# TD4_CPU.net
KiCad netlist of a schematic drawn in Altium Designer
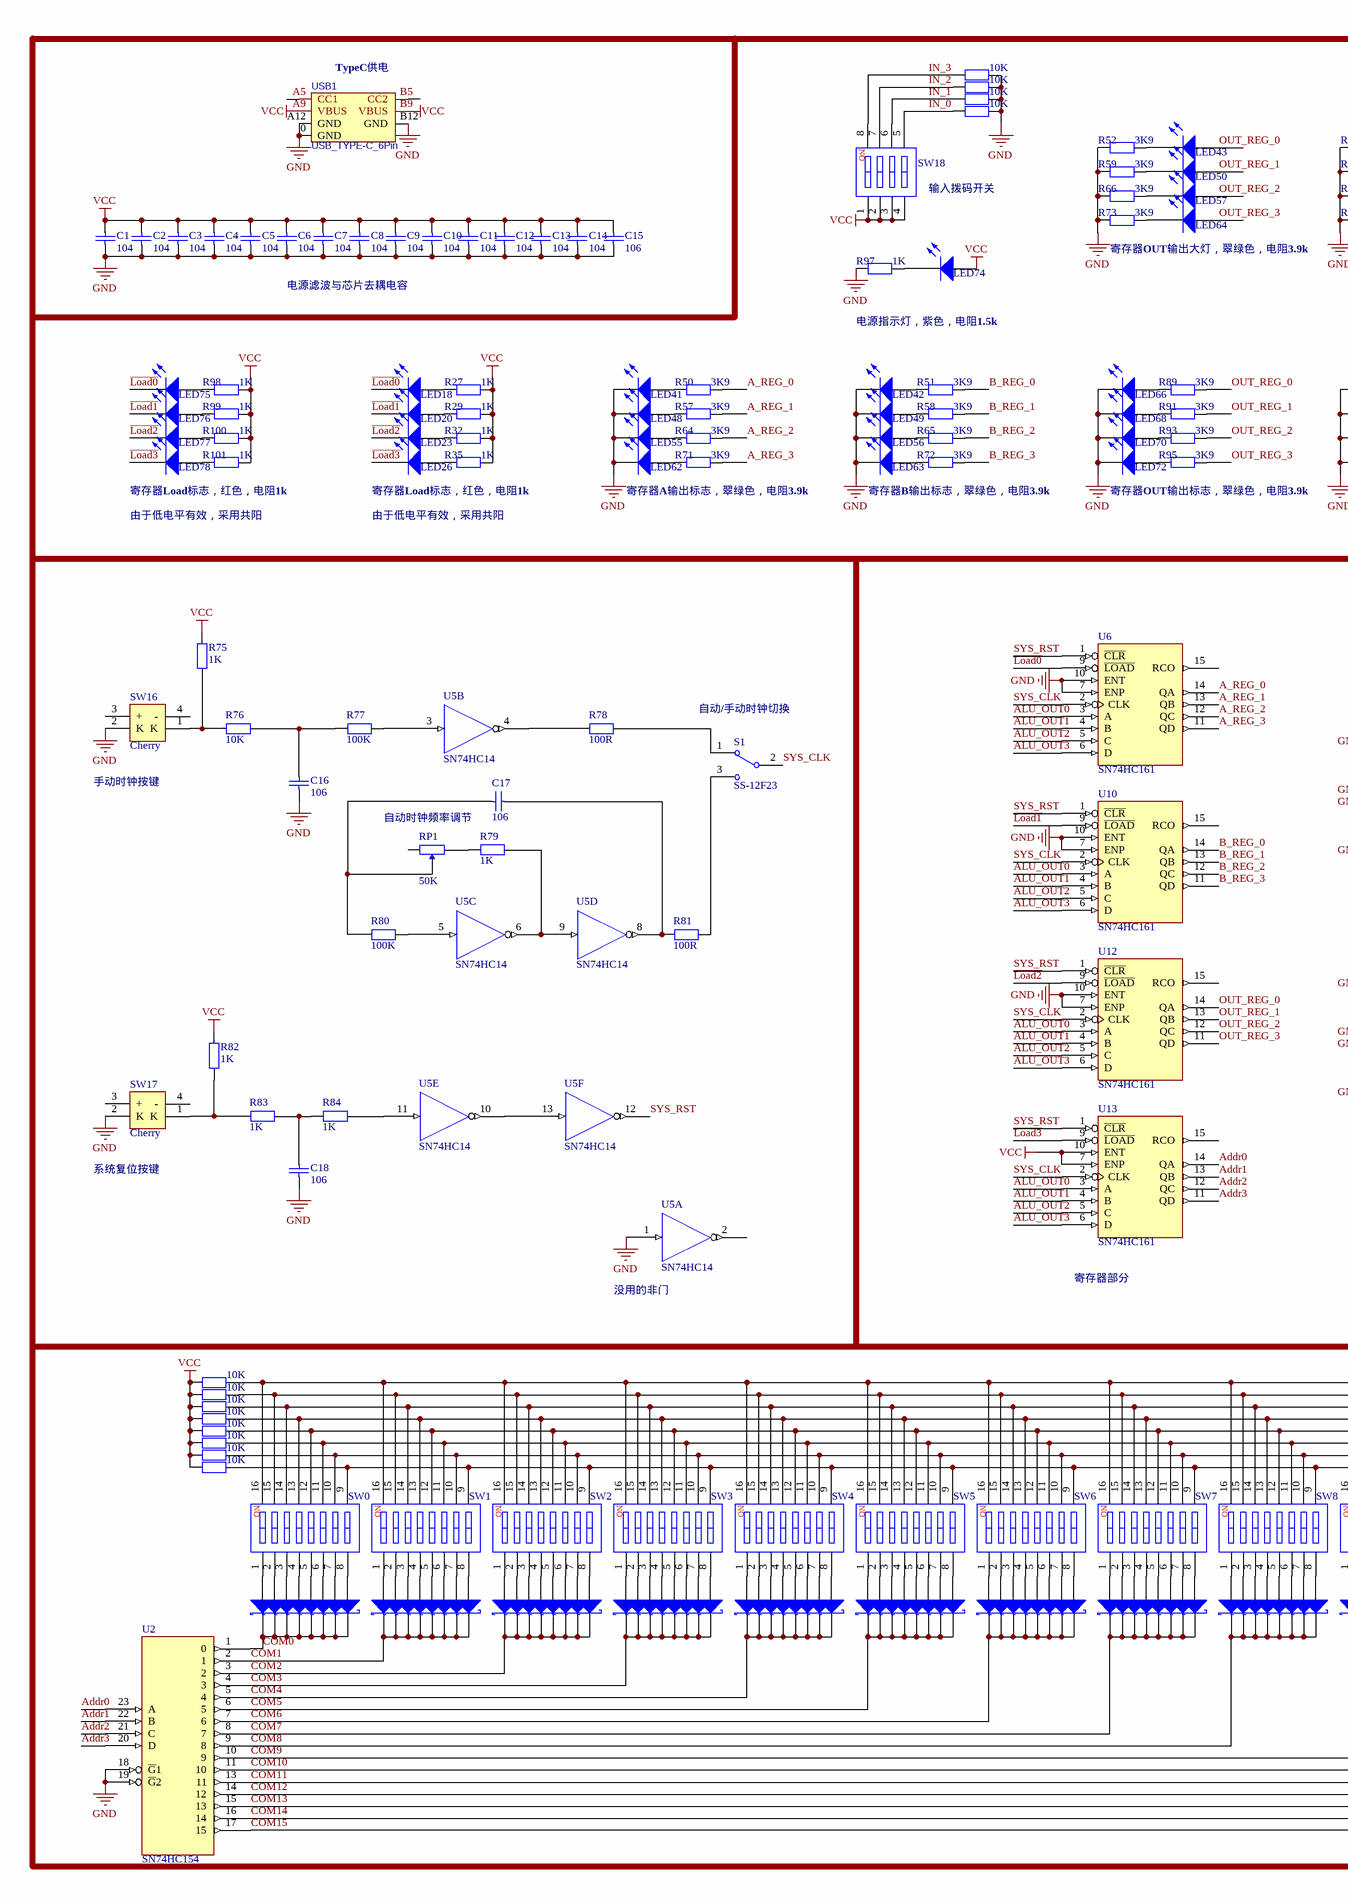
[diagram p0: TD4_CPU.SchDoc, left]
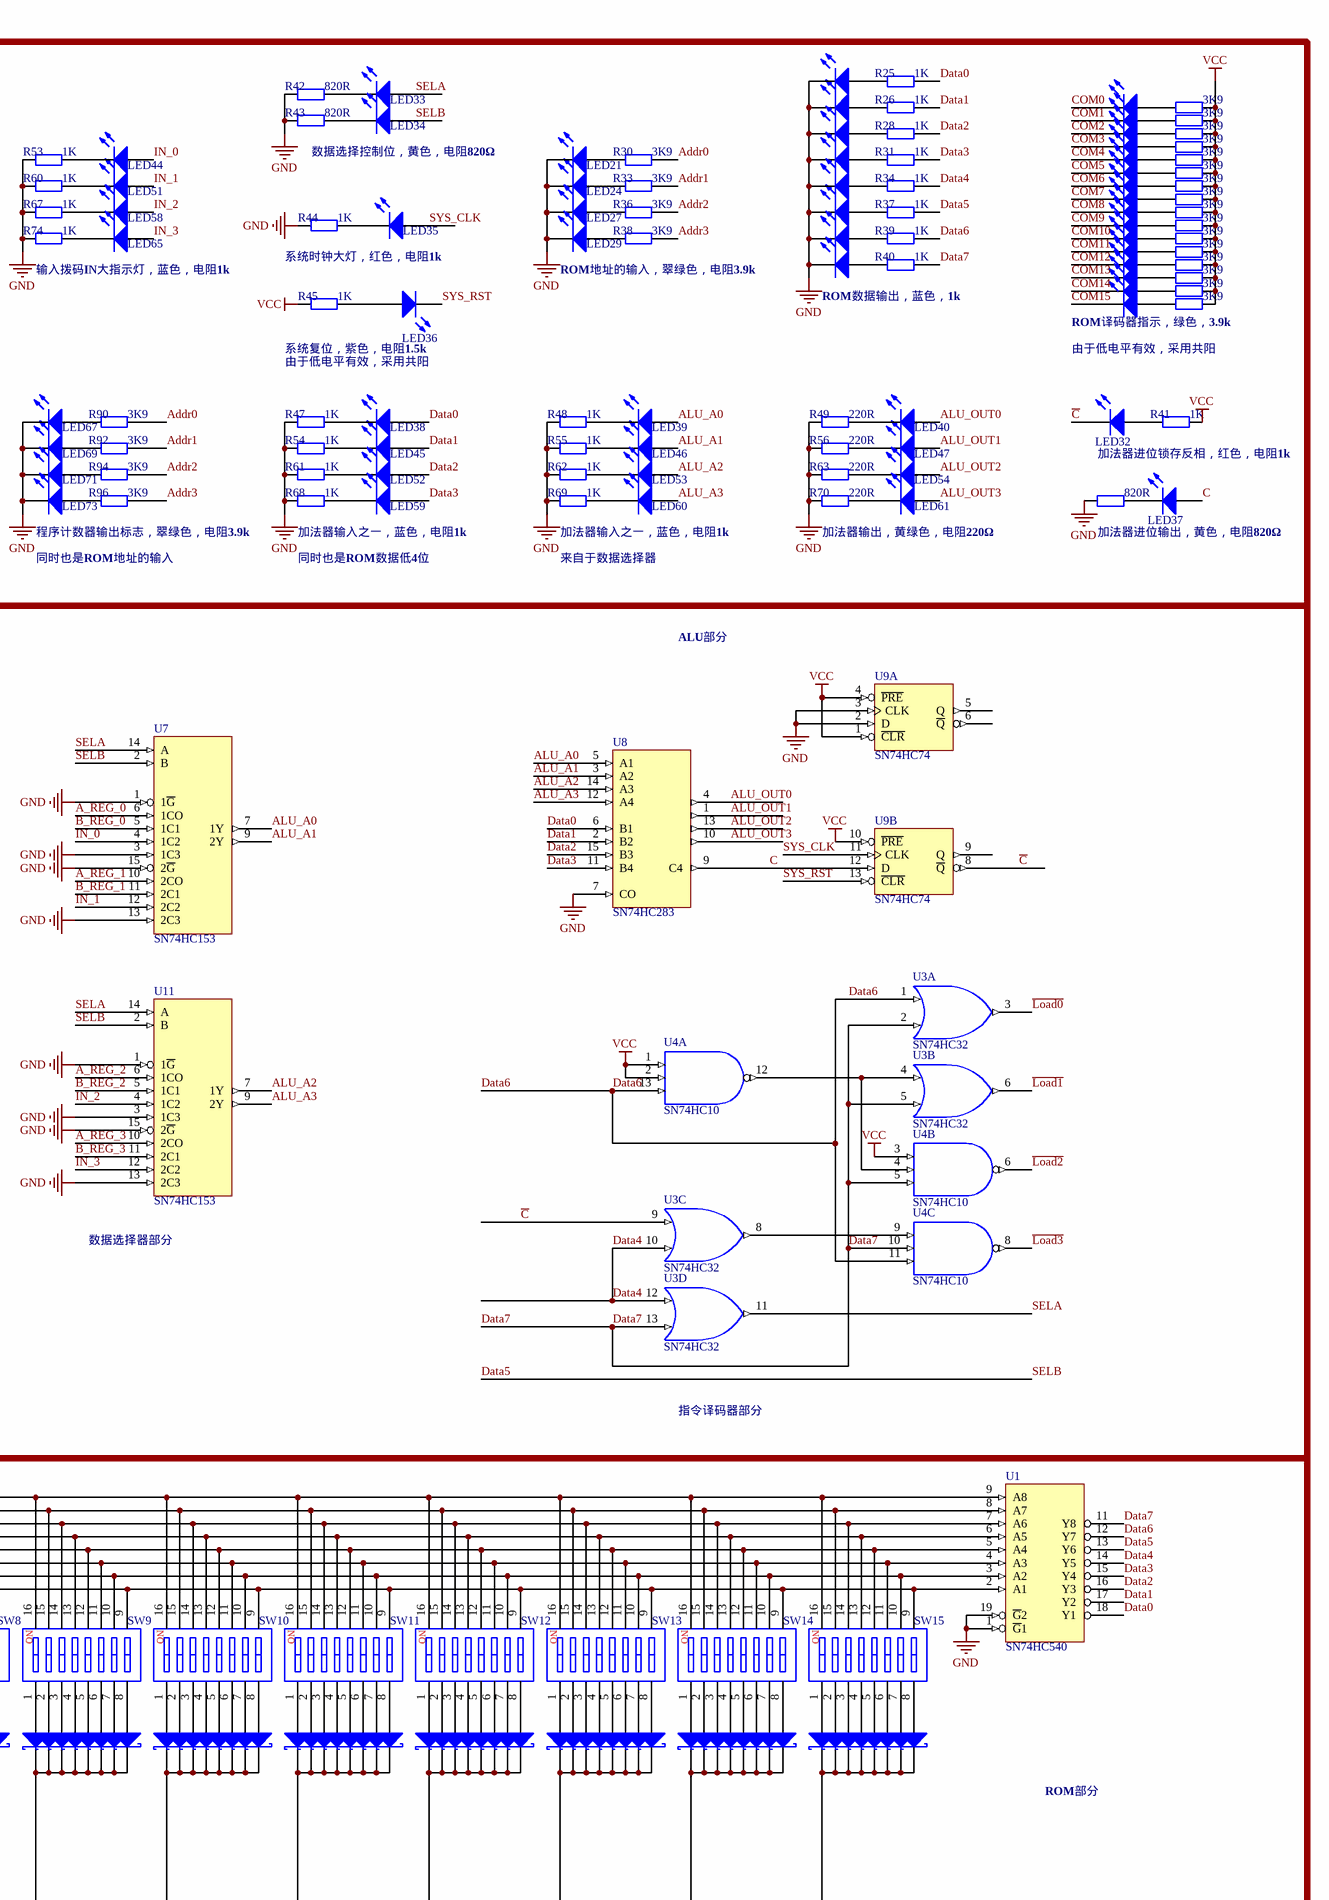
[diagram p1: TD4_CPU.SchDoc, right]

(export (version "E")
  (design (tool "Eeschema 10.0.6"))
  (components
    (comp (ref "C1")
      (value "104")
      (footprint "C0805_L")
      (description "贴片电容/MLCC电容")
      (libsource (lib "0.1 - 电阻-电容-电感-保险丝-晶振-晶体-磁珠-电位器-法拉电容-馈通电容") (part "C"))
    )
    (comp (ref "C2")
      (value "104")
      (footprint "C0805_L")
      (description "贴片电容/MLCC电容")
      (libsource (lib "0.1 - 电阻-电容-电感-保险丝-晶振-晶体-磁珠-电位器-法拉电容-馈通电容") (part "C"))
    )
    (comp (ref "C3")
      (value "104")
      (footprint "C0805_L")
      (description "贴片电容/MLCC电容")
      (libsource (lib "0.1 - 电阻-电容-电感-保险丝-晶振-晶体-磁珠-电位器-法拉电容-馈通电容") (part "C"))
    )
    (comp (ref "C4")
      (value "104")
      (footprint "C0805_L")
      (description "贴片电容/MLCC电容")
      (libsource (lib "0.1 - 电阻-电容-电感-保险丝-晶振-晶体-磁珠-电位器-法拉电容-馈通电容") (part "C"))
    )
    (comp (ref "C5")
      (value "104")
      (footprint "C0805_L")
      (description "贴片电容/MLCC电容")
      (libsource (lib "0.1 - 电阻-电容-电感-保险丝-晶振-晶体-磁珠-电位器-法拉电容-馈通电容") (part "C"))
    )
    (comp (ref "C6")
      (value "104")
      (footprint "C0805_L")
      (description "贴片电容/MLCC电容")
      (libsource (lib "0.1 - 电阻-电容-电感-保险丝-晶振-晶体-磁珠-电位器-法拉电容-馈通电容") (part "C"))
    )
    (comp (ref "C7")
      (value "104")
      (footprint "C0805_L")
      (description "贴片电容/MLCC电容")
      (libsource (lib "0.1 - 电阻-电容-电感-保险丝-晶振-晶体-磁珠-电位器-法拉电容-馈通电容") (part "C"))
    )
    (comp (ref "C8")
      (value "104")
      (footprint "C0805_L")
      (description "贴片电容/MLCC电容")
      (libsource (lib "0.1 - 电阻-电容-电感-保险丝-晶振-晶体-磁珠-电位器-法拉电容-馈通电容") (part "C"))
    )
    (comp (ref "C9")
      (value "104")
      (footprint "C0805_L")
      (description "贴片电容/MLCC电容")
      (libsource (lib "0.1 - 电阻-电容-电感-保险丝-晶振-晶体-磁珠-电位器-法拉电容-馈通电容") (part "C"))
    )
    (comp (ref "C10")
      (value "104")
      (footprint "C0805_L")
      (description "贴片电容/MLCC电容")
      (libsource (lib "0.1 - 电阻-电容-电感-保险丝-晶振-晶体-磁珠-电位器-法拉电容-馈通电容") (part "C"))
    )
    (comp (ref "C11")
      (value "104")
      (footprint "C0805_L")
      (description "贴片电容/MLCC电容")
      (libsource (lib "0.1 - 电阻-电容-电感-保险丝-晶振-晶体-磁珠-电位器-法拉电容-馈通电容") (part "C"))
    )
    (comp (ref "C12")
      (value "104")
      (footprint "C0805_L")
      (description "贴片电容/MLCC电容")
      (libsource (lib "0.1 - 电阻-电容-电感-保险丝-晶振-晶体-磁珠-电位器-法拉电容-馈通电容") (part "C"))
    )
    (comp (ref "C13")
      (value "104")
      (footprint "C0805_L")
      (description "贴片电容/MLCC电容")
      (libsource (lib "0.1 - 电阻-电容-电感-保险丝-晶振-晶体-磁珠-电位器-法拉电容-馈通电容") (part "C"))
    )
    (comp (ref "C14")
      (value "104")
      (footprint "C0805_L")
      (description "贴片电容/MLCC电容")
      (libsource (lib "0.1 - 电阻-电容-电感-保险丝-晶振-晶体-磁珠-电位器-法拉电容-馈通电容") (part "C"))
    )
    (comp (ref "C15")
      (value "106")
      (footprint "C0805_L")
      (description "贴片电容/MLCC电容")
      (libsource (lib "0.1 - 电阻-电容-电感-保险丝-晶振-晶体-磁珠-电位器-法拉电容-馈通电容") (part "C"))
    )
    (comp (ref "C16")
      (value "106")
      (footprint "C0805_L")
      (description "贴片电容/MLCC电容")
      (libsource (lib "0.1 - 电阻-电容-电感-保险丝-晶振-晶体-磁珠-电位器-法拉电容-馈通电容") (part "C"))
    )
    (comp (ref "C17")
      (value "106")
      (footprint "C0805_L")
      (description "贴片电容/MLCC电容")
      (libsource (lib "0.1 - 电阻-电容-电感-保险丝-晶振-晶体-磁珠-电位器-法拉电容-馈通电容") (part "C"))
    )
    (comp (ref "C18")
      (value "106")
      (footprint "C0805_L")
      (description "贴片电容/MLCC电容")
      (libsource (lib "0.1 - 电阻-电容-电感-保险丝-晶振-晶体-磁珠-电位器-法拉电容-馈通电容") (part "C"))
    )
    (comp (ref "D1")
      (value "SS14")
      (footprint "SOD-123")
      (description "肖特基二极管")
      (libsource (lib "0.2 - 二极管-TVS-ESD-整流桥-放电管") (part "SS14"))
    )
    (comp (ref "D2")
      (value "SS14")
      (footprint "SOD-123")
      (description "肖特基二极管")
      (libsource (lib "0.2 - 二极管-TVS-ESD-整流桥-放电管") (part "SS14"))
    )
    (comp (ref "D3")
      (value "SS14")
      (footprint "SOD-123")
      (description "肖特基二极管")
      (libsource (lib "0.2 - 二极管-TVS-ESD-整流桥-放电管") (part "SS14"))
    )
    (comp (ref "D4")
      (value "SS14")
      (footprint "SOD-123")
      (description "肖特基二极管")
      (libsource (lib "0.2 - 二极管-TVS-ESD-整流桥-放电管") (part "SS14"))
    )
    (comp (ref "D5")
      (value "SS14")
      (footprint "SOD-123")
      (description "肖特基二极管")
      (libsource (lib "0.2 - 二极管-TVS-ESD-整流桥-放电管") (part "SS14"))
    )
    (comp (ref "D6")
      (value "SS14")
      (footprint "SOD-123")
      (description "肖特基二极管")
      (libsource (lib "0.2 - 二极管-TVS-ESD-整流桥-放电管") (part "SS14"))
    )
    (comp (ref "D7")
      (value "SS14")
      (footprint "SOD-123")
      (description "肖特基二极管")
      (libsource (lib "0.2 - 二极管-TVS-ESD-整流桥-放电管") (part "SS14"))
    )
    (comp (ref "D8")
      (value "SS14")
      (footprint "SOD-123")
      (description "肖特基二极管")
      (libsource (lib "0.2 - 二极管-TVS-ESD-整流桥-放电管") (part "SS14"))
    )
    (comp (ref "D9")
      (value "SS14")
      (footprint "SOD-123")
      (description "肖特基二极管")
      (libsource (lib "0.2 - 二极管-TVS-ESD-整流桥-放电管") (part "SS14"))
    )
    (comp (ref "D10")
      (value "SS14")
      (footprint "SOD-123")
      (description "肖特基二极管")
      (libsource (lib "0.2 - 二极管-TVS-ESD-整流桥-放电管") (part "SS14"))
    )
    (comp (ref "D11")
      (value "SS14")
      (footprint "SOD-123")
      (description "肖特基二极管")
      (libsource (lib "0.2 - 二极管-TVS-ESD-整流桥-放电管") (part "SS14"))
    )
    (comp (ref "D12")
      (value "SS14")
      (footprint "SOD-123")
      (description "肖特基二极管")
      (libsource (lib "0.2 - 二极管-TVS-ESD-整流桥-放电管") (part "SS14"))
    )
    (comp (ref "D13")
      (value "SS14")
      (footprint "SOD-123")
      (description "肖特基二极管")
      (libsource (lib "0.2 - 二极管-TVS-ESD-整流桥-放电管") (part "SS14"))
    )
    (comp (ref "D14")
      (value "SS14")
      (footprint "SOD-123")
      (description "肖特基二极管")
      (libsource (lib "0.2 - 二极管-TVS-ESD-整流桥-放电管") (part "SS14"))
    )
    (comp (ref "D15")
      (value "SS14")
      (footprint "SOD-123")
      (description "肖特基二极管")
      (libsource (lib "0.2 - 二极管-TVS-ESD-整流桥-放电管") (part "SS14"))
    )
    (comp (ref "D16")
      (value "SS14")
      (footprint "SOD-123")
      (description "肖特基二极管")
      (libsource (lib "0.2 - 二极管-TVS-ESD-整流桥-放电管") (part "SS14"))
    )
    (comp (ref "D17")
      (value "SS14")
      (footprint "SOD-123")
      (description "肖特基二极管")
      (libsource (lib "0.2 - 二极管-TVS-ESD-整流桥-放电管") (part "SS14"))
    )
    (comp (ref "D18")
      (value "SS14")
      (footprint "SOD-123")
      (description "肖特基二极管")
      (libsource (lib "0.2 - 二极管-TVS-ESD-整流桥-放电管") (part "SS14"))
    )
    (comp (ref "D19")
      (value "SS14")
      (footprint "SOD-123")
      (description "肖特基二极管")
      (libsource (lib "0.2 - 二极管-TVS-ESD-整流桥-放电管") (part "SS14"))
    )
    (comp (ref "D20")
      (value "SS14")
      (footprint "SOD-123")
      (description "肖特基二极管")
      (libsource (lib "0.2 - 二极管-TVS-ESD-整流桥-放电管") (part "SS14"))
    )
    (comp (ref "D21")
      (value "SS14")
      (footprint "SOD-123")
      (description "肖特基二极管")
      (libsource (lib "0.2 - 二极管-TVS-ESD-整流桥-放电管") (part "SS14"))
    )
    (comp (ref "D22")
      (value "SS14")
      (footprint "SOD-123")
      (description "肖特基二极管")
      (libsource (lib "0.2 - 二极管-TVS-ESD-整流桥-放电管") (part "SS14"))
    )
    (comp (ref "D23")
      (value "SS14")
      (footprint "SOD-123")
      (description "肖特基二极管")
      (libsource (lib "0.2 - 二极管-TVS-ESD-整流桥-放电管") (part "SS14"))
    )
    (comp (ref "D24")
      (value "SS14")
      (footprint "SOD-123")
      (description "肖特基二极管")
      (libsource (lib "0.2 - 二极管-TVS-ESD-整流桥-放电管") (part "SS14"))
    )
    (comp (ref "D25")
      (value "SS14")
      (footprint "SOD-123")
      (description "肖特基二极管")
      (libsource (lib "0.2 - 二极管-TVS-ESD-整流桥-放电管") (part "SS14"))
    )
    (comp (ref "D26")
      (value "SS14")
      (footprint "SOD-123")
      (description "肖特基二极管")
      (libsource (lib "0.2 - 二极管-TVS-ESD-整流桥-放电管") (part "SS14"))
    )
    (comp (ref "D27")
      (value "SS14")
      (footprint "SOD-123")
      (description "肖特基二极管")
      (libsource (lib "0.2 - 二极管-TVS-ESD-整流桥-放电管") (part "SS14"))
    )
    (comp (ref "D28")
      (value "SS14")
      (footprint "SOD-123")
      (description "肖特基二极管")
      (libsource (lib "0.2 - 二极管-TVS-ESD-整流桥-放电管") (part "SS14"))
    )
    (comp (ref "D29")
      (value "SS14")
      (footprint "SOD-123")
      (description "肖特基二极管")
      (libsource (lib "0.2 - 二极管-TVS-ESD-整流桥-放电管") (part "SS14"))
    )
    (comp (ref "D30")
      (value "SS14")
      (footprint "SOD-123")
      (description "肖特基二极管")
      (libsource (lib "0.2 - 二极管-TVS-ESD-整流桥-放电管") (part "SS14"))
    )
    (comp (ref "D31")
      (value "SS14")
      (footprint "SOD-123")
      (description "肖特基二极管")
      (libsource (lib "0.2 - 二极管-TVS-ESD-整流桥-放电管") (part "SS14"))
    )
    (comp (ref "D32")
      (value "SS14")
      (footprint "SOD-123")
      (description "肖特基二极管")
      (libsource (lib "0.2 - 二极管-TVS-ESD-整流桥-放电管") (part "SS14"))
    )
    (comp (ref "D33")
      (value "SS14")
      (footprint "SOD-123")
      (description "肖特基二极管")
      (libsource (lib "0.2 - 二极管-TVS-ESD-整流桥-放电管") (part "SS14"))
    )
    (comp (ref "D34")
      (value "SS14")
      (footprint "SOD-123")
      (description "肖特基二极管")
      (libsource (lib "0.2 - 二极管-TVS-ESD-整流桥-放电管") (part "SS14"))
    )
    (comp (ref "D35")
      (value "SS14")
      (footprint "SOD-123")
      (description "肖特基二极管")
      (libsource (lib "0.2 - 二极管-TVS-ESD-整流桥-放电管") (part "SS14"))
    )
    (comp (ref "D36")
      (value "SS14")
      (footprint "SOD-123")
      (description "肖特基二极管")
      (libsource (lib "0.2 - 二极管-TVS-ESD-整流桥-放电管") (part "SS14"))
    )
    (comp (ref "D37")
      (value "SS14")
      (footprint "SOD-123")
      (description "肖特基二极管")
      (libsource (lib "0.2 - 二极管-TVS-ESD-整流桥-放电管") (part "SS14"))
    )
    (comp (ref "D38")
      (value "SS14")
      (footprint "SOD-123")
      (description "肖特基二极管")
      (libsource (lib "0.2 - 二极管-TVS-ESD-整流桥-放电管") (part "SS14"))
    )
    (comp (ref "D39")
      (value "SS14")
      (footprint "SOD-123")
      (description "肖特基二极管")
      (libsource (lib "0.2 - 二极管-TVS-ESD-整流桥-放电管") (part "SS14"))
    )
    (comp (ref "D40")
      (value "SS14")
      (footprint "SOD-123")
      (description "肖特基二极管")
      (libsource (lib "0.2 - 二极管-TVS-ESD-整流桥-放电管") (part "SS14"))
    )
    (comp (ref "D41")
      (value "SS14")
      (footprint "SOD-123")
      (description "肖特基二极管")
      (libsource (lib "0.2 - 二极管-TVS-ESD-整流桥-放电管") (part "SS14"))
    )
    (comp (ref "D42")
      (value "SS14")
      (footprint "SOD-123")
      (description "肖特基二极管")
      (libsource (lib "0.2 - 二极管-TVS-ESD-整流桥-放电管") (part "SS14"))
    )
    (comp (ref "D43")
      (value "SS14")
      (footprint "SOD-123")
      (description "肖特基二极管")
      (libsource (lib "0.2 - 二极管-TVS-ESD-整流桥-放电管") (part "SS14"))
    )
    (comp (ref "D44")
      (value "SS14")
      (footprint "SOD-123")
      (description "肖特基二极管")
      (libsource (lib "0.2 - 二极管-TVS-ESD-整流桥-放电管") (part "SS14"))
    )
    (comp (ref "D45")
      (value "SS14")
      (footprint "SOD-123")
      (description "肖特基二极管")
      (libsource (lib "0.2 - 二极管-TVS-ESD-整流桥-放电管") (part "SS14"))
    )
    (comp (ref "D46")
      (value "SS14")
      (footprint "SOD-123")
      (description "肖特基二极管")
      (libsource (lib "0.2 - 二极管-TVS-ESD-整流桥-放电管") (part "SS14"))
    )
    (comp (ref "D47")
      (value "SS14")
      (footprint "SOD-123")
      (description "肖特基二极管")
      (libsource (lib "0.2 - 二极管-TVS-ESD-整流桥-放电管") (part "SS14"))
    )
    (comp (ref "D48")
      (value "SS14")
      (footprint "SOD-123")
      (description "肖特基二极管")
      (libsource (lib "0.2 - 二极管-TVS-ESD-整流桥-放电管") (part "SS14"))
    )
    (comp (ref "D49")
      (value "SS14")
      (footprint "SOD-123")
      (description "肖特基二极管")
      (libsource (lib "0.2 - 二极管-TVS-ESD-整流桥-放电管") (part "SS14"))
    )
    (comp (ref "D50")
      (value "SS14")
      (footprint "SOD-123")
      (description "肖特基二极管")
      (libsource (lib "0.2 - 二极管-TVS-ESD-整流桥-放电管") (part "SS14"))
    )
    (comp (ref "D51")
      (value "SS14")
      (footprint "SOD-123")
      (description "肖特基二极管")
      (libsource (lib "0.2 - 二极管-TVS-ESD-整流桥-放电管") (part "SS14"))
    )
    (comp (ref "D52")
      (value "SS14")
      (footprint "SOD-123")
      (description "肖特基二极管")
      (libsource (lib "0.2 - 二极管-TVS-ESD-整流桥-放电管") (part "SS14"))
    )
    (comp (ref "D53")
      (value "SS14")
      (footprint "SOD-123")
      (description "肖特基二极管")
      (libsource (lib "0.2 - 二极管-TVS-ESD-整流桥-放电管") (part "SS14"))
    )
    (comp (ref "D54")
      (value "SS14")
      (footprint "SOD-123")
      (description "肖特基二极管")
      (libsource (lib "0.2 - 二极管-TVS-ESD-整流桥-放电管") (part "SS14"))
    )
    (comp (ref "D55")
      (value "SS14")
      (footprint "SOD-123")
      (description "肖特基二极管")
      (libsource (lib "0.2 - 二极管-TVS-ESD-整流桥-放电管") (part "SS14"))
    )
    (comp (ref "D56")
      (value "SS14")
      (footprint "SOD-123")
      (description "肖特基二极管")
      (libsource (lib "0.2 - 二极管-TVS-ESD-整流桥-放电管") (part "SS14"))
    )
    (comp (ref "D57")
      (value "SS14")
      (footprint "SOD-123")
      (description "肖特基二极管")
      (libsource (lib "0.2 - 二极管-TVS-ESD-整流桥-放电管") (part "SS14"))
    )
    (comp (ref "D58")
      (value "SS14")
      (footprint "SOD-123")
      (description "肖特基二极管")
      (libsource (lib "0.2 - 二极管-TVS-ESD-整流桥-放电管") (part "SS14"))
    )
    (comp (ref "D59")
      (value "SS14")
      (footprint "SOD-123")
      (description "肖特基二极管")
      (libsource (lib "0.2 - 二极管-TVS-ESD-整流桥-放电管") (part "SS14"))
    )
    (comp (ref "D60")
      (value "SS14")
      (footprint "SOD-123")
      (description "肖特基二极管")
      (libsource (lib "0.2 - 二极管-TVS-ESD-整流桥-放电管") (part "SS14"))
    )
    (comp (ref "D61")
      (value "SS14")
      (footprint "SOD-123")
      (description "肖特基二极管")
      (libsource (lib "0.2 - 二极管-TVS-ESD-整流桥-放电管") (part "SS14"))
    )
    (comp (ref "D62")
      (value "SS14")
      (footprint "SOD-123")
      (description "肖特基二极管")
      (libsource (lib "0.2 - 二极管-TVS-ESD-整流桥-放电管") (part "SS14"))
    )
    (comp (ref "D63")
      (value "SS14")
      (footprint "SOD-123")
      (description "肖特基二极管")
      (libsource (lib "0.2 - 二极管-TVS-ESD-整流桥-放电管") (part "SS14"))
    )
    (comp (ref "D64")
      (value "SS14")
      (footprint "SOD-123")
      (description "肖特基二极管")
      (libsource (lib "0.2 - 二极管-TVS-ESD-整流桥-放电管") (part "SS14"))
    )
    (comp (ref "D65")
      (value "SS14")
      (footprint "SOD-123")
      (description "肖特基二极管")
      (libsource (lib "0.2 - 二极管-TVS-ESD-整流桥-放电管") (part "SS14"))
    )
    (comp (ref "D66")
      (value "SS14")
      (footprint "SOD-123")
      (description "肖特基二极管")
      (libsource (lib "0.2 - 二极管-TVS-ESD-整流桥-放电管") (part "SS14"))
    )
    (comp (ref "D67")
      (value "SS14")
      (footprint "SOD-123")
      (description "肖特基二极管")
      (libsource (lib "0.2 - 二极管-TVS-ESD-整流桥-放电管") (part "SS14"))
    )
    (comp (ref "D68")
      (value "SS14")
      (footprint "SOD-123")
      (description "肖特基二极管")
      (libsource (lib "0.2 - 二极管-TVS-ESD-整流桥-放电管") (part "SS14"))
    )
    (comp (ref "D69")
      (value "SS14")
      (footprint "SOD-123")
      (description "肖特基二极管")
      (libsource (lib "0.2 - 二极管-TVS-ESD-整流桥-放电管") (part "SS14"))
    )
    (comp (ref "D70")
      (value "SS14")
      (footprint "SOD-123")
      (description "肖特基二极管")
      (libsource (lib "0.2 - 二极管-TVS-ESD-整流桥-放电管") (part "SS14"))
    )
    (comp (ref "D71")
      (value "SS14")
      (footprint "SOD-123")
      (description "肖特基二极管")
      (libsource (lib "0.2 - 二极管-TVS-ESD-整流桥-放电管") (part "SS14"))
    )
    (comp (ref "D72")
      (value "SS14")
      (footprint "SOD-123")
      (description "肖特基二极管")
      (libsource (lib "0.2 - 二极管-TVS-ESD-整流桥-放电管") (part "SS14"))
    )
    (comp (ref "D73")
      (value "SS14")
      (footprint "SOD-123")
      (description "肖特基二极管")
      (libsource (lib "0.2 - 二极管-TVS-ESD-整流桥-放电管") (part "SS14"))
    )
    (comp (ref "D74")
      (value "SS14")
      (footprint "SOD-123")
      (description "肖特基二极管")
      (libsource (lib "0.2 - 二极管-TVS-ESD-整流桥-放电管") (part "SS14"))
    )
    (comp (ref "D75")
      (value "SS14")
      (footprint "SOD-123")
      (description "肖特基二极管")
      (libsource (lib "0.2 - 二极管-TVS-ESD-整流桥-放电管") (part "SS14"))
    )
    (comp (ref "D76")
      (value "SS14")
      (footprint "SOD-123")
      (description "肖特基二极管")
      (libsource (lib "0.2 - 二极管-TVS-ESD-整流桥-放电管") (part "SS14"))
    )
    (comp (ref "D77")
      (value "SS14")
      (footprint "SOD-123")
      (description "肖特基二极管")
      (libsource (lib "0.2 - 二极管-TVS-ESD-整流桥-放电管") (part "SS14"))
    )
    (comp (ref "D78")
      (value "SS14")
      (footprint "SOD-123")
      (description "肖特基二极管")
      (libsource (lib "0.2 - 二极管-TVS-ESD-整流桥-放电管") (part "SS14"))
    )
    (comp (ref "D79")
      (value "SS14")
      (footprint "SOD-123")
      (description "肖特基二极管")
      (libsource (lib "0.2 - 二极管-TVS-ESD-整流桥-放电管") (part "SS14"))
    )
    (comp (ref "D80")
      (value "SS14")
      (footprint "SOD-123")
      (description "肖特基二极管")
      (libsource (lib "0.2 - 二极管-TVS-ESD-整流桥-放电管") (part "SS14"))
    )
    (comp (ref "D81")
      (value "SS14")
      (footprint "SOD-123")
      (description "肖特基二极管")
      (libsource (lib "0.2 - 二极管-TVS-ESD-整流桥-放电管") (part "SS14"))
    )
    (comp (ref "D82")
      (value "SS14")
      (footprint "SOD-123")
      (description "肖特基二极管")
      (libsource (lib "0.2 - 二极管-TVS-ESD-整流桥-放电管") (part "SS14"))
    )
    (comp (ref "D83")
      (value "SS14")
      (footprint "SOD-123")
      (description "肖特基二极管")
      (libsource (lib "0.2 - 二极管-TVS-ESD-整流桥-放电管") (part "SS14"))
    )
    (comp (ref "D84")
      (value "SS14")
      (footprint "SOD-123")
      (description "肖特基二极管")
      (libsource (lib "0.2 - 二极管-TVS-ESD-整流桥-放电管") (part "SS14"))
    )
    (comp (ref "D85")
      (value "SS14")
      (footprint "SOD-123")
      (description "肖特基二极管")
      (libsource (lib "0.2 - 二极管-TVS-ESD-整流桥-放电管") (part "SS14"))
    )
    (comp (ref "D86")
      (value "SS14")
      (footprint "SOD-123")
      (description "肖特基二极管")
      (libsource (lib "0.2 - 二极管-TVS-ESD-整流桥-放电管") (part "SS14"))
    )
    (comp (ref "D87")
      (value "SS14")
      (footprint "SOD-123")
      (description "肖特基二极管")
      (libsource (lib "0.2 - 二极管-TVS-ESD-整流桥-放电管") (part "SS14"))
    )
    (comp (ref "D88")
      (value "SS14")
      (footprint "SOD-123")
      (description "肖特基二极管")
      (libsource (lib "0.2 - 二极管-TVS-ESD-整流桥-放电管") (part "SS14"))
    )
    (comp (ref "D89")
      (value "SS14")
      (footprint "SOD-123")
      (description "肖特基二极管")
      (libsource (lib "0.2 - 二极管-TVS-ESD-整流桥-放电管") (part "SS14"))
    )
    (comp (ref "D90")
      (value "SS14")
      (footprint "SOD-123")
      (description "肖特基二极管")
      (libsource (lib "0.2 - 二极管-TVS-ESD-整流桥-放电管") (part "SS14"))
    )
    (comp (ref "D91")
      (value "SS14")
      (footprint "SOD-123")
      (description "肖特基二极管")
      (libsource (lib "0.2 - 二极管-TVS-ESD-整流桥-放电管") (part "SS14"))
    )
    (comp (ref "D92")
      (value "SS14")
      (footprint "SOD-123")
      (description "肖特基二极管")
      (libsource (lib "0.2 - 二极管-TVS-ESD-整流桥-放电管") (part "SS14"))
    )
    (comp (ref "D93")
      (value "SS14")
      (footprint "SOD-123")
      (description "肖特基二极管")
      (libsource (lib "0.2 - 二极管-TVS-ESD-整流桥-放电管") (part "SS14"))
    )
    (comp (ref "D94")
      (value "SS14")
      (footprint "SOD-123")
      (description "肖特基二极管")
      (libsource (lib "0.2 - 二极管-TVS-ESD-整流桥-放电管") (part "SS14"))
    )
    (comp (ref "D95")
      (value "SS14")
      (footprint "SOD-123")
      (description "肖特基二极管")
      (libsource (lib "0.2 - 二极管-TVS-ESD-整流桥-放电管") (part "SS14"))
    )
    (comp (ref "D96")
      (value "SS14")
      (footprint "SOD-123")
      (description "肖特基二极管")
      (libsource (lib "0.2 - 二极管-TVS-ESD-整流桥-放电管") (part "SS14"))
    )
    (comp (ref "D97")
      (value "SS14")
      (footprint "SOD-123")
      (description "肖特基二极管")
      (libsource (lib "0.2 - 二极管-TVS-ESD-整流桥-放电管") (part "SS14"))
    )
    (comp (ref "D98")
      (value "SS14")
      (footprint "SOD-123")
      (description "肖特基二极管")
      (libsource (lib "0.2 - 二极管-TVS-ESD-整流桥-放电管") (part "SS14"))
    )
    (comp (ref "D99")
      (value "SS14")
      (footprint "SOD-123")
      (description "肖特基二极管")
      (libsource (lib "0.2 - 二极管-TVS-ESD-整流桥-放电管") (part "SS14"))
    )
    (comp (ref "D100")
      (value "SS14")
      (footprint "SOD-123")
      (description "肖特基二极管")
      (libsource (lib "0.2 - 二极管-TVS-ESD-整流桥-放电管") (part "SS14"))
    )
    (comp (ref "D101")
      (value "SS14")
      (footprint "SOD-123")
      (description "肖特基二极管")
      (libsource (lib "0.2 - 二极管-TVS-ESD-整流桥-放电管") (part "SS14"))
    )
    (comp (ref "D102")
      (value "SS14")
      (footprint "SOD-123")
      (description "肖特基二极管")
      (libsource (lib "0.2 - 二极管-TVS-ESD-整流桥-放电管") (part "SS14"))
    )
    (comp (ref "D103")
      (value "SS14")
      (footprint "SOD-123")
      (description "肖特基二极管")
      (libsource (lib "0.2 - 二极管-TVS-ESD-整流桥-放电管") (part "SS14"))
    )
    (comp (ref "D104")
      (value "SS14")
      (footprint "SOD-123")
      (description "肖特基二极管")
      (libsource (lib "0.2 - 二极管-TVS-ESD-整流桥-放电管") (part "SS14"))
    )
    (comp (ref "D105")
      (value "SS14")
      (footprint "SOD-123")
      (description "肖特基二极管")
      (libsource (lib "0.2 - 二极管-TVS-ESD-整流桥-放电管") (part "SS14"))
    )
    (comp (ref "D106")
      (value "SS14")
      (footprint "SOD-123")
      (description "肖特基二极管")
      (libsource (lib "0.2 - 二极管-TVS-ESD-整流桥-放电管") (part "SS14"))
    )
    (comp (ref "D107")
      (value "SS14")
      (footprint "SOD-123")
      (description "肖特基二极管")
      (libsource (lib "0.2 - 二极管-TVS-ESD-整流桥-放电管") (part "SS14"))
    )
    (comp (ref "D108")
      (value "SS14")
      (footprint "SOD-123")
      (description "肖特基二极管")
      (libsource (lib "0.2 - 二极管-TVS-ESD-整流桥-放电管") (part "SS14"))
    )
    (comp (ref "D109")
      (value "SS14")
      (footprint "SOD-123")
      (description "肖特基二极管")
      (libsource (lib "0.2 - 二极管-TVS-ESD-整流桥-放电管") (part "SS14"))
    )
    (comp (ref "D110")
      (value "SS14")
      (footprint "SOD-123")
      (description "肖特基二极管")
      (libsource (lib "0.2 - 二极管-TVS-ESD-整流桥-放电管") (part "SS14"))
    )
    (comp (ref "D111")
      (value "SS14")
      (footprint "SOD-123")
      (description "肖特基二极管")
      (libsource (lib "0.2 - 二极管-TVS-ESD-整流桥-放电管") (part "SS14"))
    )
    (comp (ref "D112")
      (value "SS14")
      (footprint "SOD-123")
      (description "肖特基二极管")
      (libsource (lib "0.2 - 二极管-TVS-ESD-整流桥-放电管") (part "SS14"))
    )
    (comp (ref "D113")
      (value "SS14")
      (footprint "SOD-123")
      (description "肖特基二极管")
      (libsource (lib "0.2 - 二极管-TVS-ESD-整流桥-放电管") (part "SS14"))
    )
    (comp (ref "D114")
      (value "SS14")
      (footprint "SOD-123")
      (description "肖特基二极管")
      (libsource (lib "0.2 - 二极管-TVS-ESD-整流桥-放电管") (part "SS14"))
    )
    (comp (ref "D115")
      (value "SS14")
      (footprint "SOD-123")
      (description "肖特基二极管")
      (libsource (lib "0.2 - 二极管-TVS-ESD-整流桥-放电管") (part "SS14"))
    )
    (comp (ref "D116")
      (value "SS14")
      (footprint "SOD-123")
      (description "肖特基二极管")
      (libsource (lib "0.2 - 二极管-TVS-ESD-整流桥-放电管") (part "SS14"))
    )
    (comp (ref "D117")
      (value "SS14")
      (footprint "SOD-123")
      (description "肖特基二极管")
      (libsource (lib "0.2 - 二极管-TVS-ESD-整流桥-放电管") (part "SS14"))
    )
    (comp (ref "D118")
      (value "SS14")
      (footprint "SOD-123")
      (description "肖特基二极管")
      (libsource (lib "0.2 - 二极管-TVS-ESD-整流桥-放电管") (part "SS14"))
    )
    (comp (ref "D119")
      (value "SS14")
      (footprint "SOD-123")
      (description "肖特基二极管")
      (libsource (lib "0.2 - 二极管-TVS-ESD-整流桥-放电管") (part "SS14"))
    )
    (comp (ref "D120")
      (value "SS14")
      (footprint "SOD-123")
      (description "肖特基二极管")
      (libsource (lib "0.2 - 二极管-TVS-ESD-整流桥-放电管") (part "SS14"))
    )
    (comp (ref "D121")
      (value "SS14")
      (footprint "SOD-123")
      (description "肖特基二极管")
      (libsource (lib "0.2 - 二极管-TVS-ESD-整流桥-放电管") (part "SS14"))
    )
    (comp (ref "D122")
      (value "SS14")
      (footprint "SOD-123")
      (description "肖特基二极管")
      (libsource (lib "0.2 - 二极管-TVS-ESD-整流桥-放电管") (part "SS14"))
    )
    (comp (ref "D123")
      (value "SS14")
      (footprint "SOD-123")
      (description "肖特基二极管")
      (libsource (lib "0.2 - 二极管-TVS-ESD-整流桥-放电管") (part "SS14"))
    )
    (comp (ref "D124")
      (value "SS14")
      (footprint "SOD-123")
      (description "肖特基二极管")
      (libsource (lib "0.2 - 二极管-TVS-ESD-整流桥-放电管") (part "SS14"))
    )
    (comp (ref "D125")
      (value "SS14")
      (footprint "SOD-123")
      (description "肖特基二极管")
      (libsource (lib "0.2 - 二极管-TVS-ESD-整流桥-放电管") (part "SS14"))
    )
    (comp (ref "D126")
      (value "SS14")
      (footprint "SOD-123")
      (description "肖特基二极管")
      (libsource (lib "0.2 - 二极管-TVS-ESD-整流桥-放电管") (part "SS14"))
    )
    (comp (ref "D127")
      (value "SS14")
      (footprint "SOD-123")
      (description "肖特基二极管")
      (libsource (lib "0.2 - 二极管-TVS-ESD-整流桥-放电管") (part "SS14"))
    )
    (comp (ref "D128")
      (value "SS14")
      (footprint "SOD-123")
      (description "肖特基二极管")
      (libsource (lib "0.2 - 二极管-TVS-ESD-整流桥-放电管") (part "SS14"))
    )
    (comp (ref "LED0")
      (value "绿色")
      (footprint "LED0805_B")
      (description "贴片LED")
      (libsource (lib "0.3 - LED发光二极管-IR二极管_接收管-光耦") (part "LED"))
    )
    (comp (ref "LED1")
      (value "绿色")
      (footprint "LED0805_B")
      (description "贴片LED")
      (libsource (lib "0.3 - LED发光二极管-IR二极管_接收管-光耦") (part "LED"))
    )
    (comp (ref "LED2")
      (value "绿色")
      (footprint "LED0805_B")
      (description "贴片LED")
      (libsource (lib "0.3 - LED发光二极管-IR二极管_接收管-光耦") (part "LED"))
    )
    (comp (ref "LED3")
      (value "绿色")
      (footprint "LED0805_B")
      (description "贴片LED")
      (libsource (lib "0.3 - LED发光二极管-IR二极管_接收管-光耦") (part "LED"))
    )
    (comp (ref "LED4")
      (value "绿色")
      (footprint "LED0805_B")
      (description "贴片LED")
      (libsource (lib "0.3 - LED发光二极管-IR二极管_接收管-光耦") (part "LED"))
    )
    (comp (ref "LED5")
      (value "绿色")
      (footprint "LED0805_B")
      (description "贴片LED")
      (libsource (lib "0.3 - LED发光二极管-IR二极管_接收管-光耦") (part "LED"))
    )
    (comp (ref "LED6")
      (value "绿色")
      (footprint "LED0805_B")
      (description "贴片LED")
      (libsource (lib "0.3 - LED发光二极管-IR二极管_接收管-光耦") (part "LED"))
    )
    (comp (ref "LED7")
      (value "绿色")
      (footprint "LED0805_B")
      (description "贴片LED")
      (libsource (lib "0.3 - LED发光二极管-IR二极管_接收管-光耦") (part "LED"))
    )
    (comp (ref "LED8")
      (value "绿色")
      (footprint "LED0805_B")
      (description "贴片LED")
      (libsource (lib "0.3 - LED发光二极管-IR二极管_接收管-光耦") (part "LED"))
    )
    (comp (ref "LED9")
      (value "绿色")
      (footprint "LED0805_B")
      (description "贴片LED")
      (libsource (lib "0.3 - LED发光二极管-IR二极管_接收管-光耦") (part "LED"))
    )
    (comp (ref "LED10")
      (value "绿色")
      (footprint "LED0805_B")
      (description "贴片LED")
      (libsource (lib "0.3 - LED发光二极管-IR二极管_接收管-光耦") (part "LED"))
    )
    (comp (ref "LED11")
      (value "绿色")
      (footprint "LED0805_B")
      (description "贴片LED")
      (libsource (lib "0.3 - LED发光二极管-IR二极管_接收管-光耦") (part "LED"))
    )
    (comp (ref "LED12")
      (value "绿色")
      (footprint "LED0805_B")
      (description "贴片LED")
      (libsource (lib "0.3 - LED发光二极管-IR二极管_接收管-光耦") (part "LED"))
    )
    (comp (ref "LED13")
      (value "绿色")
      (footprint "LED0805_B")
      (description "贴片LED")
      (libsource (lib "0.3 - LED发光二极管-IR二极管_接收管-光耦") (part "LED"))
    )
    (comp (ref "LED14")
      (value "绿色")
      (footprint "LED0805_B")
      (description "贴片LED")
      (libsource (lib "0.3 - LED发光二极管-IR二极管_接收管-光耦") (part "LED"))
    )
    (comp (ref "LED15")
      (value "绿色")
      (footprint "LED0805_B")
      (description "贴片LED")
      (libsource (lib "0.3 - LED发光二极管-IR二极管_接收管-光耦") (part "LED"))
    )
    (comp (ref "LED16")
      (value "蓝色")
      (footprint "LED0805_B")
      (description "贴片LED")
      (libsource (lib "0.3 - LED发光二极管-IR二极管_接收管-光耦") (part "LED"))
    )
    (comp (ref "LED17")
      (value "蓝色")
      (footprint "LED0805_B")
      (description "贴片LED")
      (libsource (lib "0.3 - LED发光二极管-IR二极管_接收管-光耦") (part "LED"))
    )
    (comp (ref "LED18")
      (value "红色")
      (footprint "LED0805_B")
      (description "贴片LED")
      (libsource (lib "0.3 - LED发光二极管-IR二极管_接收管-光耦") (part "LED"))
    )
    (comp (ref "LED19")
      (value "蓝色")
      (footprint "LED0805_B")
      (description "贴片LED")
      (libsource (lib "0.3 - LED发光二极管-IR二极管_接收管-光耦") (part "LED"))
    )
    (comp (ref "LED20")
      (value "红色")
      (footprint "LED0805_B")
      (description "贴片LED")
      (libsource (lib "0.3 - LED发光二极管-IR二极管_接收管-光耦") (part "LED"))
    )
    (comp (ref "LED21")
      (value "绿色")
      (footprint "LED0805_B")
      (description "贴片LED")
      (libsource (lib "0.3 - LED发光二极管-IR二极管_接收管-光耦") (part "LED"))
    )
    (comp (ref "LED22")
      (value "蓝色")
      (footprint "LED0805_B")
      (description "贴片LED")
      (libsource (lib "0.3 - LED发光二极管-IR二极管_接收管-光耦") (part "LED"))
    )
    (comp (ref "LED23")
      (value "红色")
      (footprint "LED0805_B")
      (description "贴片LED")
      (libsource (lib "0.3 - LED发光二极管-IR二极管_接收管-光耦") (part "LED"))
    )
    (comp (ref "LED24")
      (value "绿色")
      (footprint "LED0805_B")
      (description "贴片LED")
      (libsource (lib "0.3 - LED发光二极管-IR二极管_接收管-光耦") (part "LED"))
    )
    (comp (ref "LED25")
      (value "蓝色")
      (footprint "LED0805_B")
      (description "贴片LED")
      (libsource (lib "0.3 - LED发光二极管-IR二极管_接收管-光耦") (part "LED"))
    )
    (comp (ref "LED26")
      (value "红色")
      (footprint "LED0805_B")
      (description "贴片LED")
      (libsource (lib "0.3 - LED发光二极管-IR二极管_接收管-光耦") (part "LED"))
    )
    (comp (ref "LED27")
      (value "绿色")
      (footprint "LED0805_B")
      (description "贴片LED")
      (libsource (lib "0.3 - LED发光二极管-IR二极管_接收管-光耦") (part "LED"))
    )
    (comp (ref "LED28")
      (value "蓝色")
      (footprint "LED0805_B")
      (description "贴片LED")
      (libsource (lib "0.3 - LED发光二极管-IR二极管_接收管-光耦") (part "LED"))
    )
    (comp (ref "LED29")
      (value "绿色")
      (footprint "LED0805_B")
      (description "贴片LED")
      (libsource (lib "0.3 - LED发光二极管-IR二极管_接收管-光耦") (part "LED"))
    )
    (comp (ref "LED30")
      (value "蓝色")
      (footprint "LED0805_B")
      (description "贴片LED")
      (libsource (lib "0.3 - LED发光二极管-IR二极管_接收管-光耦") (part "LED"))
    )
    (comp (ref "LED31")
      (value "蓝色")
      (footprint "LED0805_B")
      (description "贴片LED")
      (libsource (lib "0.3 - LED发光二极管-IR二极管_接收管-光耦") (part "LED"))
    )
    (comp (ref "LED32")
      (value "红色")
      (footprint "LED0805_B")
      (description "贴片LED")
      (libsource (lib "0.3 - LED发光二极管-IR二极管_接收管-光耦") (part "LED"))
    )
    (comp (ref "LED33")
      (value "黄色")
      (footprint "LED0805_B")
      (description "贴片LED")
      (libsource (lib "0.3 - LED发光二极管-IR二极管_接收管-光耦") (part "LED"))
    )
    (comp (ref "LED34")
      (value "黄色")
      (footprint "LED0805_B")
      (description "贴片LED")
      (libsource (lib "0.3 - LED发光二极管-IR二极管_接收管-光耦") (part "LED"))
    )
    (comp (ref "LED35")
      (value "红色")
      (footprint "LED F257-W - duplicate")
      (description "贴片LED")
      (libsource (lib "0.3 - LED发光二极管-IR二极管_接收管-光耦") (part "LED"))
    )
    (comp (ref "LED36")
      (value "紫色")
      (footprint "LED0805_B")
      (description "贴片LED")
      (libsource (lib "0.3 - LED发光二极管-IR二极管_接收管-光耦") (part "LED"))
    )
    (comp (ref "LED37")
      (value "黄色")
      (footprint "LED0805_B")
      (description "贴片LED")
      (libsource (lib "0.3 - LED发光二极管-IR二极管_接收管-光耦") (part "LED"))
    )
    (comp (ref "LED38")
      (value "蓝色")
      (footprint "LED0805_B")
      (description "贴片LED")
      (libsource (lib "0.3 - LED发光二极管-IR二极管_接收管-光耦") (part "LED"))
    )
    (comp (ref "LED39")
      (value "蓝色")
      (footprint "LED0805_B")
      (description "贴片LED")
      (libsource (lib "0.3 - LED发光二极管-IR二极管_接收管-光耦") (part "LED"))
    )
    (comp (ref "LED40")
      (value "黄绿色")
      (footprint "LED0805_B")
      (description "贴片LED")
      (libsource (lib "0.3 - LED发光二极管-IR二极管_接收管-光耦") (part "LED"))
    )
    (comp (ref "LED41")
      (value "绿色")
      (footprint "LED0805_B")
      (description "贴片LED")
      (libsource (lib "0.3 - LED发光二极管-IR二极管_接收管-光耦") (part "LED"))
    )
    (comp (ref "LED42")
      (value "绿色")
      (footprint "LED0805_B")
      (description "贴片LED")
      (libsource (lib "0.3 - LED发光二极管-IR二极管_接收管-光耦") (part "LED"))
    )
    (comp (ref "LED43")
      (value "绿色")
      (footprint "LED F257-W - duplicate")
      (description "贴片LED")
      (libsource (lib "0.3 - LED发光二极管-IR二极管_接收管-光耦") (part "LED"))
    )
    (comp (ref "LED44")
      (value "蓝色")
      (footprint "LED F257-W - duplicate")
      (description "贴片LED")
      (libsource (lib "0.3 - LED发光二极管-IR二极管_接收管-光耦") (part "LED"))
    )
    (comp (ref "LED45")
      (value "蓝色")
      (footprint "LED0805_B")
      (description "贴片LED")
      (libsource (lib "0.3 - LED发光二极管-IR二极管_接收管-光耦") (part "LED"))
    )
    (comp (ref "LED46")
      (value "蓝色")
      (footprint "LED0805_B")
      (description "贴片LED")
      (libsource (lib "0.3 - LED发光二极管-IR二极管_接收管-光耦") (part "LED"))
    )
    (comp (ref "LED47")
      (value "黄绿色")
      (footprint "LED0805_B")
      (description "贴片LED")
      (libsource (lib "0.3 - LED发光二极管-IR二极管_接收管-光耦") (part "LED"))
    )
    (comp (ref "LED48")
      (value "绿色")
      (footprint "LED0805_B")
      (description "贴片LED")
      (libsource (lib "0.3 - LED发光二极管-IR二极管_接收管-光耦") (part "LED"))
    )
    (comp (ref "LED49")
      (value "绿色")
      (footprint "LED0805_B")
      (description "贴片LED")
      (libsource (lib "0.3 - LED发光二极管-IR二极管_接收管-光耦") (part "LED"))
    )
    (comp (ref "LED50")
      (value "绿色")
      (footprint "LED F257-W - duplicate")
      (description "贴片LED")
      (libsource (lib "0.3 - LED发光二极管-IR二极管_接收管-光耦") (part "LED"))
    )
    (comp (ref "LED51")
      (value "蓝色")
      (footprint "LED F257-W - duplicate")
      (description "贴片LED")
      (libsource (lib "0.3 - LED发光二极管-IR二极管_接收管-光耦") (part "LED"))
    )
    (comp (ref "LED52")
      (value "蓝色")
      (footprint "LED0805_B")
      (description "贴片LED")
      (libsource (lib "0.3 - LED发光二极管-IR二极管_接收管-光耦") (part "LED"))
    )
    (comp (ref "LED53")
      (value "蓝色")
      (footprint "LED0805_B")
      (description "贴片LED")
      (libsource (lib "0.3 - LED发光二极管-IR二极管_接收管-光耦") (part "LED"))
    )
    (comp (ref "LED54")
      (value "黄绿色")
      (footprint "LED0805_B")
      (description "贴片LED")
      (libsource (lib "0.3 - LED发光二极管-IR二极管_接收管-光耦") (part "LED"))
    )
    (comp (ref "LED55")
      (value "绿色")
      (footprint "LED0805_B")
      (description "贴片LED")
      (libsource (lib "0.3 - LED发光二极管-IR二极管_接收管-光耦") (part "LED"))
    )
    (comp (ref "LED56")
      (value "绿色")
      (footprint "LED0805_B")
      (description "贴片LED")
      (libsource (lib "0.3 - LED发光二极管-IR二极管_接收管-光耦") (part "LED"))
    )
    (comp (ref "LED57")
      (value "绿色")
      (footprint "LED F257-W - duplicate")
      (description "贴片LED")
      (libsource (lib "0.3 - LED发光二极管-IR二极管_接收管-光耦") (part "LED"))
    )
    (comp (ref "LED58")
      (value "蓝色")
      (footprint "LED F257-W - duplicate")
      (description "贴片LED")
      (libsource (lib "0.3 - LED发光二极管-IR二极管_接收管-光耦") (part "LED"))
    )
    (comp (ref "LED59")
      (value "蓝色")
      (footprint "LED0805_B")
      (description "贴片LED")
      (libsource (lib "0.3 - LED发光二极管-IR二极管_接收管-光耦") (part "LED"))
    )
    (comp (ref "LED60")
      (value "蓝色")
      (footprint "LED0805_B")
      (description "贴片LED")
      (libsource (lib "0.3 - LED发光二极管-IR二极管_接收管-光耦") (part "LED"))
    )
    (comp (ref "LED61")
      (value "黄绿色")
      (footprint "LED0805_B")
      (description "贴片LED")
      (libsource (lib "0.3 - LED发光二极管-IR二极管_接收管-光耦") (part "LED"))
    )
    (comp (ref "LED62")
      (value "绿色")
      (footprint "LED0805_B")
      (description "贴片LED")
      (libsource (lib "0.3 - LED发光二极管-IR二极管_接收管-光耦") (part "LED"))
    )
    (comp (ref "LED63")
      (value "绿色")
      (footprint "LED0805_B")
      (description "贴片LED")
      (libsource (lib "0.3 - LED发光二极管-IR二极管_接收管-光耦") (part "LED"))
    )
    (comp (ref "LED64")
      (value "绿色")
      (footprint "LED F257-W - duplicate")
      (description "贴片LED")
      (libsource (lib "0.3 - LED发光二极管-IR二极管_接收管-光耦") (part "LED"))
    )
    (comp (ref "LED65")
      (value "蓝色")
      (footprint "LED F257-W - duplicate")
      (description "贴片LED")
      (libsource (lib "0.3 - LED发光二极管-IR二极管_接收管-光耦") (part "LED"))
    )
    (comp (ref "LED66")
      (value "绿色")
      (footprint "LED0805_B")
      (description "贴片LED")
      (libsource (lib "0.3 - LED发光二极管-IR二极管_接收管-光耦") (part "LED"))
    )
    (comp (ref "LED67")
      (value "绿色")
      (footprint "LED0805_B")
      (description "贴片LED")
      (libsource (lib "0.3 - LED发光二极管-IR二极管_接收管-光耦") (part "LED"))
    )
    (comp (ref "LED68")
      (value "绿色")
      (footprint "LED0805_B")
      (description "贴片LED")
      (libsource (lib "0.3 - LED发光二极管-IR二极管_接收管-光耦") (part "LED"))
    )
    (comp (ref "LED69")
      (value "绿色")
      (footprint "LED0805_B")
      (description "贴片LED")
      (libsource (lib "0.3 - LED发光二极管-IR二极管_接收管-光耦") (part "LED"))
    )
    (comp (ref "LED70")
      (value "绿色")
      (footprint "LED0805_B")
      (description "贴片LED")
      (libsource (lib "0.3 - LED发光二极管-IR二极管_接收管-光耦") (part "LED"))
    )
    (comp (ref "LED71")
      (value "绿色")
      (footprint "LED0805_B")
      (description "贴片LED")
      (libsource (lib "0.3 - LED发光二极管-IR二极管_接收管-光耦") (part "LED"))
    )
    (comp (ref "LED72")
      (value "绿色")
      (footprint "LED0805_B")
      (description "贴片LED")
      (libsource (lib "0.3 - LED发光二极管-IR二极管_接收管-光耦") (part "LED"))
    )
    (comp (ref "LED73")
      (value "绿色")
      (footprint "LED0805_B")
      (description "贴片LED")
      (libsource (lib "0.3 - LED发光二极管-IR二极管_接收管-光耦") (part "LED"))
    )
    (comp (ref "LED74")
      (value "紫色")
      (footprint "LED0805_B")
      (description "贴片LED")
      (libsource (lib "0.3 - LED发光二极管-IR二极管_接收管-光耦") (part "LED"))
    )
    (comp (ref "LED75")
      (value "红色")
      (footprint "LED0805_B")
      (description "贴片LED")
      (libsource (lib "0.3 - LED发光二极管-IR二极管_接收管-光耦") (part "LED"))
    )
    (comp (ref "LED76")
      (value "红色")
      (footprint "LED0805_B")
      (description "贴片LED")
      (libsource (lib "0.3 - LED发光二极管-IR二极管_接收管-光耦") (part "LED"))
    )
    (comp (ref "LED77")
      (value "红色")
      (footprint "LED0805_B")
      (description "贴片LED")
      (libsource (lib "0.3 - LED发光二极管-IR二极管_接收管-光耦") (part "LED"))
    )
    (comp (ref "LED78")
      (value "红色")
      (footprint "LED0805_B")
      (description "贴片LED")
      (libsource (lib "0.3 - LED发光二极管-IR二极管_接收管-光耦") (part "LED"))
    )
    (comp (ref "R1")
      (value "10K")
      (footprint "R0805_L")
      (description "贴片电阻")
      (libsource (lib "0.1 - 电阻-电容-电感-保险丝-晶振-晶体-磁珠-电位器-法拉电容-馈通电容") (part "R"))
    )
    (comp (ref "R2")
      (value "10K")
      (footprint "R0805_L")
      (description "贴片电阻")
      (libsource (lib "0.1 - 电阻-电容-电感-保险丝-晶振-晶体-磁珠-电位器-法拉电容-馈通电容") (part "R"))
    )
    (comp (ref "R3")
      (value "10K")
      (footprint "R0805_L")
      (description "贴片电阻")
      (libsource (lib "0.1 - 电阻-电容-电感-保险丝-晶振-晶体-磁珠-电位器-法拉电容-馈通电容") (part "R"))
    )
    (comp (ref "R4")
      (value "10K")
      (footprint "R0805_L")
      (description "贴片电阻")
      (libsource (lib "0.1 - 电阻-电容-电感-保险丝-晶振-晶体-磁珠-电位器-法拉电容-馈通电容") (part "R"))
    )
    (comp (ref "R5")
      (value "10K")
      (footprint "R0805_L")
      (description "贴片电阻")
      (libsource (lib "0.1 - 电阻-电容-电感-保险丝-晶振-晶体-磁珠-电位器-法拉电容-馈通电容") (part "R"))
    )
    (comp (ref "R6")
      (value "10K")
      (footprint "R0805_L")
      (description "贴片电阻")
      (libsource (lib "0.1 - 电阻-电容-电感-保险丝-晶振-晶体-磁珠-电位器-法拉电容-馈通电容") (part "R"))
    )
    (comp (ref "R7")
      (value "10K")
      (footprint "R0805_L")
      (description "贴片电阻")
      (libsource (lib "0.1 - 电阻-电容-电感-保险丝-晶振-晶体-磁珠-电位器-法拉电容-馈通电容") (part "R"))
    )
    (comp (ref "R8")
      (value "10K")
      (footprint "R0805_L")
      (description "贴片电阻")
      (libsource (lib "0.1 - 电阻-电容-电感-保险丝-晶振-晶体-磁珠-电位器-法拉电容-馈通电容") (part "R"))
    )
    (comp (ref "R9")
      (value "3K9")
      (footprint "R0805_L")
      (description "贴片电阻")
      (libsource (lib "0.1 - 电阻-电容-电感-保险丝-晶振-晶体-磁珠-电位器-法拉电容-馈通电容") (part "R"))
    )
    (comp (ref "R10")
      (value "3K9")
      (footprint "R0805_L")
      (description "贴片电阻")
      (libsource (lib "0.1 - 电阻-电容-电感-保险丝-晶振-晶体-磁珠-电位器-法拉电容-馈通电容") (part "R"))
    )
    (comp (ref "R11")
      (value "3K9")
      (footprint "R0805_L")
      (description "贴片电阻")
      (libsource (lib "0.1 - 电阻-电容-电感-保险丝-晶振-晶体-磁珠-电位器-法拉电容-馈通电容") (part "R"))
    )
    (comp (ref "R12")
      (value "3K9")
      (footprint "R0805_L")
      (description "贴片电阻")
      (libsource (lib "0.1 - 电阻-电容-电感-保险丝-晶振-晶体-磁珠-电位器-法拉电容-馈通电容") (part "R"))
    )
    (comp (ref "R13")
      (value "3K9")
      (footprint "R0805_L")
      (description "贴片电阻")
      (libsource (lib "0.1 - 电阻-电容-电感-保险丝-晶振-晶体-磁珠-电位器-法拉电容-馈通电容") (part "R"))
    )
    (comp (ref "R14")
      (value "3K9")
      (footprint "R0805_L")
      (description "贴片电阻")
      (libsource (lib "0.1 - 电阻-电容-电感-保险丝-晶振-晶体-磁珠-电位器-法拉电容-馈通电容") (part "R"))
    )
    (comp (ref "R15")
      (value "3K9")
      (footprint "R0805_L")
      (description "贴片电阻")
      (libsource (lib "0.1 - 电阻-电容-电感-保险丝-晶振-晶体-磁珠-电位器-法拉电容-馈通电容") (part "R"))
    )
    (comp (ref "R16")
      (value "3K9")
      (footprint "R0805_L")
      (description "贴片电阻")
      (libsource (lib "0.1 - 电阻-电容-电感-保险丝-晶振-晶体-磁珠-电位器-法拉电容-馈通电容") (part "R"))
    )
    (comp (ref "R17")
      (value "3K9")
      (footprint "R0805_L")
      (description "贴片电阻")
      (libsource (lib "0.1 - 电阻-电容-电感-保险丝-晶振-晶体-磁珠-电位器-法拉电容-馈通电容") (part "R"))
    )
    (comp (ref "R18")
      (value "3K9")
      (footprint "R0805_L")
      (description "贴片电阻")
      (libsource (lib "0.1 - 电阻-电容-电感-保险丝-晶振-晶体-磁珠-电位器-法拉电容-馈通电容") (part "R"))
    )
    (comp (ref "R19")
      (value "3K9")
      (footprint "R0805_L")
      (description "贴片电阻")
      (libsource (lib "0.1 - 电阻-电容-电感-保险丝-晶振-晶体-磁珠-电位器-法拉电容-馈通电容") (part "R"))
    )
    (comp (ref "R20")
      (value "3K9")
      (footprint "R0805_L")
      (description "贴片电阻")
      (libsource (lib "0.1 - 电阻-电容-电感-保险丝-晶振-晶体-磁珠-电位器-法拉电容-馈通电容") (part "R"))
    )
    (comp (ref "R21")
      (value "3K9")
      (footprint "R0805_L")
      (description "贴片电阻")
      (libsource (lib "0.1 - 电阻-电容-电感-保险丝-晶振-晶体-磁珠-电位器-法拉电容-馈通电容") (part "R"))
    )
    (comp (ref "R22")
      (value "3K9")
      (footprint "R0805_L")
      (description "贴片电阻")
      (libsource (lib "0.1 - 电阻-电容-电感-保险丝-晶振-晶体-磁珠-电位器-法拉电容-馈通电容") (part "R"))
    )
    (comp (ref "R23")
      (value "3K9")
      (footprint "R0805_L")
      (description "贴片电阻")
      (libsource (lib "0.1 - 电阻-电容-电感-保险丝-晶振-晶体-磁珠-电位器-法拉电容-馈通电容") (part "R"))
    )
    (comp (ref "R24")
      (value "3K9")
      (footprint "R0805_L")
      (description "贴片电阻")
      (libsource (lib "0.1 - 电阻-电容-电感-保险丝-晶振-晶体-磁珠-电位器-法拉电容-馈通电容") (part "R"))
    )
    (comp (ref "R25")
      (value "1K")
      (footprint "R0805_L")
      (description "贴片电阻")
      (libsource (lib "0.1 - 电阻-电容-电感-保险丝-晶振-晶体-磁珠-电位器-法拉电容-馈通电容") (part "R"))
    )
    (comp (ref "R26")
      (value "1K")
      (footprint "R0805_L")
      (description "贴片电阻")
      (libsource (lib "0.1 - 电阻-电容-电感-保险丝-晶振-晶体-磁珠-电位器-法拉电容-馈通电容") (part "R"))
    )
    (comp (ref "R27")
      (value "1K")
      (footprint "R0805_L")
      (description "贴片电阻")
      (libsource (lib "0.1 - 电阻-电容-电感-保险丝-晶振-晶体-磁珠-电位器-法拉电容-馈通电容") (part "R"))
    )
    (comp (ref "R28")
      (value "1K")
      (footprint "R0805_L")
      (description "贴片电阻")
      (libsource (lib "0.1 - 电阻-电容-电感-保险丝-晶振-晶体-磁珠-电位器-法拉电容-馈通电容") (part "R"))
    )
    (comp (ref "R29")
      (value "1K")
      (footprint "R0805_L")
      (description "贴片电阻")
      (libsource (lib "0.1 - 电阻-电容-电感-保险丝-晶振-晶体-磁珠-电位器-法拉电容-馈通电容") (part "R"))
    )
    (comp (ref "R30")
      (value "3K9")
      (footprint "R0805_L")
      (description "贴片电阻")
      (libsource (lib "0.1 - 电阻-电容-电感-保险丝-晶振-晶体-磁珠-电位器-法拉电容-馈通电容") (part "R"))
    )
    (comp (ref "R31")
      (value "1K")
      (footprint "R0805_L")
      (description "贴片电阻")
      (libsource (lib "0.1 - 电阻-电容-电感-保险丝-晶振-晶体-磁珠-电位器-法拉电容-馈通电容") (part "R"))
    )
    (comp (ref "R32")
      (value "1K")
      (footprint "R0805_L")
      (description "贴片电阻")
      (libsource (lib "0.1 - 电阻-电容-电感-保险丝-晶振-晶体-磁珠-电位器-法拉电容-馈通电容") (part "R"))
    )
    (comp (ref "R33")
      (value "3K9")
      (footprint "R0805_L")
      (description "贴片电阻")
      (libsource (lib "0.1 - 电阻-电容-电感-保险丝-晶振-晶体-磁珠-电位器-法拉电容-馈通电容") (part "R"))
    )
    (comp (ref "R34")
      (value "1K")
      (footprint "R0805_L")
      (description "贴片电阻")
      (libsource (lib "0.1 - 电阻-电容-电感-保险丝-晶振-晶体-磁珠-电位器-法拉电容-馈通电容") (part "R"))
    )
    (comp (ref "R35")
      (value "1K")
      (footprint "R0805_L")
      (description "贴片电阻")
      (libsource (lib "0.1 - 电阻-电容-电感-保险丝-晶振-晶体-磁珠-电位器-法拉电容-馈通电容") (part "R"))
    )
    (comp (ref "R36")
      (value "3K9")
      (footprint "R0805_L")
      (description "贴片电阻")
      (libsource (lib "0.1 - 电阻-电容-电感-保险丝-晶振-晶体-磁珠-电位器-法拉电容-馈通电容") (part "R"))
    )
    (comp (ref "R37")
      (value "1K")
      (footprint "R0805_L")
      (description "贴片电阻")
      (libsource (lib "0.1 - 电阻-电容-电感-保险丝-晶振-晶体-磁珠-电位器-法拉电容-馈通电容") (part "R"))
    )
    (comp (ref "R38")
      (value "3K9")
      (footprint "R0805_L")
      (description "贴片电阻")
      (libsource (lib "0.1 - 电阻-电容-电感-保险丝-晶振-晶体-磁珠-电位器-法拉电容-馈通电容") (part "R"))
    )
    (comp (ref "R39")
      (value "1K")
      (footprint "R0805_L")
      (description "贴片电阻")
      (libsource (lib "0.1 - 电阻-电容-电感-保险丝-晶振-晶体-磁珠-电位器-法拉电容-馈通电容") (part "R"))
    )
    (comp (ref "R40")
      (value "1K")
      (footprint "R0805_L")
      (description "贴片电阻")
      (libsource (lib "0.1 - 电阻-电容-电感-保险丝-晶振-晶体-磁珠-电位器-法拉电容-馈通电容") (part "R"))
    )
    (comp (ref "R41")
      (value "1K")
      (footprint "R0805_L")
      (description "贴片电阻")
      (libsource (lib "0.1 - 电阻-电容-电感-保险丝-晶振-晶体-磁珠-电位器-法拉电容-馈通电容") (part "R"))
    )
    (comp (ref "R42")
      (value "820R")
      (footprint "R0805_L")
      (description "贴片电阻")
      (libsource (lib "0.1 - 电阻-电容-电感-保险丝-晶振-晶体-磁珠-电位器-法拉电容-馈通电容") (part "R"))
    )
    (comp (ref "R43")
      (value "820R")
      (footprint "R0805_L")
      (description "贴片电阻")
      (libsource (lib "0.1 - 电阻-电容-电感-保险丝-晶振-晶体-磁珠-电位器-法拉电容-馈通电容") (part "R"))
    )
    (comp (ref "R44")
      (value "1K")
      (footprint "R0805_L")
      (description "贴片电阻")
      (libsource (lib "0.1 - 电阻-电容-电感-保险丝-晶振-晶体-磁珠-电位器-法拉电容-馈通电容") (part "R"))
    )
    (comp (ref "R45")
      (value "1K")
      (footprint "R0805_L")
      (description "贴片电阻")
      (libsource (lib "0.1 - 电阻-电容-电感-保险丝-晶振-晶体-磁珠-电位器-法拉电容-馈通电容") (part "R"))
    )
    (comp (ref "R46")
      (value "820R")
      (footprint "R0805_L")
      (description "贴片电阻")
      (libsource (lib "0.1 - 电阻-电容-电感-保险丝-晶振-晶体-磁珠-电位器-法拉电容-馈通电容") (part "R"))
    )
    (comp (ref "R47")
      (value "1K")
      (footprint "R0805_L")
      (description "贴片电阻")
      (libsource (lib "0.1 - 电阻-电容-电感-保险丝-晶振-晶体-磁珠-电位器-法拉电容-馈通电容") (part "R"))
    )
    (comp (ref "R48")
      (value "1K")
      (footprint "R0805_L")
      (description "贴片电阻")
      (libsource (lib "0.1 - 电阻-电容-电感-保险丝-晶振-晶体-磁珠-电位器-法拉电容-馈通电容") (part "R"))
    )
    (comp (ref "R49")
      (value "220R")
      (footprint "R0805_L")
      (description "贴片电阻")
      (libsource (lib "0.1 - 电阻-电容-电感-保险丝-晶振-晶体-磁珠-电位器-法拉电容-馈通电容") (part "R"))
    )
    (comp (ref "R50")
      (value "3K9")
      (footprint "R0805_L")
      (description "贴片电阻")
      (libsource (lib "0.1 - 电阻-电容-电感-保险丝-晶振-晶体-磁珠-电位器-法拉电容-馈通电容") (part "R"))
    )
    (comp (ref "R51")
      (value "3K9")
      (footprint "R0805_L")
      (description "贴片电阻")
      (libsource (lib "0.1 - 电阻-电容-电感-保险丝-晶振-晶体-磁珠-电位器-法拉电容-馈通电容") (part "R"))
    )
    (comp (ref "R52")
      (value "3K9")
      (footprint "R0805_L")
      (description "贴片电阻")
      (libsource (lib "0.1 - 电阻-电容-电感-保险丝-晶振-晶体-磁珠-电位器-法拉电容-馈通电容") (part "R"))
    )
    (comp (ref "R53")
      (value "1K")
      (footprint "R0805_L")
      (description "贴片电阻")
      (libsource (lib "0.1 - 电阻-电容-电感-保险丝-晶振-晶体-磁珠-电位器-法拉电容-馈通电容") (part "R"))
    )
    (comp (ref "R54")
      (value "1K")
      (footprint "R0805_L")
      (description "贴片电阻")
      (libsource (lib "0.1 - 电阻-电容-电感-保险丝-晶振-晶体-磁珠-电位器-法拉电容-馈通电容") (part "R"))
    )
    (comp (ref "R55")
      (value "1K")
      (footprint "R0805_L")
      (description "贴片电阻")
      (libsource (lib "0.1 - 电阻-电容-电感-保险丝-晶振-晶体-磁珠-电位器-法拉电容-馈通电容") (part "R"))
    )
    (comp (ref "R56")
      (value "220R")
      (footprint "R0805_L")
      (description "贴片电阻")
      (libsource (lib "0.1 - 电阻-电容-电感-保险丝-晶振-晶体-磁珠-电位器-法拉电容-馈通电容") (part "R"))
    )
    (comp (ref "R57")
      (value "3K9")
      (footprint "R0805_L")
      (description "贴片电阻")
      (libsource (lib "0.1 - 电阻-电容-电感-保险丝-晶振-晶体-磁珠-电位器-法拉电容-馈通电容") (part "R"))
    )
    (comp (ref "R58")
      (value "3K9")
      (footprint "R0805_L")
      (description "贴片电阻")
      (libsource (lib "0.1 - 电阻-电容-电感-保险丝-晶振-晶体-磁珠-电位器-法拉电容-馈通电容") (part "R"))
    )
    (comp (ref "R59")
      (value "3K9")
      (footprint "R0805_L")
      (description "贴片电阻")
      (libsource (lib "0.1 - 电阻-电容-电感-保险丝-晶振-晶体-磁珠-电位器-法拉电容-馈通电容") (part "R"))
    )
    (comp (ref "R60")
      (value "1K")
      (footprint "R0805_L")
      (description "贴片电阻")
      (libsource (lib "0.1 - 电阻-电容-电感-保险丝-晶振-晶体-磁珠-电位器-法拉电容-馈通电容") (part "R"))
    )
    (comp (ref "R61")
      (value "1K")
      (footprint "R0805_L")
      (description "贴片电阻")
      (libsource (lib "0.1 - 电阻-电容-电感-保险丝-晶振-晶体-磁珠-电位器-法拉电容-馈通电容") (part "R"))
    )
    (comp (ref "R62")
      (value "1K")
      (footprint "R0805_L")
      (description "贴片电阻")
      (libsource (lib "0.1 - 电阻-电容-电感-保险丝-晶振-晶体-磁珠-电位器-法拉电容-馈通电容") (part "R"))
    )
    (comp (ref "R63")
      (value "220R")
      (footprint "R0805_L")
      (description "贴片电阻")
      (libsource (lib "0.1 - 电阻-电容-电感-保险丝-晶振-晶体-磁珠-电位器-法拉电容-馈通电容") (part "R"))
    )
    (comp (ref "R64")
      (value "3K9")
      (footprint "R0805_L")
      (description "贴片电阻")
      (libsource (lib "0.1 - 电阻-电容-电感-保险丝-晶振-晶体-磁珠-电位器-法拉电容-馈通电容") (part "R"))
    )
    (comp (ref "R65")
      (value "3K9")
      (footprint "R0805_L")
      (description "贴片电阻")
      (libsource (lib "0.1 - 电阻-电容-电感-保险丝-晶振-晶体-磁珠-电位器-法拉电容-馈通电容") (part "R"))
    )
    (comp (ref "R66")
      (value "3K9")
      (footprint "R0805_L")
      (description "贴片电阻")
      (libsource (lib "0.1 - 电阻-电容-电感-保险丝-晶振-晶体-磁珠-电位器-法拉电容-馈通电容") (part "R"))
    )
    (comp (ref "R67")
      (value "1K")
      (footprint "R0805_L")
      (description "贴片电阻")
      (libsource (lib "0.1 - 电阻-电容-电感-保险丝-晶振-晶体-磁珠-电位器-法拉电容-馈通电容") (part "R"))
    )
    (comp (ref "R68")
      (value "1K")
      (footprint "R0805_L")
      (description "贴片电阻")
      (libsource (lib "0.1 - 电阻-电容-电感-保险丝-晶振-晶体-磁珠-电位器-法拉电容-馈通电容") (part "R"))
    )
    (comp (ref "R69")
      (value "1K")
      (footprint "R0805_L")
      (description "贴片电阻")
      (libsource (lib "0.1 - 电阻-电容-电感-保险丝-晶振-晶体-磁珠-电位器-法拉电容-馈通电容") (part "R"))
    )
    (comp (ref "R70")
      (value "220R")
      (footprint "R0805_L")
      (description "贴片电阻")
      (libsource (lib "0.1 - 电阻-电容-电感-保险丝-晶振-晶体-磁珠-电位器-法拉电容-馈通电容") (part "R"))
    )
    (comp (ref "R71")
      (value "3K9")
      (footprint "R0805_L")
      (description "贴片电阻")
      (libsource (lib "0.1 - 电阻-电容-电感-保险丝-晶振-晶体-磁珠-电位器-法拉电容-馈通电容") (part "R"))
    )
    (comp (ref "R72")
      (value "3K9")
      (footprint "R0805_L")
      (description "贴片电阻")
      (libsource (lib "0.1 - 电阻-电容-电感-保险丝-晶振-晶体-磁珠-电位器-法拉电容-馈通电容") (part "R"))
    )
    (comp (ref "R73")
      (value "3K9")
      (footprint "R0805_L")
      (description "贴片电阻")
      (libsource (lib "0.1 - 电阻-电容-电感-保险丝-晶振-晶体-磁珠-电位器-法拉电容-馈通电容") (part "R"))
    )
    (comp (ref "R74")
      (value "1K")
      (footprint "R0805_L")
      (description "贴片电阻")
      (libsource (lib "0.1 - 电阻-电容-电感-保险丝-晶振-晶体-磁珠-电位器-法拉电容-馈通电容") (part "R"))
    )
    (comp (ref "R75")
      (value "1K")
      (footprint "R0805_L")
      (description "贴片电阻")
      (libsource (lib "0.1 - 电阻-电容-电感-保险丝-晶振-晶体-磁珠-电位器-法拉电容-馈通电容") (part "R"))
    )
    (comp (ref "R76")
      (value "10K")
      (footprint "R0805_L")
      (description "贴片电阻")
      (libsource (lib "0.1 - 电阻-电容-电感-保险丝-晶振-晶体-磁珠-电位器-法拉电容-馈通电容") (part "R"))
    )
    (comp (ref "R77")
      (value "100K")
      (footprint "R0805_L")
      (description "贴片电阻")
      (libsource (lib "0.1 - 电阻-电容-电感-保险丝-晶振-晶体-磁珠-电位器-法拉电容-馈通电容") (part "R"))
    )
    (comp (ref "R78")
      (value "100R")
      (footprint "R0805_L")
      (description "贴片电阻")
      (libsource (lib "0.1 - 电阻-电容-电感-保险丝-晶振-晶体-磁珠-电位器-法拉电容-馈通电容") (part "R"))
    )
    (comp (ref "R79")
      (value "1K")
      (footprint "R0805_L")
      (description "贴片电阻")
      (libsource (lib "0.1 - 电阻-电容-电感-保险丝-晶振-晶体-磁珠-电位器-法拉电容-馈通电容") (part "R"))
    )
    (comp (ref "R80")
      (value "100K")
      (footprint "R0805_L")
      (description "贴片电阻")
      (libsource (lib "0.1 - 电阻-电容-电感-保险丝-晶振-晶体-磁珠-电位器-法拉电容-馈通电容") (part "R"))
    )
    (comp (ref "R81")
      (value "100R")
      (footprint "R0805_L")
      (description "贴片电阻")
      (libsource (lib "0.1 - 电阻-电容-电感-保险丝-晶振-晶体-磁珠-电位器-法拉电容-馈通电容") (part "R"))
    )
    (comp (ref "R82")
      (value "1K")
      (footprint "R0805_L")
      (description "贴片电阻")
      (libsource (lib "0.1 - 电阻-电容-电感-保险丝-晶振-晶体-磁珠-电位器-法拉电容-馈通电容") (part "R"))
    )
    (comp (ref "R83")
      (value "1K")
      (footprint "R0805_L")
      (description "贴片电阻")
      (libsource (lib "0.1 - 电阻-电容-电感-保险丝-晶振-晶体-磁珠-电位器-法拉电容-馈通电容") (part "R"))
    )
    (comp (ref "R84")
      (value "1K")
      (footprint "R0805_L")
      (description "贴片电阻")
      (libsource (lib "0.1 - 电阻-电容-电感-保险丝-晶振-晶体-磁珠-电位器-法拉电容-馈通电容") (part "R"))
    )
    (comp (ref "R85")
      (value "10K")
      (footprint "R0805_L")
      (description "贴片电阻")
      (libsource (lib "0.1 - 电阻-电容-电感-保险丝-晶振-晶体-磁珠-电位器-法拉电容-馈通电容") (part "R"))
    )
    (comp (ref "R86")
      (value "10K")
      (footprint "R0805_L")
      (description "贴片电阻")
      (libsource (lib "0.1 - 电阻-电容-电感-保险丝-晶振-晶体-磁珠-电位器-法拉电容-馈通电容") (part "R"))
    )
    (comp (ref "R87")
      (value "10K")
      (footprint "R0805_L")
      (description "贴片电阻")
      (libsource (lib "0.1 - 电阻-电容-电感-保险丝-晶振-晶体-磁珠-电位器-法拉电容-馈通电容") (part "R"))
    )
    (comp (ref "R88")
      (value "10K")
      (footprint "R0805_L")
      (description "贴片电阻")
      (libsource (lib "0.1 - 电阻-电容-电感-保险丝-晶振-晶体-磁珠-电位器-法拉电容-馈通电容") (part "R"))
    )
    (comp (ref "R89")
      (value "3K9")
      (footprint "R0805_L")
      (description "贴片电阻")
      (libsource (lib "0.1 - 电阻-电容-电感-保险丝-晶振-晶体-磁珠-电位器-法拉电容-馈通电容") (part "R"))
    )
    (comp (ref "R90")
      (value "3K9")
      (footprint "R0805_L")
      (description "贴片电阻")
      (libsource (lib "0.1 - 电阻-电容-电感-保险丝-晶振-晶体-磁珠-电位器-法拉电容-馈通电容") (part "R"))
    )
    (comp (ref "R91")
      (value "3K9")
      (footprint "R0805_L")
      (description "贴片电阻")
      (libsource (lib "0.1 - 电阻-电容-电感-保险丝-晶振-晶体-磁珠-电位器-法拉电容-馈通电容") (part "R"))
    )
    (comp (ref "R92")
      (value "3K9")
      (footprint "R0805_L")
      (description "贴片电阻")
      (libsource (lib "0.1 - 电阻-电容-电感-保险丝-晶振-晶体-磁珠-电位器-法拉电容-馈通电容") (part "R"))
    )
    (comp (ref "R93")
      (value "3K9")
      (footprint "R0805_L")
      (description "贴片电阻")
      (libsource (lib "0.1 - 电阻-电容-电感-保险丝-晶振-晶体-磁珠-电位器-法拉电容-馈通电容") (part "R"))
    )
    (comp (ref "R94")
      (value "3K9")
      (footprint "R0805_L")
      (description "贴片电阻")
      (libsource (lib "0.1 - 电阻-电容-电感-保险丝-晶振-晶体-磁珠-电位器-法拉电容-馈通电容") (part "R"))
    )
    (comp (ref "R95")
      (value "3K9")
      (footprint "R0805_L")
      (description "贴片电阻")
      (libsource (lib "0.1 - 电阻-电容-电感-保险丝-晶振-晶体-磁珠-电位器-法拉电容-馈通电容") (part "R"))
    )
    (comp (ref "R96")
      (value "3K9")
      (footprint "R0805_L")
      (description "贴片电阻")
      (libsource (lib "0.1 - 电阻-电容-电感-保险丝-晶振-晶体-磁珠-电位器-法拉电容-馈通电容") (part "R"))
    )
    (comp (ref "R97")
      (value "1K")
      (footprint "R0805_L")
      (description "贴片电阻")
      (libsource (lib "0.1 - 电阻-电容-电感-保险丝-晶振-晶体-磁珠-电位器-法拉电容-馈通电容") (part "R"))
    )
    (comp (ref "R98")
      (value "1K")
      (footprint "R0805_L")
      (description "贴片电阻")
      (libsource (lib "0.1 - 电阻-电容-电感-保险丝-晶振-晶体-磁珠-电位器-法拉电容-馈通电容") (part "R"))
    )
    (comp (ref "R99")
      (value "1K")
      (footprint "R0805_L")
      (description "贴片电阻")
      (libsource (lib "0.1 - 电阻-电容-电感-保险丝-晶振-晶体-磁珠-电位器-法拉电容-馈通电容") (part "R"))
    )
    (comp (ref "R100")
      (value "1K")
      (footprint "R0805_L")
      (description "贴片电阻")
      (libsource (lib "0.1 - 电阻-电容-电感-保险丝-晶振-晶体-磁珠-电位器-法拉电容-馈通电容") (part "R"))
    )
    (comp (ref "R101")
      (value "1K")
      (footprint "R0805_L")
      (description "贴片电阻")
      (libsource (lib "0.1 - 电阻-电容-电感-保险丝-晶振-晶体-磁珠-电位器-法拉电容-馈通电容") (part "R"))
    )
    (comp (ref "RP1")
      (value "50K")
      (footprint "XV09223NPV-20F")
      (description "单联电位器")
      (libsource (lib "0.1 - 电阻-电容-电感-保险丝-晶振-晶体-磁珠-电位器-法拉电容-馈通电容") (part "RP"))
    )
    (comp (ref "S1")
      (value "SS-12F23")
      (footprint "SS-12D10")
      (description "1路波动开关")
      (libsource (lib "0.5 - 按键_开关_蜂鸣器_电池_测试点_Mark点_铜柱") (part "SSW-1P"))
    )
    (comp (ref "SW0")
      (value "DIP-SW-8P")
      (footprint "SW DIP-8P-B")
      (description "8路编码开关")
      (libsource (lib "0.5 - 按键_开关_蜂鸣器_电池_测试点_Mark点_铜柱") (part "DIP-SW-8P"))
    )
    (comp (ref "SW1")
      (value "DIP-SW-8P")
      (footprint "SW DIP-8P-B")
      (description "8路编码开关")
      (libsource (lib "0.5 - 按键_开关_蜂鸣器_电池_测试点_Mark点_铜柱") (part "DIP-SW-8P"))
    )
    (comp (ref "SW2")
      (value "DIP-SW-8P")
      (footprint "SW DIP-8P-B")
      (description "8路编码开关")
      (libsource (lib "0.5 - 按键_开关_蜂鸣器_电池_测试点_Mark点_铜柱") (part "DIP-SW-8P"))
    )
    (comp (ref "SW3")
      (value "DIP-SW-8P")
      (footprint "SW DIP-8P-B")
      (description "8路编码开关")
      (libsource (lib "0.5 - 按键_开关_蜂鸣器_电池_测试点_Mark点_铜柱") (part "DIP-SW-8P"))
    )
    (comp (ref "SW4")
      (value "DIP-SW-8P")
      (footprint "SW DIP-8P-B")
      (description "8路编码开关")
      (libsource (lib "0.5 - 按键_开关_蜂鸣器_电池_测试点_Mark点_铜柱") (part "DIP-SW-8P"))
    )
    (comp (ref "SW5")
      (value "DIP-SW-8P")
      (footprint "SW DIP-8P-B")
      (description "8路编码开关")
      (libsource (lib "0.5 - 按键_开关_蜂鸣器_电池_测试点_Mark点_铜柱") (part "DIP-SW-8P"))
    )
    (comp (ref "SW6")
      (value "DIP-SW-8P")
      (footprint "SW DIP-8P-B")
      (description "8路编码开关")
      (libsource (lib "0.5 - 按键_开关_蜂鸣器_电池_测试点_Mark点_铜柱") (part "DIP-SW-8P"))
    )
    (comp (ref "SW7")
      (value "DIP-SW-8P")
      (footprint "SW DIP-8P-B")
      (description "8路编码开关")
      (libsource (lib "0.5 - 按键_开关_蜂鸣器_电池_测试点_Mark点_铜柱") (part "DIP-SW-8P"))
    )
    (comp (ref "SW8")
      (value "DIP-SW-8P")
      (footprint "SW DIP-8P-B")
      (description "8路编码开关")
      (libsource (lib "0.5 - 按键_开关_蜂鸣器_电池_测试点_Mark点_铜柱") (part "DIP-SW-8P"))
    )
    (comp (ref "SW9")
      (value "DIP-SW-8P")
      (footprint "SW DIP-8P-B")
      (description "8路编码开关")
      (libsource (lib "0.5 - 按键_开关_蜂鸣器_电池_测试点_Mark点_铜柱") (part "DIP-SW-8P"))
    )
    (comp (ref "SW10")
      (value "DIP-SW-8P")
      (footprint "SW DIP-8P-B")
      (description "8路编码开关")
      (libsource (lib "0.5 - 按键_开关_蜂鸣器_电池_测试点_Mark点_铜柱") (part "DIP-SW-8P"))
    )
    (comp (ref "SW11")
      (value "DIP-SW-8P")
      (footprint "SW DIP-8P-B")
      (description "8路编码开关")
      (libsource (lib "0.5 - 按键_开关_蜂鸣器_电池_测试点_Mark点_铜柱") (part "DIP-SW-8P"))
    )
    (comp (ref "SW12")
      (value "DIP-SW-8P")
      (footprint "SW DIP-8P-B")
      (description "8路编码开关")
      (libsource (lib "0.5 - 按键_开关_蜂鸣器_电池_测试点_Mark点_铜柱") (part "DIP-SW-8P"))
    )
    (comp (ref "SW13")
      (value "DIP-SW-8P")
      (footprint "SW DIP-8P-B")
      (description "8路编码开关")
      (libsource (lib "0.5 - 按键_开关_蜂鸣器_电池_测试点_Mark点_铜柱") (part "DIP-SW-8P"))
    )
    (comp (ref "SW14")
      (value "DIP-SW-8P")
      (footprint "SW DIP-8P-B")
      (description "8路编码开关")
      (libsource (lib "0.5 - 按键_开关_蜂鸣器_电池_测试点_Mark点_铜柱") (part "DIP-SW-8P"))
    )
    (comp (ref "SW15")
      (value "DIP-SW-8P")
      (footprint "SW DIP-8P-B")
      (description "8路编码开关")
      (libsource (lib "0.5 - 按键_开关_蜂鸣器_电池_测试点_Mark点_铜柱") (part "DIP-SW-8P"))
    )
    (comp (ref "SW16")
      (value "Cherry")
      (footprint "LSW DIP-CHERRY-Hat")
      (description "带灯机械按键开关")
      (libsource (lib "0.5 - 按键_开关_蜂鸣器_电池_测试点_Mark点_铜柱") (part "LSW"))
    )
    (comp (ref "SW17")
      (value "Cherry")
      (footprint "LSW DIP-CHERRY-Hat")
      (description "带灯机械按键开关")
      (libsource (lib "0.5 - 按键_开关_蜂鸣器_电池_测试点_Mark点_铜柱") (part "LSW"))
    )
    (comp (ref "SW18")
      (value "DIP-SW-4P")
      (footprint "SW DIP-4P-B")
      (description "4路编码开关")
      (libsource (lib "0.5 - 按键_开关_蜂鸣器_电池_测试点_Mark点_铜柱") (part "DIP-SW-4P"))
    )
    (comp (ref "U1")
      (value "SN74HC540")
      (footprint "DIP20-300_MH")
      (description "OCTAL BUF AND LINE DRV 3SO")
      (libsource (lib "1.1 - 74系列TTL逻辑芯片") (part "SN74HC540"))
    )
    (comp (ref "U2")
      (value "SN74HC154")
      (footprint "DIP24-300_MH")
      (description "4-16LINE DEC DEMUL")
      (libsource (lib "1.1 - 74系列TTL逻辑芯片") (part "SN74HC154"))
    )
    (comp (ref "U3")
      (value "SN74HC32")
      (footprint "DIP14-300_MH")
      (description "Quad 2-IN Pos Or G")
      (libsource (lib "1.1 - 74系列TTL逻辑芯片") (part "SN74HC32"))
    )
    (comp (ref "U4")
      (value "SN74HC10")
      (footprint "DIP14-300_MH")
      (description "Triple 3-IN Pos Nand G")
      (libsource (lib "1.1 - 74系列TTL逻辑芯片") (part "SN74HC10"))
    )
    (comp (ref "U5")
      (value "SN74HC14")
      (footprint "DIP14-300_MH")
      (description "Hex Inverter SCH")
      (libsource (lib "1.1 - 74系列TTL逻辑芯片") (part "SN74HC14"))
    )
    (comp (ref "U6")
      (value "SN74HC161")
      (footprint "DIP16-300_MH")
      (description "SYN 4-BIT CNT")
      (libsource (lib "1.1 - 74系列TTL逻辑芯片") (part "SN74HC161"))
    )
    (comp (ref "U7")
      (value "SN74HC153")
      (footprint "DIP16-300_MH")
      (description "DUAL 4-1 LINE DATA SELEC/MUX")
      (libsource (lib "1.1 - 74系列TTL逻辑芯片") (part "SN74HC153"))
    )
    (comp (ref "U8")
      (value "SN74HC283")
      (footprint "DIP16-300_MH")
      (description "4-BIT BIN ADD WITH FC")
      (libsource (lib "1.1 - 74系列TTL逻辑芯片") (part "SN74HC283"))
    )
    (comp (ref "U9")
      (value "SN74HC74")
      (footprint "DIP14-300_MH")
      (description "DUAL D PET FF RS CR")
      (libsource (lib "1.1 - 74系列TTL逻辑芯片") (part "SN74HC74"))
    )
    (comp (ref "U10")
      (value "SN74HC161")
      (footprint "DIP16-300_MH")
      (description "SYN 4-BIT CNT")
      (libsource (lib "1.1 - 74系列TTL逻辑芯片") (part "SN74HC161"))
    )
    (comp (ref "U11")
      (value "SN74HC153")
      (footprint "DIP16-300_MH")
      (description "DUAL 4-1 LINE DATA SELEC/MUX")
      (libsource (lib "1.1 - 74系列TTL逻辑芯片") (part "SN74HC153"))
    )
    (comp (ref "U12")
      (value "SN74HC161")
      (footprint "DIP16-300_MH")
      (description "SYN 4-BIT CNT")
      (libsource (lib "1.1 - 74系列TTL逻辑芯片") (part "SN74HC161"))
    )
    (comp (ref "U13")
      (value "SN74HC161")
      (footprint "DIP16-300_MH")
      (description "SYN 4-BIT CNT")
      (libsource (lib "1.1 - 74系列TTL逻辑芯片") (part "SN74HC161"))
    )
    (comp (ref "USB1")
      (value "USB_TYPE-C_6Pin")
      (footprint "USB-C-SMD_6P")
      (description "USB_TYPE-C_6Pin母座")
      (libsource (lib "0.6 - 电源_音频_USB Type-C_HDMI_XT60_5557_D-SUB_RJ45_SD-TF_SIM插座") (part "USB_TYPE-C_6Pin"))
    )
  )
  (nets
    (net (code "1") (name "/ALU_A0") (class "Default")
      (node (ref "LED39") (pin "1") (pinfunction "A_1") (pintype "passive"))
      (node (ref "U7") (pin "7") (pinfunction "1Y_7") (pintype "output"))
      (node (ref "U8") (pin "5") (pinfunction "A1_5") (pintype "input"))
    )
    (net (code "2") (name "/ALU_A1") (class "Default")
      (node (ref "LED46") (pin "1") (pinfunction "A_1") (pintype "passive"))
      (node (ref "U7") (pin "9") (pinfunction "2Y_9") (pintype "output"))
      (node (ref "U8") (pin "3") (pinfunction "A2_3") (pintype "input"))
    )
    (net (code "3") (name "/ALU_A2") (class "Default")
      (node (ref "LED53") (pin "1") (pinfunction "A_1") (pintype "passive"))
      (node (ref "U11") (pin "7") (pinfunction "1Y_7") (pintype "output"))
      (node (ref "U8") (pin "14") (pinfunction "A3_14") (pintype "input"))
    )
    (net (code "4") (name "/ALU_A3") (class "Default")
      (node (ref "LED60") (pin "1") (pinfunction "A_1") (pintype "passive"))
      (node (ref "U11") (pin "9") (pinfunction "2Y_9") (pintype "output"))
      (node (ref "U8") (pin "12") (pinfunction "A4_12") (pintype "input"))
    )
    (net (code "5") (name "/ALU_OUT0") (class "Default")
      (node (ref "LED40") (pin "1") (pinfunction "A_1") (pintype "passive"))
      (node (ref "U10") (pin "3") (pinfunction "A_3") (pintype "input"))
      (node (ref "U12") (pin "3") (pinfunction "A_3") (pintype "input"))
      (node (ref "U13") (pin "3") (pinfunction "A_3") (pintype "input"))
      (node (ref "U6") (pin "3") (pinfunction "A_3") (pintype "input"))
      (node (ref "U8") (pin "4") (pintype "output"))
    )
    (net (code "6") (name "/ALU_OUT1") (class "Default")
      (node (ref "LED47") (pin "1") (pinfunction "A_1") (pintype "passive"))
      (node (ref "U10") (pin "4") (pinfunction "B_4") (pintype "input"))
      (node (ref "U12") (pin "4") (pinfunction "B_4") (pintype "input"))
      (node (ref "U13") (pin "4") (pinfunction "B_4") (pintype "input"))
      (node (ref "U6") (pin "4") (pinfunction "B_4") (pintype "input"))
      (node (ref "U8") (pin "1") (pintype "output"))
    )
    (net (code "7") (name "/ALU_OUT2") (class "Default")
      (node (ref "LED54") (pin "1") (pinfunction "A_1") (pintype "passive"))
      (node (ref "U10") (pin "5") (pinfunction "C_5") (pintype "input"))
      (node (ref "U12") (pin "5") (pinfunction "C_5") (pintype "input"))
      (node (ref "U13") (pin "5") (pinfunction "C_5") (pintype "input"))
      (node (ref "U6") (pin "5") (pinfunction "C_5") (pintype "input"))
      (node (ref "U8") (pin "13") (pintype "output"))
    )
    (net (code "8") (name "/ALU_OUT3") (class "Default")
      (node (ref "LED61") (pin "1") (pinfunction "A_1") (pintype "passive"))
      (node (ref "U10") (pin "6") (pinfunction "D_6") (pintype "input"))
      (node (ref "U12") (pin "6") (pinfunction "D_6") (pintype "input"))
      (node (ref "U13") (pin "6") (pinfunction "D_6") (pintype "input"))
      (node (ref "U6") (pin "6") (pinfunction "D_6") (pintype "input"))
      (node (ref "U8") (pin "10") (pintype "output"))
    )
    (net (code "9") (name "/A_REG_0") (class "Default")
      (node (ref "R50") (pin "2") (pinfunction "2_2") (pintype "passive"))
      (node (ref "U6") (pin "14") (pinfunction "QA_14") (pintype "output"))
      (node (ref "U7") (pin "6") (pinfunction "1CO_6") (pintype "input"))
    )
    (net (code "10") (name "/A_REG_1") (class "Default")
      (node (ref "R57") (pin "2") (pinfunction "2_2") (pintype "passive"))
      (node (ref "U6") (pin "13") (pinfunction "QB_13") (pintype "output"))
      (node (ref "U7") (pin "10") (pinfunction "2CO_10") (pintype "input"))
    )
    (net (code "11") (name "/A_REG_2") (class "Default")
      (node (ref "R64") (pin "2") (pinfunction "2_2") (pintype "passive"))
      (node (ref "U11") (pin "6") (pinfunction "1CO_6") (pintype "input"))
      (node (ref "U6") (pin "12") (pinfunction "QC_12") (pintype "output"))
    )
    (net (code "12") (name "/A_REG_3") (class "Default")
      (node (ref "R71") (pin "2") (pinfunction "2_2") (pintype "passive"))
      (node (ref "U11") (pin "10") (pinfunction "2CO_10") (pintype "input"))
      (node (ref "U6") (pin "11") (pinfunction "QD_11") (pintype "output"))
    )
    (net (code "13") (name "/Addr0") (class "Default")
      (node (ref "R30") (pin "2") (pinfunction "2_2") (pintype "passive"))
      (node (ref "R90") (pin "2") (pinfunction "2_2") (pintype "passive"))
      (node (ref "U13") (pin "14") (pinfunction "QA_14") (pintype "output"))
      (node (ref "U2") (pin "23") (pinfunction "A_23") (pintype "input"))
    )
    (net (code "14") (name "/Addr1") (class "Default")
      (node (ref "R33") (pin "2") (pinfunction "2_2") (pintype "passive"))
      (node (ref "R92") (pin "2") (pinfunction "2_2") (pintype "passive"))
      (node (ref "U13") (pin "13") (pinfunction "QB_13") (pintype "output"))
      (node (ref "U2") (pin "22") (pinfunction "B_22") (pintype "input"))
    )
    (net (code "15") (name "/Addr2") (class "Default")
      (node (ref "R36") (pin "2") (pinfunction "2_2") (pintype "passive"))
      (node (ref "R94") (pin "2") (pinfunction "2_2") (pintype "passive"))
      (node (ref "U13") (pin "12") (pinfunction "QC_12") (pintype "output"))
      (node (ref "U2") (pin "21") (pinfunction "C_21") (pintype "input"))
    )
    (net (code "16") (name "/Addr3") (class "Default")
      (node (ref "R38") (pin "2") (pinfunction "2_2") (pintype "passive"))
      (node (ref "R96") (pin "2") (pinfunction "2_2") (pintype "passive"))
      (node (ref "U13") (pin "11") (pinfunction "QD_11") (pintype "output"))
      (node (ref "U2") (pin "20") (pinfunction "D_20") (pintype "input"))
    )
    (net (code "17") (name "/B_REG_0") (class "Default")
      (node (ref "R51") (pin "2") (pinfunction "2_2") (pintype "passive"))
      (node (ref "U10") (pin "14") (pinfunction "QA_14") (pintype "output"))
      (node (ref "U7") (pin "5") (pinfunction "1C1_5") (pintype "input"))
    )
    (net (code "18") (name "/B_REG_1") (class "Default")
      (node (ref "R58") (pin "2") (pinfunction "2_2") (pintype "passive"))
      (node (ref "U10") (pin "13") (pinfunction "QB_13") (pintype "output"))
      (node (ref "U7") (pin "11") (pinfunction "2C1_11") (pintype "input"))
    )
    (net (code "19") (name "/B_REG_2") (class "Default")
      (node (ref "R65") (pin "2") (pinfunction "2_2") (pintype "passive"))
      (node (ref "U10") (pin "12") (pinfunction "QC_12") (pintype "output"))
      (node (ref "U11") (pin "5") (pinfunction "1C1_5") (pintype "input"))
    )
    (net (code "20") (name "/B_REG_3") (class "Default")
      (node (ref "R72") (pin "2") (pinfunction "2_2") (pintype "passive"))
      (node (ref "U10") (pin "11") (pinfunction "QD_11") (pintype "output"))
      (node (ref "U11") (pin "11") (pinfunction "2C1_11") (pintype "input"))
    )
    (net (code "21") (name "/C") (class "Default")
      (node (ref "LED37") (pin "1") (pinfunction "A_1") (pintype "passive"))
      (node (ref "U8") (pin "9") (pinfunction "C4_9") (pintype "output"))
      (node (ref "U9") (pin "12") (pinfunction "D_12") (pintype "input"))
    )
    (net (code "22") (name "/COM0") (class "Default")
      (node (ref "D1") (pin "2") (pinfunction "K_2") (pintype "passive"))
      (node (ref "D2") (pin "2") (pinfunction "K_2") (pintype "passive"))
      (node (ref "D3") (pin "2") (pinfunction "K_2") (pintype "passive"))
      (node (ref "D4") (pin "2") (pinfunction "K_2") (pintype "passive"))
      (node (ref "D5") (pin "2") (pinfunction "K_2") (pintype "passive"))
      (node (ref "D6") (pin "2") (pinfunction "K_2") (pintype "passive"))
      (node (ref "D7") (pin "2") (pinfunction "K_2") (pintype "passive"))
      (node (ref "D8") (pin "2") (pinfunction "K_2") (pintype "passive"))
      (node (ref "LED0") (pin "2") (pinfunction "K_2") (pintype "passive"))
      (node (ref "U2") (pin "1") (pinfunction "0_1") (pintype "output"))
    )
    (net (code "23") (name "/COM1") (class "Default")
      (node (ref "D10") (pin "2") (pinfunction "K_2") (pintype "passive"))
      (node (ref "D11") (pin "2") (pinfunction "K_2") (pintype "passive"))
      (node (ref "D12") (pin "2") (pinfunction "K_2") (pintype "passive"))
      (node (ref "D13") (pin "2") (pinfunction "K_2") (pintype "passive"))
      (node (ref "D14") (pin "2") (pinfunction "K_2") (pintype "passive"))
      (node (ref "D15") (pin "2") (pinfunction "K_2") (pintype "passive"))
      (node (ref "D16") (pin "2") (pinfunction "K_2") (pintype "passive"))
      (node (ref "D9") (pin "2") (pinfunction "K_2") (pintype "passive"))
      (node (ref "LED1") (pin "2") (pinfunction "K_2") (pintype "passive"))
      (node (ref "U2") (pin "2") (pinfunction "1_2") (pintype "output"))
    )
    (net (code "24") (name "/COM2") (class "Default")
      (node (ref "D17") (pin "2") (pinfunction "K_2") (pintype "passive"))
      (node (ref "D18") (pin "2") (pinfunction "K_2") (pintype "passive"))
      (node (ref "D19") (pin "2") (pinfunction "K_2") (pintype "passive"))
      (node (ref "D20") (pin "2") (pinfunction "K_2") (pintype "passive"))
      (node (ref "D21") (pin "2") (pinfunction "K_2") (pintype "passive"))
      (node (ref "D22") (pin "2") (pinfunction "K_2") (pintype "passive"))
      (node (ref "D23") (pin "2") (pinfunction "K_2") (pintype "passive"))
      (node (ref "D24") (pin "2") (pinfunction "K_2") (pintype "passive"))
      (node (ref "LED2") (pin "2") (pinfunction "K_2") (pintype "passive"))
      (node (ref "U2") (pin "3") (pinfunction "2_3") (pintype "output"))
    )
    (net (code "25") (name "/COM3") (class "Default")
      (node (ref "D25") (pin "2") (pinfunction "K_2") (pintype "passive"))
      (node (ref "D26") (pin "2") (pinfunction "K_2") (pintype "passive"))
      (node (ref "D27") (pin "2") (pinfunction "K_2") (pintype "passive"))
      (node (ref "D28") (pin "2") (pinfunction "K_2") (pintype "passive"))
      (node (ref "D29") (pin "2") (pinfunction "K_2") (pintype "passive"))
      (node (ref "D30") (pin "2") (pinfunction "K_2") (pintype "passive"))
      (node (ref "D31") (pin "2") (pinfunction "K_2") (pintype "passive"))
      (node (ref "D32") (pin "2") (pinfunction "K_2") (pintype "passive"))
      (node (ref "LED3") (pin "2") (pinfunction "K_2") (pintype "passive"))
      (node (ref "U2") (pin "4") (pinfunction "3_4") (pintype "output"))
    )
    (net (code "26") (name "/COM4") (class "Default")
      (node (ref "D33") (pin "2") (pinfunction "K_2") (pintype "passive"))
      (node (ref "D34") (pin "2") (pinfunction "K_2") (pintype "passive"))
      (node (ref "D35") (pin "2") (pinfunction "K_2") (pintype "passive"))
      (node (ref "D36") (pin "2") (pinfunction "K_2") (pintype "passive"))
      (node (ref "D37") (pin "2") (pinfunction "K_2") (pintype "passive"))
      (node (ref "D38") (pin "2") (pinfunction "K_2") (pintype "passive"))
      (node (ref "D39") (pin "2") (pinfunction "K_2") (pintype "passive"))
      (node (ref "D40") (pin "2") (pinfunction "K_2") (pintype "passive"))
      (node (ref "LED4") (pin "2") (pinfunction "K_2") (pintype "passive"))
      (node (ref "U2") (pin "5") (pinfunction "4_5") (pintype "output"))
    )
    (net (code "27") (name "/COM5") (class "Default")
      (node (ref "D41") (pin "2") (pinfunction "K_2") (pintype "passive"))
      (node (ref "D42") (pin "2") (pinfunction "K_2") (pintype "passive"))
      (node (ref "D43") (pin "2") (pinfunction "K_2") (pintype "passive"))
      (node (ref "D44") (pin "2") (pinfunction "K_2") (pintype "passive"))
      (node (ref "D45") (pin "2") (pinfunction "K_2") (pintype "passive"))
      (node (ref "D46") (pin "2") (pinfunction "K_2") (pintype "passive"))
      (node (ref "D47") (pin "2") (pinfunction "K_2") (pintype "passive"))
      (node (ref "D48") (pin "2") (pinfunction "K_2") (pintype "passive"))
      (node (ref "LED5") (pin "2") (pinfunction "K_2") (pintype "passive"))
      (node (ref "U2") (pin "6") (pinfunction "5_6") (pintype "output"))
    )
    (net (code "28") (name "/COM6") (class "Default")
      (node (ref "D49") (pin "2") (pinfunction "K_2") (pintype "passive"))
      (node (ref "D50") (pin "2") (pinfunction "K_2") (pintype "passive"))
      (node (ref "D51") (pin "2") (pinfunction "K_2") (pintype "passive"))
      (node (ref "D52") (pin "2") (pinfunction "K_2") (pintype "passive"))
      (node (ref "D53") (pin "2") (pinfunction "K_2") (pintype "passive"))
      (node (ref "D54") (pin "2") (pinfunction "K_2") (pintype "passive"))
      (node (ref "D55") (pin "2") (pinfunction "K_2") (pintype "passive"))
      (node (ref "D56") (pin "2") (pinfunction "K_2") (pintype "passive"))
      (node (ref "LED6") (pin "2") (pinfunction "K_2") (pintype "passive"))
      (node (ref "U2") (pin "7") (pinfunction "6_7") (pintype "output"))
    )
    (net (code "29") (name "/COM7") (class "Default")
      (node (ref "D57") (pin "2") (pinfunction "K_2") (pintype "passive"))
      (node (ref "D58") (pin "2") (pinfunction "K_2") (pintype "passive"))
      (node (ref "D59") (pin "2") (pinfunction "K_2") (pintype "passive"))
      (node (ref "D60") (pin "2") (pinfunction "K_2") (pintype "passive"))
      (node (ref "D61") (pin "2") (pinfunction "K_2") (pintype "passive"))
      (node (ref "D62") (pin "2") (pinfunction "K_2") (pintype "passive"))
      (node (ref "D63") (pin "2") (pinfunction "K_2") (pintype "passive"))
      (node (ref "D64") (pin "2") (pinfunction "K_2") (pintype "passive"))
      (node (ref "LED7") (pin "2") (pinfunction "K_2") (pintype "passive"))
      (node (ref "U2") (pin "8") (pinfunction "7_8") (pintype "output"))
    )
    (net (code "30") (name "/COM8") (class "Default")
      (node (ref "D65") (pin "2") (pinfunction "K_2") (pintype "passive"))
      (node (ref "D66") (pin "2") (pinfunction "K_2") (pintype "passive"))
      (node (ref "D67") (pin "2") (pinfunction "K_2") (pintype "passive"))
      (node (ref "D68") (pin "2") (pinfunction "K_2") (pintype "passive"))
      (node (ref "D69") (pin "2") (pinfunction "K_2") (pintype "passive"))
      (node (ref "D70") (pin "2") (pinfunction "K_2") (pintype "passive"))
      (node (ref "D71") (pin "2") (pinfunction "K_2") (pintype "passive"))
      (node (ref "D72") (pin "2") (pinfunction "K_2") (pintype "passive"))
      (node (ref "LED8") (pin "2") (pinfunction "K_2") (pintype "passive"))
      (node (ref "U2") (pin "9") (pinfunction "8_9") (pintype "output"))
    )
    (net (code "31") (name "/COM9") (class "Default")
      (node (ref "D73") (pin "2") (pinfunction "K_2") (pintype "passive"))
      (node (ref "D74") (pin "2") (pinfunction "K_2") (pintype "passive"))
      (node (ref "D75") (pin "2") (pinfunction "K_2") (pintype "passive"))
      (node (ref "D76") (pin "2") (pinfunction "K_2") (pintype "passive"))
      (node (ref "D77") (pin "2") (pinfunction "K_2") (pintype "passive"))
      (node (ref "D78") (pin "2") (pinfunction "K_2") (pintype "passive"))
      (node (ref "D79") (pin "2") (pinfunction "K_2") (pintype "passive"))
      (node (ref "D80") (pin "2") (pinfunction "K_2") (pintype "passive"))
      (node (ref "LED9") (pin "2") (pinfunction "K_2") (pintype "passive"))
      (node (ref "U2") (pin "10") (pinfunction "9_10") (pintype "output"))
    )
    (net (code "32") (name "/COM10") (class "Default")
      (node (ref "D81") (pin "2") (pinfunction "K_2") (pintype "passive"))
      (node (ref "D82") (pin "2") (pinfunction "K_2") (pintype "passive"))
      (node (ref "D83") (pin "2") (pinfunction "K_2") (pintype "passive"))
      (node (ref "D84") (pin "2") (pinfunction "K_2") (pintype "passive"))
      (node (ref "D85") (pin "2") (pinfunction "K_2") (pintype "passive"))
      (node (ref "D86") (pin "2") (pinfunction "K_2") (pintype "passive"))
      (node (ref "D87") (pin "2") (pinfunction "K_2") (pintype "passive"))
      (node (ref "D88") (pin "2") (pinfunction "K_2") (pintype "passive"))
      (node (ref "LED10") (pin "2") (pinfunction "K_2") (pintype "passive"))
      (node (ref "U2") (pin "11") (pinfunction "10_11") (pintype "output"))
    )
    (net (code "33") (name "/COM11") (class "Default")
      (node (ref "D89") (pin "2") (pinfunction "K_2") (pintype "passive"))
      (node (ref "D90") (pin "2") (pinfunction "K_2") (pintype "passive"))
      (node (ref "D91") (pin "2") (pinfunction "K_2") (pintype "passive"))
      (node (ref "D92") (pin "2") (pinfunction "K_2") (pintype "passive"))
      (node (ref "D93") (pin "2") (pinfunction "K_2") (pintype "passive"))
      (node (ref "D94") (pin "2") (pinfunction "K_2") (pintype "passive"))
      (node (ref "D95") (pin "2") (pinfunction "K_2") (pintype "passive"))
      (node (ref "D96") (pin "2") (pinfunction "K_2") (pintype "passive"))
      (node (ref "LED11") (pin "2") (pinfunction "K_2") (pintype "passive"))
      (node (ref "U2") (pin "13") (pinfunction "11_13") (pintype "output"))
    )
    (net (code "34") (name "/COM12") (class "Default")
      (node (ref "D100") (pin "2") (pinfunction "K_2") (pintype "passive"))
      (node (ref "D101") (pin "2") (pinfunction "K_2") (pintype "passive"))
      (node (ref "D102") (pin "2") (pinfunction "K_2") (pintype "passive"))
      (node (ref "D103") (pin "2") (pinfunction "K_2") (pintype "passive"))
      (node (ref "D104") (pin "2") (pinfunction "K_2") (pintype "passive"))
      (node (ref "D97") (pin "2") (pinfunction "K_2") (pintype "passive"))
      (node (ref "D98") (pin "2") (pinfunction "K_2") (pintype "passive"))
      (node (ref "D99") (pin "2") (pinfunction "K_2") (pintype "passive"))
      (node (ref "LED12") (pin "2") (pinfunction "K_2") (pintype "passive"))
      (node (ref "U2") (pin "14") (pinfunction "12_14") (pintype "output"))
    )
    (net (code "35") (name "/COM13") (class "Default")
      (node (ref "D105") (pin "2") (pinfunction "K_2") (pintype "passive"))
      (node (ref "D106") (pin "2") (pinfunction "K_2") (pintype "passive"))
      (node (ref "D107") (pin "2") (pinfunction "K_2") (pintype "passive"))
      (node (ref "D108") (pin "2") (pinfunction "K_2") (pintype "passive"))
      (node (ref "D109") (pin "2") (pinfunction "K_2") (pintype "passive"))
      (node (ref "D110") (pin "2") (pinfunction "K_2") (pintype "passive"))
      (node (ref "D111") (pin "2") (pinfunction "K_2") (pintype "passive"))
      (node (ref "D112") (pin "2") (pinfunction "K_2") (pintype "passive"))
      (node (ref "LED13") (pin "2") (pinfunction "K_2") (pintype "passive"))
      (node (ref "U2") (pin "15") (pinfunction "13_15") (pintype "output"))
    )
    (net (code "36") (name "/COM14") (class "Default")
      (node (ref "D113") (pin "2") (pinfunction "K_2") (pintype "passive"))
      (node (ref "D114") (pin "2") (pinfunction "K_2") (pintype "passive"))
      (node (ref "D115") (pin "2") (pinfunction "K_2") (pintype "passive"))
      (node (ref "D116") (pin "2") (pinfunction "K_2") (pintype "passive"))
      (node (ref "D117") (pin "2") (pinfunction "K_2") (pintype "passive"))
      (node (ref "D118") (pin "2") (pinfunction "K_2") (pintype "passive"))
      (node (ref "D119") (pin "2") (pinfunction "K_2") (pintype "passive"))
      (node (ref "D120") (pin "2") (pinfunction "K_2") (pintype "passive"))
      (node (ref "LED14") (pin "2") (pinfunction "K_2") (pintype "passive"))
      (node (ref "U2") (pin "16") (pinfunction "14_16") (pintype "output"))
    )
    (net (code "37") (name "/COM15") (class "Default")
      (node (ref "D121") (pin "2") (pinfunction "K_2") (pintype "passive"))
      (node (ref "D122") (pin "2") (pinfunction "K_2") (pintype "passive"))
      (node (ref "D123") (pin "2") (pinfunction "K_2") (pintype "passive"))
      (node (ref "D124") (pin "2") (pinfunction "K_2") (pintype "passive"))
      (node (ref "D125") (pin "2") (pinfunction "K_2") (pintype "passive"))
      (node (ref "D126") (pin "2") (pinfunction "K_2") (pintype "passive"))
      (node (ref "D127") (pin "2") (pinfunction "K_2") (pintype "passive"))
      (node (ref "D128") (pin "2") (pinfunction "K_2") (pintype "passive"))
      (node (ref "LED15") (pin "2") (pinfunction "K_2") (pintype "passive"))
      (node (ref "U2") (pin "17") (pinfunction "15_17") (pintype "output"))
    )
    (net (code "38") (name "/Data0") (class "Default")
      (node (ref "LED38") (pin "1") (pinfunction "A_1") (pintype "passive"))
      (node (ref "R25") (pin "2") (pinfunction "2_2") (pintype "passive"))
      (node (ref "U1") (pin "18") (pinfunction "Y1_18") (pintype "tri_state"))
      (node (ref "U8") (pin "6") (pinfunction "B1_6") (pintype "input"))
    )
    (net (code "39") (name "/Data1") (class "Default")
      (node (ref "LED45") (pin "1") (pinfunction "A_1") (pintype "passive"))
      (node (ref "R26") (pin "2") (pinfunction "2_2") (pintype "passive"))
      (node (ref "U1") (pin "17") (pinfunction "Y2_17") (pintype "tri_state"))
      (node (ref "U8") (pin "2") (pinfunction "B2_2") (pintype "input"))
    )
    (net (code "40") (name "/Data2") (class "Default")
      (node (ref "LED52") (pin "1") (pinfunction "A_1") (pintype "passive"))
      (node (ref "R28") (pin "2") (pinfunction "2_2") (pintype "passive"))
      (node (ref "U1") (pin "16") (pinfunction "Y3_16") (pintype "tri_state"))
      (node (ref "U8") (pin "15") (pinfunction "B3_15") (pintype "input"))
    )
    (net (code "41") (name "/Data3") (class "Default")
      (node (ref "LED59") (pin "1") (pinfunction "A_1") (pintype "passive"))
      (node (ref "R31") (pin "2") (pinfunction "2_2") (pintype "passive"))
      (node (ref "U1") (pin "15") (pinfunction "Y4_15") (pintype "tri_state"))
      (node (ref "U8") (pin "11") (pinfunction "B4_11") (pintype "input"))
    )
    (net (code "42") (name "/Data4") (class "Default")
      (node (ref "R34") (pin "2") (pinfunction "2_2") (pintype "passive"))
      (node (ref "U1") (pin "14") (pinfunction "Y5_14") (pintype "tri_state"))
      (node (ref "U3") (pin "10") (pintype "input"))
      (node (ref "U3") (pin "12") (pintype "input"))
    )
    (net (code "43") (name "/Data5") (class "Default")
      (node (ref "LED34") (pin "1") (pinfunction "A_1") (pintype "passive"))
      (node (ref "R37") (pin "2") (pinfunction "2_2") (pintype "passive"))
      (node (ref "U1") (pin "13") (pinfunction "Y6_13") (pintype "tri_state"))
      (node (ref "U11") (pin "2") (pinfunction "B_2") (pintype "input"))
      (node (ref "U7") (pin "2") (pinfunction "B_2") (pintype "input"))
    )
    (net (code "44") (name "/Data6") (class "Default")
      (node (ref "R39") (pin "2") (pinfunction "2_2") (pintype "passive"))
      (node (ref "U1") (pin "12") (pinfunction "Y7_12") (pintype "tri_state"))
      (node (ref "U3") (pin "1") (pintype "input"))
      (node (ref "U4") (pin "11") (pintype "input"))
      (node (ref "U4") (pin "13") (pintype "input"))
    )
    (net (code "45") (name "/Data7") (class "Default")
      (node (ref "R40") (pin "2") (pinfunction "2_2") (pintype "passive"))
      (node (ref "U1") (pin "11") (pinfunction "Y8_11") (pintype "tri_state"))
      (node (ref "U3") (pin "13") (pintype "input"))
      (node (ref "U3") (pin "2") (pintype "input"))
      (node (ref "U3") (pin "5") (pintype "input"))
      (node (ref "U4") (pin "10") (pintype "input"))
      (node (ref "U4") (pin "5") (pintype "input"))
    )
    (net (code "46") (name "/IN_0") (class "Default")
      (node (ref "LED44") (pin "1") (pinfunction "A_1") (pintype "passive"))
      (node (ref "R88") (pin "1") (pinfunction "1_1") (pintype "passive"))
      (node (ref "SW18") (pin "5") (pinfunction "5_5") (pintype "passive"))
      (node (ref "U7") (pin "4") (pinfunction "1C2_4") (pintype "input"))
    )
    (net (code "47") (name "/IN_1") (class "Default")
      (node (ref "LED51") (pin "1") (pinfunction "A_1") (pintype "passive"))
      (node (ref "R87") (pin "1") (pinfunction "1_1") (pintype "passive"))
      (node (ref "SW18") (pin "6") (pinfunction "6_6") (pintype "passive"))
      (node (ref "U7") (pin "12") (pinfunction "2C2_12") (pintype "input"))
    )
    (net (code "48") (name "/IN_2") (class "Default")
      (node (ref "LED58") (pin "1") (pinfunction "A_1") (pintype "passive"))
      (node (ref "R86") (pin "1") (pinfunction "1_1") (pintype "passive"))
      (node (ref "SW18") (pin "7") (pinfunction "7_7") (pintype "passive"))
      (node (ref "U11") (pin "4") (pinfunction "1C2_4") (pintype "input"))
    )
    (net (code "49") (name "/IN_3") (class "Default")
      (node (ref "LED65") (pin "1") (pinfunction "A_1") (pintype "passive"))
      (node (ref "R85") (pin "1") (pinfunction "1_1") (pintype "passive"))
      (node (ref "SW18") (pin "8") (pinfunction "8_8") (pintype "passive"))
      (node (ref "U11") (pin "12") (pinfunction "2C2_12") (pintype "input"))
    )
    (net (code "50") (name "/OUT_REG_0") (class "Default")
      (node (ref "LED43") (pin "1") (pinfunction "A_1") (pintype "passive"))
      (node (ref "R89") (pin "2") (pinfunction "2_2") (pintype "passive"))
      (node (ref "U12") (pin "14") (pinfunction "QA_14") (pintype "output"))
    )
    (net (code "51") (name "/OUT_REG_1") (class "Default")
      (node (ref "LED50") (pin "1") (pinfunction "A_1") (pintype "passive"))
      (node (ref "R91") (pin "2") (pinfunction "2_2") (pintype "passive"))
      (node (ref "U12") (pin "13") (pinfunction "QB_13") (pintype "output"))
    )
    (net (code "52") (name "/OUT_REG_2") (class "Default")
      (node (ref "LED57") (pin "1") (pinfunction "A_1") (pintype "passive"))
      (node (ref "R93") (pin "2") (pinfunction "2_2") (pintype "passive"))
      (node (ref "U12") (pin "12") (pinfunction "QC_12") (pintype "output"))
    )
    (net (code "53") (name "/OUT_REG_3") (class "Default")
      (node (ref "LED64") (pin "1") (pinfunction "A_1") (pintype "passive"))
      (node (ref "R95") (pin "2") (pinfunction "2_2") (pintype "passive"))
      (node (ref "U12") (pin "11") (pinfunction "QD_11") (pintype "output"))
    )
    (net (code "54") (name "/SELA") (class "Default")
      (node (ref "LED33") (pin "1") (pinfunction "A_1") (pintype "passive"))
      (node (ref "U11") (pin "14") (pinfunction "A_14") (pintype "input"))
      (node (ref "U3") (pin "11") (pintype "output"))
      (node (ref "U7") (pin "14") (pinfunction "A_14") (pintype "input"))
    )
    (net (code "55") (name "/SYS_CLK") (class "Default")
      (node (ref "LED35") (pin "1") (pinfunction "A_1") (pintype "passive"))
      (node (ref "S1") (pin "2") (pinfunction "2_2") (pintype "passive"))
      (node (ref "U10") (pin "2") (pinfunction "CLK_2") (pintype "input"))
      (node (ref "U12") (pin "2") (pinfunction "CLK_2") (pintype "input"))
      (node (ref "U13") (pin "2") (pinfunction "CLK_2") (pintype "input"))
      (node (ref "U6") (pin "2") (pinfunction "CLK_2") (pintype "input"))
      (node (ref "U9") (pin "11") (pinfunction "CLK_11") (pintype "input"))
    )
    (net (code "56") (name "/SYS_RST") (class "Default")
      (node (ref "LED36") (pin "2") (pinfunction "K_2") (pintype "passive"))
      (node (ref "U10") (pin "1") (pinfunction "~{CLR}_1") (pintype "input"))
      (node (ref "U12") (pin "1") (pinfunction "~{CLR}_1") (pintype "input"))
      (node (ref "U13") (pin "1") (pinfunction "~{CLR}_1") (pintype "input"))
      (node (ref "U5") (pin "12") (pintype "output"))
      (node (ref "U6") (pin "1") (pinfunction "~{CLR}_1") (pintype "input"))
      (node (ref "U9") (pin "13") (pinfunction "~{CLR}_13") (pintype "input"))
    )
    (net (code "57") (name "/~{C}") (class "Default")
      (node (ref "LED32") (pin "2") (pinfunction "K_2") (pintype "passive"))
      (node (ref "U3") (pin "9") (pintype "input"))
      (node (ref "U9") (pin "8") (pinfunction "~{Q}_8") (pintype "output"))
    )
    (net (code "58") (name "/~{Load0}") (class "Default")
      (node (ref "LED18") (pin "2") (pinfunction "K_2") (pintype "passive"))
      (node (ref "LED75") (pin "2") (pinfunction "K_2") (pintype "passive"))
      (node (ref "U3") (pin "3") (pintype "output"))
      (node (ref "U6") (pin "9") (pinfunction "~{LOAD}_9") (pintype "input"))
    )
    (net (code "59") (name "/~{Load1}") (class "Default")
      (node (ref "LED20") (pin "2") (pinfunction "K_2") (pintype "passive"))
      (node (ref "LED76") (pin "2") (pinfunction "K_2") (pintype "passive"))
      (node (ref "U10") (pin "9") (pinfunction "~{LOAD}_9") (pintype "input"))
      (node (ref "U3") (pin "6") (pintype "output"))
    )
    (net (code "60") (name "/~{Load2}") (class "Default")
      (node (ref "LED23") (pin "2") (pinfunction "K_2") (pintype "passive"))
      (node (ref "LED77") (pin "2") (pinfunction "K_2") (pintype "passive"))
      (node (ref "U12") (pin "9") (pinfunction "~{LOAD}_9") (pintype "input"))
      (node (ref "U4") (pin "6") (pintype "output"))
    )
    (net (code "61") (name "/~{Load3}") (class "Default")
      (node (ref "LED26") (pin "2") (pinfunction "K_2") (pintype "passive"))
      (node (ref "LED78") (pin "2") (pinfunction "K_2") (pintype "passive"))
      (node (ref "U13") (pin "9") (pinfunction "~{LOAD}_9") (pintype "input"))
      (node (ref "U4") (pin "8") (pintype "output"))
    )
    (net (code "62") (name "GND") (class "Default")
      (node (ref "C1") (pin "1") (pinfunction "1_1") (pintype "passive"))
      (node (ref "C10") (pin "1") (pinfunction "1_1") (pintype "passive"))
      (node (ref "C11") (pin "1") (pinfunction "1_1") (pintype "passive"))
      (node (ref "C12") (pin "1") (pinfunction "1_1") (pintype "passive"))
      (node (ref "C13") (pin "1") (pinfunction "1_1") (pintype "passive"))
      (node (ref "C14") (pin "1") (pinfunction "1_1") (pintype "passive"))
      (node (ref "C15") (pin "1") (pinfunction "1_1") (pintype "passive"))
      (node (ref "C16") (pin "1") (pinfunction "1_1") (pintype "passive"))
      (node (ref "C18") (pin "1") (pinfunction "1_1") (pintype "passive"))
      (node (ref "C2") (pin "1") (pinfunction "1_1") (pintype "passive"))
      (node (ref "C3") (pin "1") (pinfunction "1_1") (pintype "passive"))
      (node (ref "C4") (pin "1") (pinfunction "1_1") (pintype "passive"))
      (node (ref "C5") (pin "1") (pinfunction "1_1") (pintype "passive"))
      (node (ref "C6") (pin "1") (pinfunction "1_1") (pintype "passive"))
      (node (ref "C7") (pin "1") (pinfunction "1_1") (pintype "passive"))
      (node (ref "C8") (pin "1") (pinfunction "1_1") (pintype "passive"))
      (node (ref "C9") (pin "1") (pinfunction "1_1") (pintype "passive"))
      (node (ref "LED16") (pin "2") (pinfunction "K_2") (pintype "passive"))
      (node (ref "LED17") (pin "2") (pinfunction "K_2") (pintype "passive"))
      (node (ref "LED19") (pin "2") (pinfunction "K_2") (pintype "passive"))
      (node (ref "LED21") (pin "2") (pinfunction "K_2") (pintype "passive"))
      (node (ref "LED22") (pin "2") (pinfunction "K_2") (pintype "passive"))
      (node (ref "LED24") (pin "2") (pinfunction "K_2") (pintype "passive"))
      (node (ref "LED25") (pin "2") (pinfunction "K_2") (pintype "passive"))
      (node (ref "LED27") (pin "2") (pinfunction "K_2") (pintype "passive"))
      (node (ref "LED28") (pin "2") (pinfunction "K_2") (pintype "passive"))
      (node (ref "LED29") (pin "2") (pinfunction "K_2") (pintype "passive"))
      (node (ref "LED30") (pin "2") (pinfunction "K_2") (pintype "passive"))
      (node (ref "LED31") (pin "2") (pinfunction "K_2") (pintype "passive"))
      (node (ref "LED41") (pin "2") (pinfunction "K_2") (pintype "passive"))
      (node (ref "LED42") (pin "2") (pinfunction "K_2") (pintype "passive"))
      (node (ref "LED48") (pin "2") (pinfunction "K_2") (pintype "passive"))
      (node (ref "LED49") (pin "2") (pinfunction "K_2") (pintype "passive"))
      (node (ref "LED55") (pin "2") (pinfunction "K_2") (pintype "passive"))
      (node (ref "LED56") (pin "2") (pinfunction "K_2") (pintype "passive"))
      (node (ref "LED62") (pin "2") (pinfunction "K_2") (pintype "passive"))
      (node (ref "LED63") (pin "2") (pinfunction "K_2") (pintype "passive"))
      (node (ref "LED66") (pin "2") (pinfunction "K_2") (pintype "passive"))
      (node (ref "LED67") (pin "2") (pinfunction "K_2") (pintype "passive"))
      (node (ref "LED68") (pin "2") (pinfunction "K_2") (pintype "passive"))
      (node (ref "LED69") (pin "2") (pinfunction "K_2") (pintype "passive"))
      (node (ref "LED70") (pin "2") (pinfunction "K_2") (pintype "passive"))
      (node (ref "LED71") (pin "2") (pinfunction "K_2") (pintype "passive"))
      (node (ref "LED72") (pin "2") (pinfunction "K_2") (pintype "passive"))
      (node (ref "LED73") (pin "2") (pinfunction "K_2") (pintype "passive"))
      (node (ref "R42") (pin "1") (pinfunction "1_1") (pintype "passive"))
      (node (ref "R43") (pin "1") (pinfunction "1_1") (pintype "passive"))
      (node (ref "R44") (pin "1") (pinfunction "1_1") (pintype "passive"))
      (node (ref "R46") (pin "1") (pinfunction "1_1") (pintype "passive"))
      (node (ref "R47") (pin "1") (pinfunction "1_1") (pintype "passive"))
      (node (ref "R48") (pin "1") (pinfunction "1_1") (pintype "passive"))
      (node (ref "R49") (pin "1") (pinfunction "1_1") (pintype "passive"))
      (node (ref "R52") (pin "1") (pinfunction "1_1") (pintype "passive"))
      (node (ref "R53") (pin "1") (pinfunction "1_1") (pintype "passive"))
      (node (ref "R54") (pin "1") (pinfunction "1_1") (pintype "passive"))
      (node (ref "R55") (pin "1") (pinfunction "1_1") (pintype "passive"))
      (node (ref "R56") (pin "1") (pinfunction "1_1") (pintype "passive"))
      (node (ref "R59") (pin "1") (pinfunction "1_1") (pintype "passive"))
      (node (ref "R60") (pin "1") (pinfunction "1_1") (pintype "passive"))
      (node (ref "R61") (pin "1") (pinfunction "1_1") (pintype "passive"))
      (node (ref "R62") (pin "1") (pinfunction "1_1") (pintype "passive"))
      (node (ref "R63") (pin "1") (pinfunction "1_1") (pintype "passive"))
      (node (ref "R66") (pin "1") (pinfunction "1_1") (pintype "passive"))
      (node (ref "R67") (pin "1") (pinfunction "1_1") (pintype "passive"))
      (node (ref "R68") (pin "1") (pinfunction "1_1") (pintype "passive"))
      (node (ref "R69") (pin "1") (pinfunction "1_1") (pintype "passive"))
      (node (ref "R70") (pin "1") (pinfunction "1_1") (pintype "passive"))
      (node (ref "R73") (pin "1") (pinfunction "1_1") (pintype "passive"))
      (node (ref "R74") (pin "1") (pinfunction "1_1") (pintype "passive"))
      (node (ref "R85") (pin "2") (pinfunction "2_2") (pintype "passive"))
      (node (ref "R86") (pin "2") (pinfunction "2_2") (pintype "passive"))
      (node (ref "R87") (pin "2") (pinfunction "2_2") (pintype "passive"))
      (node (ref "R88") (pin "2") (pinfunction "2_2") (pintype "passive"))
      (node (ref "R97") (pin "1") (pinfunction "1_1") (pintype "passive"))
      (node (ref "SW16") (pin "2") (pinfunction "K_2") (pintype "passive"))
      (node (ref "SW17") (pin "2") (pinfunction "K_2") (pintype "passive"))
      (node (ref "U1") (pin "1") (pinfunction "~{G}1_1") (pintype "input"))
      (node (ref "U1") (pin "10") (pinfunction "GND_10") (pintype "power_in"))
      (node (ref "U1") (pin "19") (pinfunction "~{G}2_19") (pintype "input"))
      (node (ref "U10") (pin "10") (pinfunction "ENT_10") (pintype "input"))
      (node (ref "U10") (pin "7") (pinfunction "ENP_7") (pintype "input"))
      (node (ref "U10") (pin "8") (pinfunction "GND_8") (pintype "power_in"))
      (node (ref "U11") (pin "1") (pinfunction "1~{G}_1") (pintype "input"))
      (node (ref "U11") (pin "13") (pinfunction "2C3_13") (pintype "input"))
      (node (ref "U11") (pin "15") (pinfunction "2~{G}_15") (pintype "input"))
      (node (ref "U11") (pin "3") (pinfunction "1C3_3") (pintype "input"))
      (node (ref "U11") (pin "8") (pinfunction "GND_8") (pintype "power_in"))
      (node (ref "U12") (pin "10") (pinfunction "ENT_10") (pintype "input"))
      (node (ref "U12") (pin "7") (pinfunction "ENP_7") (pintype "input"))
      (node (ref "U12") (pin "8") (pinfunction "GND_8") (pintype "power_in"))
      (node (ref "U13") (pin "8") (pinfunction "GND_8") (pintype "power_in"))
      (node (ref "U2") (pin "12") (pinfunction "GND_12") (pintype "power_in"))
      (node (ref "U2") (pin "18") (pinfunction "~{G}1_18") (pintype "input"))
      (node (ref "U2") (pin "19") (pinfunction "~{G}2_19") (pintype "input"))
      (node (ref "U3") (pin "7") (pinfunction "GND_7") (pintype "power_in"))
      (node (ref "U4") (pin "7") (pinfunction "GND_7") (pintype "power_in"))
      (node (ref "U5") (pin "1") (pintype "input"))
      (node (ref "U5") (pin "7") (pinfunction "GND_7") (pintype "power_in"))
      (node (ref "U6") (pin "10") (pinfunction "ENT_10") (pintype "input"))
      (node (ref "U6") (pin "7") (pinfunction "ENP_7") (pintype "input"))
      (node (ref "U6") (pin "8") (pinfunction "GND_8") (pintype "power_in"))
      (node (ref "U7") (pin "1") (pinfunction "1~{G}_1") (pintype "input"))
      (node (ref "U7") (pin "13") (pinfunction "2C3_13") (pintype "input"))
      (node (ref "U7") (pin "15") (pinfunction "2~{G}_15") (pintype "input"))
      (node (ref "U7") (pin "3") (pinfunction "1C3_3") (pintype "input"))
      (node (ref "U7") (pin "8") (pinfunction "GND_8") (pintype "power_in"))
      (node (ref "U8") (pin "7") (pinfunction "CO_7") (pintype "input"))
      (node (ref "U8") (pin "8") (pinfunction "GND_8") (pintype "power_in"))
      (node (ref "U9") (pin "2") (pinfunction "D_2") (pintype "input"))
      (node (ref "U9") (pin "3") (pinfunction "CLK_3") (pintype "input"))
      (node (ref "U9") (pin "7") (pinfunction "GND_7") (pintype "power_in"))
      (node (ref "USB1") (pin "0") (pinfunction "GND_0") (pintype "passive"))
      (node (ref "USB1") (pin "A12") (pinfunction "GND_A12") (pintype "passive"))
      (node (ref "USB1") (pin "B12") (pinfunction "GND_B12") (pintype "passive"))
    )
    (net (code "63") (name "Net-(C16-Pad2)") (class "Default")
      (node (ref "C16") (pin "2") (pinfunction "2_2") (pintype "passive"))
      (node (ref "R76") (pin "2") (pinfunction "2_2") (pintype "passive"))
      (node (ref "R77") (pin "1") (pinfunction "1_1") (pintype "passive"))
    )
    (net (code "64") (name "Net-(C17-Pad1)") (class "Default")
      (node (ref "C17") (pin "1") (pinfunction "1_1") (pintype "passive"))
      (node (ref "R81") (pin "1") (pinfunction "1_1") (pintype "passive"))
      (node (ref "U5") (pin "8") (pintype "output"))
    )
    (net (code "65") (name "Net-(C17-Pad2)") (class "Default")
      (node (ref "C17") (pin "2") (pinfunction "2_2") (pintype "passive"))
      (node (ref "R80") (pin "1") (pinfunction "1_1") (pintype "passive"))
      (node (ref "RP1") (pin "2") (pinfunction "2_2") (pintype "passive"))
    )
    (net (code "66") (name "Net-(C18-Pad2)") (class "Default")
      (node (ref "C18") (pin "2") (pinfunction "2_2") (pintype "passive"))
      (node (ref "R83") (pin "2") (pinfunction "2_2") (pintype "passive"))
      (node (ref "R84") (pin "1") (pinfunction "1_1") (pintype "passive"))
    )
    (net (code "67") (name "Net-(D1-A)") (class "Default")
      (node (ref "D1") (pin "1") (pinfunction "A_1") (pintype "passive"))
      (node (ref "SW0") (pin "1") (pinfunction "1_1") (pintype "passive"))
    )
    (net (code "68") (name "Net-(D2-A)") (class "Default")
      (node (ref "D2") (pin "1") (pinfunction "A_1") (pintype "passive"))
      (node (ref "SW0") (pin "2") (pinfunction "2_2") (pintype "passive"))
    )
    (net (code "69") (name "Net-(D3-A)") (class "Default")
      (node (ref "D3") (pin "1") (pinfunction "A_1") (pintype "passive"))
      (node (ref "SW0") (pin "3") (pinfunction "3_3") (pintype "passive"))
    )
    (net (code "70") (name "Net-(D4-A)") (class "Default")
      (node (ref "D4") (pin "1") (pinfunction "A_1") (pintype "passive"))
      (node (ref "SW0") (pin "4") (pinfunction "4_4") (pintype "passive"))
    )
    (net (code "71") (name "Net-(D5-A)") (class "Default")
      (node (ref "D5") (pin "1") (pinfunction "A_1") (pintype "passive"))
      (node (ref "SW0") (pin "5") (pinfunction "5_5") (pintype "passive"))
    )
    (net (code "72") (name "Net-(D6-A)") (class "Default")
      (node (ref "D6") (pin "1") (pinfunction "A_1") (pintype "passive"))
      (node (ref "SW0") (pin "6") (pinfunction "6_6") (pintype "passive"))
    )
    (net (code "73") (name "Net-(D7-A)") (class "Default")
      (node (ref "D7") (pin "1") (pinfunction "A_1") (pintype "passive"))
      (node (ref "SW0") (pin "7") (pinfunction "7_7") (pintype "passive"))
    )
    (net (code "74") (name "Net-(D8-A)") (class "Default")
      (node (ref "D8") (pin "1") (pinfunction "A_1") (pintype "passive"))
      (node (ref "SW0") (pin "8") (pinfunction "8_8") (pintype "passive"))
    )
    (net (code "75") (name "Net-(D9-A)") (class "Default")
      (node (ref "D9") (pin "1") (pinfunction "A_1") (pintype "passive"))
      (node (ref "SW1") (pin "1") (pinfunction "1_1") (pintype "passive"))
    )
    (net (code "76") (name "Net-(D10-A)") (class "Default")
      (node (ref "D10") (pin "1") (pinfunction "A_1") (pintype "passive"))
      (node (ref "SW1") (pin "2") (pinfunction "2_2") (pintype "passive"))
    )
    (net (code "77") (name "Net-(D11-A)") (class "Default")
      (node (ref "D11") (pin "1") (pinfunction "A_1") (pintype "passive"))
      (node (ref "SW1") (pin "3") (pinfunction "3_3") (pintype "passive"))
    )
    (net (code "78") (name "Net-(D12-A)") (class "Default")
      (node (ref "D12") (pin "1") (pinfunction "A_1") (pintype "passive"))
      (node (ref "SW1") (pin "4") (pinfunction "4_4") (pintype "passive"))
    )
    (net (code "79") (name "Net-(D13-A)") (class "Default")
      (node (ref "D13") (pin "1") (pinfunction "A_1") (pintype "passive"))
      (node (ref "SW1") (pin "5") (pinfunction "5_5") (pintype "passive"))
    )
    (net (code "80") (name "Net-(D14-A)") (class "Default")
      (node (ref "D14") (pin "1") (pinfunction "A_1") (pintype "passive"))
      (node (ref "SW1") (pin "6") (pinfunction "6_6") (pintype "passive"))
    )
    (net (code "81") (name "Net-(D15-A)") (class "Default")
      (node (ref "D15") (pin "1") (pinfunction "A_1") (pintype "passive"))
      (node (ref "SW1") (pin "7") (pinfunction "7_7") (pintype "passive"))
    )
    (net (code "82") (name "Net-(D16-A)") (class "Default")
      (node (ref "D16") (pin "1") (pinfunction "A_1") (pintype "passive"))
      (node (ref "SW1") (pin "8") (pinfunction "8_8") (pintype "passive"))
    )
    (net (code "83") (name "Net-(D17-A)") (class "Default")
      (node (ref "D17") (pin "1") (pinfunction "A_1") (pintype "passive"))
      (node (ref "SW2") (pin "1") (pinfunction "1_1") (pintype "passive"))
    )
    (net (code "84") (name "Net-(D18-A)") (class "Default")
      (node (ref "D18") (pin "1") (pinfunction "A_1") (pintype "passive"))
      (node (ref "SW2") (pin "2") (pinfunction "2_2") (pintype "passive"))
    )
    (net (code "85") (name "Net-(D19-A)") (class "Default")
      (node (ref "D19") (pin "1") (pinfunction "A_1") (pintype "passive"))
      (node (ref "SW2") (pin "3") (pinfunction "3_3") (pintype "passive"))
    )
    (net (code "86") (name "Net-(D20-A)") (class "Default")
      (node (ref "D20") (pin "1") (pinfunction "A_1") (pintype "passive"))
      (node (ref "SW2") (pin "4") (pinfunction "4_4") (pintype "passive"))
    )
    (net (code "87") (name "Net-(D21-A)") (class "Default")
      (node (ref "D21") (pin "1") (pinfunction "A_1") (pintype "passive"))
      (node (ref "SW2") (pin "5") (pinfunction "5_5") (pintype "passive"))
    )
    (net (code "88") (name "Net-(D22-A)") (class "Default")
      (node (ref "D22") (pin "1") (pinfunction "A_1") (pintype "passive"))
      (node (ref "SW2") (pin "6") (pinfunction "6_6") (pintype "passive"))
    )
    (net (code "89") (name "Net-(D23-A)") (class "Default")
      (node (ref "D23") (pin "1") (pinfunction "A_1") (pintype "passive"))
      (node (ref "SW2") (pin "7") (pinfunction "7_7") (pintype "passive"))
    )
    (net (code "90") (name "Net-(D24-A)") (class "Default")
      (node (ref "D24") (pin "1") (pinfunction "A_1") (pintype "passive"))
      (node (ref "SW2") (pin "8") (pinfunction "8_8") (pintype "passive"))
    )
    (net (code "91") (name "Net-(D25-A)") (class "Default")
      (node (ref "D25") (pin "1") (pinfunction "A_1") (pintype "passive"))
      (node (ref "SW3") (pin "1") (pinfunction "1_1") (pintype "passive"))
    )
    (net (code "92") (name "Net-(D26-A)") (class "Default")
      (node (ref "D26") (pin "1") (pinfunction "A_1") (pintype "passive"))
      (node (ref "SW3") (pin "2") (pinfunction "2_2") (pintype "passive"))
    )
    (net (code "93") (name "Net-(D27-A)") (class "Default")
      (node (ref "D27") (pin "1") (pinfunction "A_1") (pintype "passive"))
      (node (ref "SW3") (pin "3") (pinfunction "3_3") (pintype "passive"))
    )
    (net (code "94") (name "Net-(D28-A)") (class "Default")
      (node (ref "D28") (pin "1") (pinfunction "A_1") (pintype "passive"))
      (node (ref "SW3") (pin "4") (pinfunction "4_4") (pintype "passive"))
    )
    (net (code "95") (name "Net-(D29-A)") (class "Default")
      (node (ref "D29") (pin "1") (pinfunction "A_1") (pintype "passive"))
      (node (ref "SW3") (pin "5") (pinfunction "5_5") (pintype "passive"))
    )
    (net (code "96") (name "Net-(D30-A)") (class "Default")
      (node (ref "D30") (pin "1") (pinfunction "A_1") (pintype "passive"))
      (node (ref "SW3") (pin "6") (pinfunction "6_6") (pintype "passive"))
    )
    (net (code "97") (name "Net-(D31-A)") (class "Default")
      (node (ref "D31") (pin "1") (pinfunction "A_1") (pintype "passive"))
      (node (ref "SW3") (pin "7") (pinfunction "7_7") (pintype "passive"))
    )
    (net (code "98") (name "Net-(D32-A)") (class "Default")
      (node (ref "D32") (pin "1") (pinfunction "A_1") (pintype "passive"))
      (node (ref "SW3") (pin "8") (pinfunction "8_8") (pintype "passive"))
    )
    (net (code "99") (name "Net-(D33-A)") (class "Default")
      (node (ref "D33") (pin "1") (pinfunction "A_1") (pintype "passive"))
      (node (ref "SW4") (pin "1") (pinfunction "1_1") (pintype "passive"))
    )
    (net (code "100") (name "Net-(D34-A)") (class "Default")
      (node (ref "D34") (pin "1") (pinfunction "A_1") (pintype "passive"))
      (node (ref "SW4") (pin "2") (pinfunction "2_2") (pintype "passive"))
    )
    (net (code "101") (name "Net-(D35-A)") (class "Default")
      (node (ref "D35") (pin "1") (pinfunction "A_1") (pintype "passive"))
      (node (ref "SW4") (pin "3") (pinfunction "3_3") (pintype "passive"))
    )
    (net (code "102") (name "Net-(D36-A)") (class "Default")
      (node (ref "D36") (pin "1") (pinfunction "A_1") (pintype "passive"))
      (node (ref "SW4") (pin "4") (pinfunction "4_4") (pintype "passive"))
    )
    (net (code "103") (name "Net-(D37-A)") (class "Default")
      (node (ref "D37") (pin "1") (pinfunction "A_1") (pintype "passive"))
      (node (ref "SW4") (pin "5") (pinfunction "5_5") (pintype "passive"))
    )
    (net (code "104") (name "Net-(D38-A)") (class "Default")
      (node (ref "D38") (pin "1") (pinfunction "A_1") (pintype "passive"))
      (node (ref "SW4") (pin "6") (pinfunction "6_6") (pintype "passive"))
    )
    (net (code "105") (name "Net-(D39-A)") (class "Default")
      (node (ref "D39") (pin "1") (pinfunction "A_1") (pintype "passive"))
      (node (ref "SW4") (pin "7") (pinfunction "7_7") (pintype "passive"))
    )
    (net (code "106") (name "Net-(D40-A)") (class "Default")
      (node (ref "D40") (pin "1") (pinfunction "A_1") (pintype "passive"))
      (node (ref "SW4") (pin "8") (pinfunction "8_8") (pintype "passive"))
    )
    (net (code "107") (name "Net-(D41-A)") (class "Default")
      (node (ref "D41") (pin "1") (pinfunction "A_1") (pintype "passive"))
      (node (ref "SW5") (pin "1") (pinfunction "1_1") (pintype "passive"))
    )
    (net (code "108") (name "Net-(D42-A)") (class "Default")
      (node (ref "D42") (pin "1") (pinfunction "A_1") (pintype "passive"))
      (node (ref "SW5") (pin "2") (pinfunction "2_2") (pintype "passive"))
    )
    (net (code "109") (name "Net-(D43-A)") (class "Default")
      (node (ref "D43") (pin "1") (pinfunction "A_1") (pintype "passive"))
      (node (ref "SW5") (pin "3") (pinfunction "3_3") (pintype "passive"))
    )
    (net (code "110") (name "Net-(D44-A)") (class "Default")
      (node (ref "D44") (pin "1") (pinfunction "A_1") (pintype "passive"))
      (node (ref "SW5") (pin "4") (pinfunction "4_4") (pintype "passive"))
    )
    (net (code "111") (name "Net-(D45-A)") (class "Default")
      (node (ref "D45") (pin "1") (pinfunction "A_1") (pintype "passive"))
      (node (ref "SW5") (pin "5") (pinfunction "5_5") (pintype "passive"))
    )
    (net (code "112") (name "Net-(D46-A)") (class "Default")
      (node (ref "D46") (pin "1") (pinfunction "A_1") (pintype "passive"))
      (node (ref "SW5") (pin "6") (pinfunction "6_6") (pintype "passive"))
    )
    (net (code "113") (name "Net-(D47-A)") (class "Default")
      (node (ref "D47") (pin "1") (pinfunction "A_1") (pintype "passive"))
      (node (ref "SW5") (pin "7") (pinfunction "7_7") (pintype "passive"))
    )
    (net (code "114") (name "Net-(D48-A)") (class "Default")
      (node (ref "D48") (pin "1") (pinfunction "A_1") (pintype "passive"))
      (node (ref "SW5") (pin "8") (pinfunction "8_8") (pintype "passive"))
    )
    (net (code "115") (name "Net-(D49-A)") (class "Default")
      (node (ref "D49") (pin "1") (pinfunction "A_1") (pintype "passive"))
      (node (ref "SW6") (pin "1") (pinfunction "1_1") (pintype "passive"))
    )
    (net (code "116") (name "Net-(D50-A)") (class "Default")
      (node (ref "D50") (pin "1") (pinfunction "A_1") (pintype "passive"))
      (node (ref "SW6") (pin "2") (pinfunction "2_2") (pintype "passive"))
    )
    (net (code "117") (name "Net-(D51-A)") (class "Default")
      (node (ref "D51") (pin "1") (pinfunction "A_1") (pintype "passive"))
      (node (ref "SW6") (pin "3") (pinfunction "3_3") (pintype "passive"))
    )
    (net (code "118") (name "Net-(D52-A)") (class "Default")
      (node (ref "D52") (pin "1") (pinfunction "A_1") (pintype "passive"))
      (node (ref "SW6") (pin "4") (pinfunction "4_4") (pintype "passive"))
    )
    (net (code "119") (name "Net-(D53-A)") (class "Default")
      (node (ref "D53") (pin "1") (pinfunction "A_1") (pintype "passive"))
      (node (ref "SW6") (pin "5") (pinfunction "5_5") (pintype "passive"))
    )
    (net (code "120") (name "Net-(D54-A)") (class "Default")
      (node (ref "D54") (pin "1") (pinfunction "A_1") (pintype "passive"))
      (node (ref "SW6") (pin "6") (pinfunction "6_6") (pintype "passive"))
    )
    (net (code "121") (name "Net-(D55-A)") (class "Default")
      (node (ref "D55") (pin "1") (pinfunction "A_1") (pintype "passive"))
      (node (ref "SW6") (pin "7") (pinfunction "7_7") (pintype "passive"))
    )
    (net (code "122") (name "Net-(D56-A)") (class "Default")
      (node (ref "D56") (pin "1") (pinfunction "A_1") (pintype "passive"))
      (node (ref "SW6") (pin "8") (pinfunction "8_8") (pintype "passive"))
    )
    (net (code "123") (name "Net-(D57-A)") (class "Default")
      (node (ref "D57") (pin "1") (pinfunction "A_1") (pintype "passive"))
      (node (ref "SW7") (pin "1") (pinfunction "1_1") (pintype "passive"))
    )
    (net (code "124") (name "Net-(D58-A)") (class "Default")
      (node (ref "D58") (pin "1") (pinfunction "A_1") (pintype "passive"))
      (node (ref "SW7") (pin "2") (pinfunction "2_2") (pintype "passive"))
    )
    (net (code "125") (name "Net-(D59-A)") (class "Default")
      (node (ref "D59") (pin "1") (pinfunction "A_1") (pintype "passive"))
      (node (ref "SW7") (pin "3") (pinfunction "3_3") (pintype "passive"))
    )
    (net (code "126") (name "Net-(D60-A)") (class "Default")
      (node (ref "D60") (pin "1") (pinfunction "A_1") (pintype "passive"))
      (node (ref "SW7") (pin "4") (pinfunction "4_4") (pintype "passive"))
    )
    (net (code "127") (name "Net-(D61-A)") (class "Default")
      (node (ref "D61") (pin "1") (pinfunction "A_1") (pintype "passive"))
      (node (ref "SW7") (pin "5") (pinfunction "5_5") (pintype "passive"))
    )
    (net (code "128") (name "Net-(D62-A)") (class "Default")
      (node (ref "D62") (pin "1") (pinfunction "A_1") (pintype "passive"))
      (node (ref "SW7") (pin "6") (pinfunction "6_6") (pintype "passive"))
    )
    (net (code "129") (name "Net-(D63-A)") (class "Default")
      (node (ref "D63") (pin "1") (pinfunction "A_1") (pintype "passive"))
      (node (ref "SW7") (pin "7") (pinfunction "7_7") (pintype "passive"))
    )
    (net (code "130") (name "Net-(D64-A)") (class "Default")
      (node (ref "D64") (pin "1") (pinfunction "A_1") (pintype "passive"))
      (node (ref "SW7") (pin "8") (pinfunction "8_8") (pintype "passive"))
    )
    (net (code "131") (name "Net-(D65-A)") (class "Default")
      (node (ref "D65") (pin "1") (pinfunction "A_1") (pintype "passive"))
      (node (ref "SW8") (pin "1") (pinfunction "1_1") (pintype "passive"))
    )
    (net (code "132") (name "Net-(D66-A)") (class "Default")
      (node (ref "D66") (pin "1") (pinfunction "A_1") (pintype "passive"))
      (node (ref "SW8") (pin "2") (pinfunction "2_2") (pintype "passive"))
    )
    (net (code "133") (name "Net-(D67-A)") (class "Default")
      (node (ref "D67") (pin "1") (pinfunction "A_1") (pintype "passive"))
      (node (ref "SW8") (pin "3") (pinfunction "3_3") (pintype "passive"))
    )
    (net (code "134") (name "Net-(D68-A)") (class "Default")
      (node (ref "D68") (pin "1") (pinfunction "A_1") (pintype "passive"))
      (node (ref "SW8") (pin "4") (pinfunction "4_4") (pintype "passive"))
    )
    (net (code "135") (name "Net-(D69-A)") (class "Default")
      (node (ref "D69") (pin "1") (pinfunction "A_1") (pintype "passive"))
      (node (ref "SW8") (pin "5") (pinfunction "5_5") (pintype "passive"))
    )
    (net (code "136") (name "Net-(D70-A)") (class "Default")
      (node (ref "D70") (pin "1") (pinfunction "A_1") (pintype "passive"))
      (node (ref "SW8") (pin "6") (pinfunction "6_6") (pintype "passive"))
    )
    (net (code "137") (name "Net-(D71-A)") (class "Default")
      (node (ref "D71") (pin "1") (pinfunction "A_1") (pintype "passive"))
      (node (ref "SW8") (pin "7") (pinfunction "7_7") (pintype "passive"))
    )
    (net (code "138") (name "Net-(D72-A)") (class "Default")
      (node (ref "D72") (pin "1") (pinfunction "A_1") (pintype "passive"))
      (node (ref "SW8") (pin "8") (pinfunction "8_8") (pintype "passive"))
    )
    (net (code "139") (name "Net-(D73-A)") (class "Default")
      (node (ref "D73") (pin "1") (pinfunction "A_1") (pintype "passive"))
      (node (ref "SW9") (pin "1") (pinfunction "1_1") (pintype "passive"))
    )
    (net (code "140") (name "Net-(D74-A)") (class "Default")
      (node (ref "D74") (pin "1") (pinfunction "A_1") (pintype "passive"))
      (node (ref "SW9") (pin "2") (pinfunction "2_2") (pintype "passive"))
    )
    (net (code "141") (name "Net-(D75-A)") (class "Default")
      (node (ref "D75") (pin "1") (pinfunction "A_1") (pintype "passive"))
      (node (ref "SW9") (pin "3") (pinfunction "3_3") (pintype "passive"))
    )
    (net (code "142") (name "Net-(D76-A)") (class "Default")
      (node (ref "D76") (pin "1") (pinfunction "A_1") (pintype "passive"))
      (node (ref "SW9") (pin "4") (pinfunction "4_4") (pintype "passive"))
    )
    (net (code "143") (name "Net-(D77-A)") (class "Default")
      (node (ref "D77") (pin "1") (pinfunction "A_1") (pintype "passive"))
      (node (ref "SW9") (pin "5") (pinfunction "5_5") (pintype "passive"))
    )
    (net (code "144") (name "Net-(D78-A)") (class "Default")
      (node (ref "D78") (pin "1") (pinfunction "A_1") (pintype "passive"))
      (node (ref "SW9") (pin "6") (pinfunction "6_6") (pintype "passive"))
    )
    (net (code "145") (name "Net-(D79-A)") (class "Default")
      (node (ref "D79") (pin "1") (pinfunction "A_1") (pintype "passive"))
      (node (ref "SW9") (pin "7") (pinfunction "7_7") (pintype "passive"))
    )
    (net (code "146") (name "Net-(D80-A)") (class "Default")
      (node (ref "D80") (pin "1") (pinfunction "A_1") (pintype "passive"))
      (node (ref "SW9") (pin "8") (pinfunction "8_8") (pintype "passive"))
    )
    (net (code "147") (name "Net-(D81-A)") (class "Default")
      (node (ref "D81") (pin "1") (pinfunction "A_1") (pintype "passive"))
      (node (ref "SW10") (pin "1") (pinfunction "1_1") (pintype "passive"))
    )
    (net (code "148") (name "Net-(D82-A)") (class "Default")
      (node (ref "D82") (pin "1") (pinfunction "A_1") (pintype "passive"))
      (node (ref "SW10") (pin "2") (pinfunction "2_2") (pintype "passive"))
    )
    (net (code "149") (name "Net-(D83-A)") (class "Default")
      (node (ref "D83") (pin "1") (pinfunction "A_1") (pintype "passive"))
      (node (ref "SW10") (pin "3") (pinfunction "3_3") (pintype "passive"))
    )
    (net (code "150") (name "Net-(D84-A)") (class "Default")
      (node (ref "D84") (pin "1") (pinfunction "A_1") (pintype "passive"))
      (node (ref "SW10") (pin "4") (pinfunction "4_4") (pintype "passive"))
    )
    (net (code "151") (name "Net-(D85-A)") (class "Default")
      (node (ref "D85") (pin "1") (pinfunction "A_1") (pintype "passive"))
      (node (ref "SW10") (pin "5") (pinfunction "5_5") (pintype "passive"))
    )
    (net (code "152") (name "Net-(D86-A)") (class "Default")
      (node (ref "D86") (pin "1") (pinfunction "A_1") (pintype "passive"))
      (node (ref "SW10") (pin "6") (pinfunction "6_6") (pintype "passive"))
    )
    (net (code "153") (name "Net-(D87-A)") (class "Default")
      (node (ref "D87") (pin "1") (pinfunction "A_1") (pintype "passive"))
      (node (ref "SW10") (pin "7") (pinfunction "7_7") (pintype "passive"))
    )
    (net (code "154") (name "Net-(D88-A)") (class "Default")
      (node (ref "D88") (pin "1") (pinfunction "A_1") (pintype "passive"))
      (node (ref "SW10") (pin "8") (pinfunction "8_8") (pintype "passive"))
    )
    (net (code "155") (name "Net-(D89-A)") (class "Default")
      (node (ref "D89") (pin "1") (pinfunction "A_1") (pintype "passive"))
      (node (ref "SW11") (pin "1") (pinfunction "1_1") (pintype "passive"))
    )
    (net (code "156") (name "Net-(D90-A)") (class "Default")
      (node (ref "D90") (pin "1") (pinfunction "A_1") (pintype "passive"))
      (node (ref "SW11") (pin "2") (pinfunction "2_2") (pintype "passive"))
    )
    (net (code "157") (name "Net-(D91-A)") (class "Default")
      (node (ref "D91") (pin "1") (pinfunction "A_1") (pintype "passive"))
      (node (ref "SW11") (pin "3") (pinfunction "3_3") (pintype "passive"))
    )
    (net (code "158") (name "Net-(D92-A)") (class "Default")
      (node (ref "D92") (pin "1") (pinfunction "A_1") (pintype "passive"))
      (node (ref "SW11") (pin "4") (pinfunction "4_4") (pintype "passive"))
    )
    (net (code "159") (name "Net-(D93-A)") (class "Default")
      (node (ref "D93") (pin "1") (pinfunction "A_1") (pintype "passive"))
      (node (ref "SW11") (pin "5") (pinfunction "5_5") (pintype "passive"))
    )
    (net (code "160") (name "Net-(D94-A)") (class "Default")
      (node (ref "D94") (pin "1") (pinfunction "A_1") (pintype "passive"))
      (node (ref "SW11") (pin "6") (pinfunction "6_6") (pintype "passive"))
    )
    (net (code "161") (name "Net-(D95-A)") (class "Default")
      (node (ref "D95") (pin "1") (pinfunction "A_1") (pintype "passive"))
      (node (ref "SW11") (pin "7") (pinfunction "7_7") (pintype "passive"))
    )
    (net (code "162") (name "Net-(D96-A)") (class "Default")
      (node (ref "D96") (pin "1") (pinfunction "A_1") (pintype "passive"))
      (node (ref "SW11") (pin "8") (pinfunction "8_8") (pintype "passive"))
    )
    (net (code "163") (name "Net-(D97-A)") (class "Default")
      (node (ref "D97") (pin "1") (pinfunction "A_1") (pintype "passive"))
      (node (ref "SW12") (pin "1") (pinfunction "1_1") (pintype "passive"))
    )
    (net (code "164") (name "Net-(D98-A)") (class "Default")
      (node (ref "D98") (pin "1") (pinfunction "A_1") (pintype "passive"))
      (node (ref "SW12") (pin "2") (pinfunction "2_2") (pintype "passive"))
    )
    (net (code "165") (name "Net-(D99-A)") (class "Default")
      (node (ref "D99") (pin "1") (pinfunction "A_1") (pintype "passive"))
      (node (ref "SW12") (pin "3") (pinfunction "3_3") (pintype "passive"))
    )
    (net (code "166") (name "Net-(D100-A)") (class "Default")
      (node (ref "D100") (pin "1") (pinfunction "A_1") (pintype "passive"))
      (node (ref "SW12") (pin "4") (pinfunction "4_4") (pintype "passive"))
    )
    (net (code "167") (name "Net-(D101-A)") (class "Default")
      (node (ref "D101") (pin "1") (pinfunction "A_1") (pintype "passive"))
      (node (ref "SW12") (pin "5") (pinfunction "5_5") (pintype "passive"))
    )
    (net (code "168") (name "Net-(D102-A)") (class "Default")
      (node (ref "D102") (pin "1") (pinfunction "A_1") (pintype "passive"))
      (node (ref "SW12") (pin "6") (pinfunction "6_6") (pintype "passive"))
    )
    (net (code "169") (name "Net-(D103-A)") (class "Default")
      (node (ref "D103") (pin "1") (pinfunction "A_1") (pintype "passive"))
      (node (ref "SW12") (pin "7") (pinfunction "7_7") (pintype "passive"))
    )
    (net (code "170") (name "Net-(D104-A)") (class "Default")
      (node (ref "D104") (pin "1") (pinfunction "A_1") (pintype "passive"))
      (node (ref "SW12") (pin "8") (pinfunction "8_8") (pintype "passive"))
    )
    (net (code "171") (name "Net-(D105-A)") (class "Default")
      (node (ref "D105") (pin "1") (pinfunction "A_1") (pintype "passive"))
      (node (ref "SW13") (pin "1") (pinfunction "1_1") (pintype "passive"))
    )
    (net (code "172") (name "Net-(D106-A)") (class "Default")
      (node (ref "D106") (pin "1") (pinfunction "A_1") (pintype "passive"))
      (node (ref "SW13") (pin "2") (pinfunction "2_2") (pintype "passive"))
    )
    (net (code "173") (name "Net-(D107-A)") (class "Default")
      (node (ref "D107") (pin "1") (pinfunction "A_1") (pintype "passive"))
      (node (ref "SW13") (pin "3") (pinfunction "3_3") (pintype "passive"))
    )
    (net (code "174") (name "Net-(D108-A)") (class "Default")
      (node (ref "D108") (pin "1") (pinfunction "A_1") (pintype "passive"))
      (node (ref "SW13") (pin "4") (pinfunction "4_4") (pintype "passive"))
    )
    (net (code "175") (name "Net-(D109-A)") (class "Default")
      (node (ref "D109") (pin "1") (pinfunction "A_1") (pintype "passive"))
      (node (ref "SW13") (pin "5") (pinfunction "5_5") (pintype "passive"))
    )
    (net (code "176") (name "Net-(D110-A)") (class "Default")
      (node (ref "D110") (pin "1") (pinfunction "A_1") (pintype "passive"))
      (node (ref "SW13") (pin "6") (pinfunction "6_6") (pintype "passive"))
    )
    (net (code "177") (name "Net-(D111-A)") (class "Default")
      (node (ref "D111") (pin "1") (pinfunction "A_1") (pintype "passive"))
      (node (ref "SW13") (pin "7") (pinfunction "7_7") (pintype "passive"))
    )
    (net (code "178") (name "Net-(D112-A)") (class "Default")
      (node (ref "D112") (pin "1") (pinfunction "A_1") (pintype "passive"))
      (node (ref "SW13") (pin "8") (pinfunction "8_8") (pintype "passive"))
    )
    (net (code "179") (name "Net-(D113-A)") (class "Default")
      (node (ref "D113") (pin "1") (pinfunction "A_1") (pintype "passive"))
      (node (ref "SW14") (pin "1") (pinfunction "1_1") (pintype "passive"))
    )
    (net (code "180") (name "Net-(D114-A)") (class "Default")
      (node (ref "D114") (pin "1") (pinfunction "A_1") (pintype "passive"))
      (node (ref "SW14") (pin "2") (pinfunction "2_2") (pintype "passive"))
    )
    (net (code "181") (name "Net-(D115-A)") (class "Default")
      (node (ref "D115") (pin "1") (pinfunction "A_1") (pintype "passive"))
      (node (ref "SW14") (pin "3") (pinfunction "3_3") (pintype "passive"))
    )
    (net (code "182") (name "Net-(D116-A)") (class "Default")
      (node (ref "D116") (pin "1") (pinfunction "A_1") (pintype "passive"))
      (node (ref "SW14") (pin "4") (pinfunction "4_4") (pintype "passive"))
    )
    (net (code "183") (name "Net-(D117-A)") (class "Default")
      (node (ref "D117") (pin "1") (pinfunction "A_1") (pintype "passive"))
      (node (ref "SW14") (pin "5") (pinfunction "5_5") (pintype "passive"))
    )
    (net (code "184") (name "Net-(D118-A)") (class "Default")
      (node (ref "D118") (pin "1") (pinfunction "A_1") (pintype "passive"))
      (node (ref "SW14") (pin "6") (pinfunction "6_6") (pintype "passive"))
    )
    (net (code "185") (name "Net-(D119-A)") (class "Default")
      (node (ref "D119") (pin "1") (pinfunction "A_1") (pintype "passive"))
      (node (ref "SW14") (pin "7") (pinfunction "7_7") (pintype "passive"))
    )
    (net (code "186") (name "Net-(D120-A)") (class "Default")
      (node (ref "D120") (pin "1") (pinfunction "A_1") (pintype "passive"))
      (node (ref "SW14") (pin "8") (pinfunction "8_8") (pintype "passive"))
    )
    (net (code "187") (name "Net-(D121-A)") (class "Default")
      (node (ref "D121") (pin "1") (pinfunction "A_1") (pintype "passive"))
      (node (ref "SW15") (pin "1") (pinfunction "1_1") (pintype "passive"))
    )
    (net (code "188") (name "Net-(D122-A)") (class "Default")
      (node (ref "D122") (pin "1") (pinfunction "A_1") (pintype "passive"))
      (node (ref "SW15") (pin "2") (pinfunction "2_2") (pintype "passive"))
    )
    (net (code "189") (name "Net-(D123-A)") (class "Default")
      (node (ref "D123") (pin "1") (pinfunction "A_1") (pintype "passive"))
      (node (ref "SW15") (pin "3") (pinfunction "3_3") (pintype "passive"))
    )
    (net (code "190") (name "Net-(D124-A)") (class "Default")
      (node (ref "D124") (pin "1") (pinfunction "A_1") (pintype "passive"))
      (node (ref "SW15") (pin "4") (pinfunction "4_4") (pintype "passive"))
    )
    (net (code "191") (name "Net-(D125-A)") (class "Default")
      (node (ref "D125") (pin "1") (pinfunction "A_1") (pintype "passive"))
      (node (ref "SW15") (pin "5") (pinfunction "5_5") (pintype "passive"))
    )
    (net (code "192") (name "Net-(D126-A)") (class "Default")
      (node (ref "D126") (pin "1") (pinfunction "A_1") (pintype "passive"))
      (node (ref "SW15") (pin "6") (pinfunction "6_6") (pintype "passive"))
    )
    (net (code "193") (name "Net-(D127-A)") (class "Default")
      (node (ref "D127") (pin "1") (pinfunction "A_1") (pintype "passive"))
      (node (ref "SW15") (pin "7") (pinfunction "7_7") (pintype "passive"))
    )
    (net (code "194") (name "Net-(D128-A)") (class "Default")
      (node (ref "D128") (pin "1") (pinfunction "A_1") (pintype "passive"))
      (node (ref "SW15") (pin "8") (pinfunction "8_8") (pintype "passive"))
    )
    (net (code "195") (name "Net-(LED0-A)") (class "Default")
      (node (ref "LED0") (pin "1") (pinfunction "A_1") (pintype "passive"))
      (node (ref "R9") (pin "1") (pinfunction "1_1") (pintype "passive"))
    )
    (net (code "196") (name "Net-(LED1-A)") (class "Default")
      (node (ref "LED1") (pin "1") (pinfunction "A_1") (pintype "passive"))
      (node (ref "R10") (pin "1") (pinfunction "1_1") (pintype "passive"))
    )
    (net (code "197") (name "Net-(LED2-A)") (class "Default")
      (node (ref "LED2") (pin "1") (pinfunction "A_1") (pintype "passive"))
      (node (ref "R11") (pin "1") (pinfunction "1_1") (pintype "passive"))
    )
    (net (code "198") (name "Net-(LED3-A)") (class "Default")
      (node (ref "LED3") (pin "1") (pinfunction "A_1") (pintype "passive"))
      (node (ref "R12") (pin "1") (pinfunction "1_1") (pintype "passive"))
    )
    (net (code "199") (name "Net-(LED4-A)") (class "Default")
      (node (ref "LED4") (pin "1") (pinfunction "A_1") (pintype "passive"))
      (node (ref "R13") (pin "1") (pinfunction "1_1") (pintype "passive"))
    )
    (net (code "200") (name "Net-(LED5-A)") (class "Default")
      (node (ref "LED5") (pin "1") (pinfunction "A_1") (pintype "passive"))
      (node (ref "R14") (pin "1") (pinfunction "1_1") (pintype "passive"))
    )
    (net (code "201") (name "Net-(LED6-A)") (class "Default")
      (node (ref "LED6") (pin "1") (pinfunction "A_1") (pintype "passive"))
      (node (ref "R15") (pin "1") (pinfunction "1_1") (pintype "passive"))
    )
    (net (code "202") (name "Net-(LED7-A)") (class "Default")
      (node (ref "LED7") (pin "1") (pinfunction "A_1") (pintype "passive"))
      (node (ref "R16") (pin "1") (pinfunction "1_1") (pintype "passive"))
    )
    (net (code "203") (name "Net-(LED8-A)") (class "Default")
      (node (ref "LED8") (pin "1") (pinfunction "A_1") (pintype "passive"))
      (node (ref "R17") (pin "1") (pinfunction "1_1") (pintype "passive"))
    )
    (net (code "204") (name "Net-(LED9-A)") (class "Default")
      (node (ref "LED9") (pin "1") (pinfunction "A_1") (pintype "passive"))
      (node (ref "R18") (pin "1") (pinfunction "1_1") (pintype "passive"))
    )
    (net (code "205") (name "Net-(LED10-A)") (class "Default")
      (node (ref "LED10") (pin "1") (pinfunction "A_1") (pintype "passive"))
      (node (ref "R19") (pin "1") (pinfunction "1_1") (pintype "passive"))
    )
    (net (code "206") (name "Net-(LED11-A)") (class "Default")
      (node (ref "LED11") (pin "1") (pinfunction "A_1") (pintype "passive"))
      (node (ref "R20") (pin "1") (pinfunction "1_1") (pintype "passive"))
    )
    (net (code "207") (name "Net-(LED12-A)") (class "Default")
      (node (ref "LED12") (pin "1") (pinfunction "A_1") (pintype "passive"))
      (node (ref "R21") (pin "1") (pinfunction "1_1") (pintype "passive"))
    )
    (net (code "208") (name "Net-(LED13-A)") (class "Default")
      (node (ref "LED13") (pin "1") (pinfunction "A_1") (pintype "passive"))
      (node (ref "R22") (pin "1") (pinfunction "1_1") (pintype "passive"))
    )
    (net (code "209") (name "Net-(LED14-A)") (class "Default")
      (node (ref "LED14") (pin "1") (pinfunction "A_1") (pintype "passive"))
      (node (ref "R23") (pin "1") (pinfunction "1_1") (pintype "passive"))
    )
    (net (code "210") (name "Net-(LED15-A)") (class "Default")
      (node (ref "LED15") (pin "1") (pinfunction "A_1") (pintype "passive"))
      (node (ref "R24") (pin "1") (pinfunction "1_1") (pintype "passive"))
    )
    (net (code "211") (name "Net-(LED16-A)") (class "Default")
      (node (ref "LED16") (pin "1") (pinfunction "A_1") (pintype "passive"))
      (node (ref "R25") (pin "1") (pinfunction "1_1") (pintype "passive"))
    )
    (net (code "212") (name "Net-(LED17-A)") (class "Default")
      (node (ref "LED17") (pin "1") (pinfunction "A_1") (pintype "passive"))
      (node (ref "R26") (pin "1") (pinfunction "1_1") (pintype "passive"))
    )
    (net (code "213") (name "Net-(LED18-A)") (class "Default")
      (node (ref "LED18") (pin "1") (pinfunction "A_1") (pintype "passive"))
      (node (ref "R27") (pin "1") (pinfunction "1_1") (pintype "passive"))
    )
    (net (code "214") (name "Net-(LED19-A)") (class "Default")
      (node (ref "LED19") (pin "1") (pinfunction "A_1") (pintype "passive"))
      (node (ref "R28") (pin "1") (pinfunction "1_1") (pintype "passive"))
    )
    (net (code "215") (name "Net-(LED20-A)") (class "Default")
      (node (ref "LED20") (pin "1") (pinfunction "A_1") (pintype "passive"))
      (node (ref "R29") (pin "1") (pinfunction "1_1") (pintype "passive"))
    )
    (net (code "216") (name "Net-(LED21-A)") (class "Default")
      (node (ref "LED21") (pin "1") (pinfunction "A_1") (pintype "passive"))
      (node (ref "R30") (pin "1") (pinfunction "1_1") (pintype "passive"))
    )
    (net (code "217") (name "Net-(LED22-A)") (class "Default")
      (node (ref "LED22") (pin "1") (pinfunction "A_1") (pintype "passive"))
      (node (ref "R31") (pin "1") (pinfunction "1_1") (pintype "passive"))
    )
    (net (code "218") (name "Net-(LED23-A)") (class "Default")
      (node (ref "LED23") (pin "1") (pinfunction "A_1") (pintype "passive"))
      (node (ref "R32") (pin "1") (pinfunction "1_1") (pintype "passive"))
    )
    (net (code "219") (name "Net-(LED24-A)") (class "Default")
      (node (ref "LED24") (pin "1") (pinfunction "A_1") (pintype "passive"))
      (node (ref "R33") (pin "1") (pinfunction "1_1") (pintype "passive"))
    )
    (net (code "220") (name "Net-(LED25-A)") (class "Default")
      (node (ref "LED25") (pin "1") (pinfunction "A_1") (pintype "passive"))
      (node (ref "R34") (pin "1") (pinfunction "1_1") (pintype "passive"))
    )
    (net (code "221") (name "Net-(LED26-A)") (class "Default")
      (node (ref "LED26") (pin "1") (pinfunction "A_1") (pintype "passive"))
      (node (ref "R35") (pin "1") (pinfunction "1_1") (pintype "passive"))
    )
    (net (code "222") (name "Net-(LED27-A)") (class "Default")
      (node (ref "LED27") (pin "1") (pinfunction "A_1") (pintype "passive"))
      (node (ref "R36") (pin "1") (pinfunction "1_1") (pintype "passive"))
    )
    (net (code "223") (name "Net-(LED28-A)") (class "Default")
      (node (ref "LED28") (pin "1") (pinfunction "A_1") (pintype "passive"))
      (node (ref "R37") (pin "1") (pinfunction "1_1") (pintype "passive"))
    )
    (net (code "224") (name "Net-(LED29-A)") (class "Default")
      (node (ref "LED29") (pin "1") (pinfunction "A_1") (pintype "passive"))
      (node (ref "R38") (pin "1") (pinfunction "1_1") (pintype "passive"))
    )
    (net (code "225") (name "Net-(LED30-A)") (class "Default")
      (node (ref "LED30") (pin "1") (pinfunction "A_1") (pintype "passive"))
      (node (ref "R39") (pin "1") (pinfunction "1_1") (pintype "passive"))
    )
    (net (code "226") (name "Net-(LED31-A)") (class "Default")
      (node (ref "LED31") (pin "1") (pinfunction "A_1") (pintype "passive"))
      (node (ref "R40") (pin "1") (pinfunction "1_1") (pintype "passive"))
    )
    (net (code "227") (name "Net-(LED32-A)") (class "Default")
      (node (ref "LED32") (pin "1") (pinfunction "A_1") (pintype "passive"))
      (node (ref "R41") (pin "1") (pinfunction "1_1") (pintype "passive"))
    )
    (net (code "228") (name "Net-(LED33-K)") (class "Default")
      (node (ref "LED33") (pin "2") (pinfunction "K_2") (pintype "passive"))
      (node (ref "R42") (pin "2") (pinfunction "2_2") (pintype "passive"))
    )
    (net (code "229") (name "Net-(LED34-K)") (class "Default")
      (node (ref "LED34") (pin "2") (pinfunction "K_2") (pintype "passive"))
      (node (ref "R43") (pin "2") (pinfunction "2_2") (pintype "passive"))
    )
    (net (code "230") (name "Net-(LED35-K)") (class "Default")
      (node (ref "LED35") (pin "2") (pinfunction "K_2") (pintype "passive"))
      (node (ref "R44") (pin "2") (pinfunction "2_2") (pintype "passive"))
    )
    (net (code "231") (name "Net-(LED36-A)") (class "Default")
      (node (ref "LED36") (pin "1") (pinfunction "A_1") (pintype "passive"))
      (node (ref "R45") (pin "2") (pinfunction "2_2") (pintype "passive"))
    )
    (net (code "232") (name "Net-(LED37-K)") (class "Default")
      (node (ref "LED37") (pin "2") (pinfunction "K_2") (pintype "passive"))
      (node (ref "R46") (pin "2") (pinfunction "2_2") (pintype "passive"))
    )
    (net (code "233") (name "Net-(LED38-K)") (class "Default")
      (node (ref "LED38") (pin "2") (pinfunction "K_2") (pintype "passive"))
      (node (ref "R47") (pin "2") (pinfunction "2_2") (pintype "passive"))
    )
    (net (code "234") (name "Net-(LED39-K)") (class "Default")
      (node (ref "LED39") (pin "2") (pinfunction "K_2") (pintype "passive"))
      (node (ref "R48") (pin "2") (pinfunction "2_2") (pintype "passive"))
    )
    (net (code "235") (name "Net-(LED40-K)") (class "Default")
      (node (ref "LED40") (pin "2") (pinfunction "K_2") (pintype "passive"))
      (node (ref "R49") (pin "2") (pinfunction "2_2") (pintype "passive"))
    )
    (net (code "236") (name "Net-(LED41-A)") (class "Default")
      (node (ref "LED41") (pin "1") (pinfunction "A_1") (pintype "passive"))
      (node (ref "R50") (pin "1") (pinfunction "1_1") (pintype "passive"))
    )
    (net (code "237") (name "Net-(LED42-A)") (class "Default")
      (node (ref "LED42") (pin "1") (pinfunction "A_1") (pintype "passive"))
      (node (ref "R51") (pin "1") (pinfunction "1_1") (pintype "passive"))
    )
    (net (code "238") (name "Net-(LED43-K)") (class "Default")
      (node (ref "LED43") (pin "2") (pinfunction "K_2") (pintype "passive"))
      (node (ref "R52") (pin "2") (pinfunction "2_2") (pintype "passive"))
    )
    (net (code "239") (name "Net-(LED44-K)") (class "Default")
      (node (ref "LED44") (pin "2") (pinfunction "K_2") (pintype "passive"))
      (node (ref "R53") (pin "2") (pinfunction "2_2") (pintype "passive"))
    )
    (net (code "240") (name "Net-(LED45-K)") (class "Default")
      (node (ref "LED45") (pin "2") (pinfunction "K_2") (pintype "passive"))
      (node (ref "R54") (pin "2") (pinfunction "2_2") (pintype "passive"))
    )
    (net (code "241") (name "Net-(LED46-K)") (class "Default")
      (node (ref "LED46") (pin "2") (pinfunction "K_2") (pintype "passive"))
      (node (ref "R55") (pin "2") (pinfunction "2_2") (pintype "passive"))
    )
    (net (code "242") (name "Net-(LED47-K)") (class "Default")
      (node (ref "LED47") (pin "2") (pinfunction "K_2") (pintype "passive"))
      (node (ref "R56") (pin "2") (pinfunction "2_2") (pintype "passive"))
    )
    (net (code "243") (name "Net-(LED48-A)") (class "Default")
      (node (ref "LED48") (pin "1") (pinfunction "A_1") (pintype "passive"))
      (node (ref "R57") (pin "1") (pinfunction "1_1") (pintype "passive"))
    )
    (net (code "244") (name "Net-(LED49-A)") (class "Default")
      (node (ref "LED49") (pin "1") (pinfunction "A_1") (pintype "passive"))
      (node (ref "R58") (pin "1") (pinfunction "1_1") (pintype "passive"))
    )
    (net (code "245") (name "Net-(LED50-K)") (class "Default")
      (node (ref "LED50") (pin "2") (pinfunction "K_2") (pintype "passive"))
      (node (ref "R59") (pin "2") (pinfunction "2_2") (pintype "passive"))
    )
    (net (code "246") (name "Net-(LED51-K)") (class "Default")
      (node (ref "LED51") (pin "2") (pinfunction "K_2") (pintype "passive"))
      (node (ref "R60") (pin "2") (pinfunction "2_2") (pintype "passive"))
    )
    (net (code "247") (name "Net-(LED52-K)") (class "Default")
      (node (ref "LED52") (pin "2") (pinfunction "K_2") (pintype "passive"))
      (node (ref "R61") (pin "2") (pinfunction "2_2") (pintype "passive"))
    )
    (net (code "248") (name "Net-(LED53-K)") (class "Default")
      (node (ref "LED53") (pin "2") (pinfunction "K_2") (pintype "passive"))
      (node (ref "R62") (pin "2") (pinfunction "2_2") (pintype "passive"))
    )
    (net (code "249") (name "Net-(LED54-K)") (class "Default")
      (node (ref "LED54") (pin "2") (pinfunction "K_2") (pintype "passive"))
      (node (ref "R63") (pin "2") (pinfunction "2_2") (pintype "passive"))
    )
    (net (code "250") (name "Net-(LED55-A)") (class "Default")
      (node (ref "LED55") (pin "1") (pinfunction "A_1") (pintype "passive"))
      (node (ref "R64") (pin "1") (pinfunction "1_1") (pintype "passive"))
    )
    (net (code "251") (name "Net-(LED56-A)") (class "Default")
      (node (ref "LED56") (pin "1") (pinfunction "A_1") (pintype "passive"))
      (node (ref "R65") (pin "1") (pinfunction "1_1") (pintype "passive"))
    )
    (net (code "252") (name "Net-(LED57-K)") (class "Default")
      (node (ref "LED57") (pin "2") (pinfunction "K_2") (pintype "passive"))
      (node (ref "R66") (pin "2") (pinfunction "2_2") (pintype "passive"))
    )
    (net (code "253") (name "Net-(LED58-K)") (class "Default")
      (node (ref "LED58") (pin "2") (pinfunction "K_2") (pintype "passive"))
      (node (ref "R67") (pin "2") (pinfunction "2_2") (pintype "passive"))
    )
    (net (code "254") (name "Net-(LED59-K)") (class "Default")
      (node (ref "LED59") (pin "2") (pinfunction "K_2") (pintype "passive"))
      (node (ref "R68") (pin "2") (pinfunction "2_2") (pintype "passive"))
    )
    (net (code "255") (name "Net-(LED60-K)") (class "Default")
      (node (ref "LED60") (pin "2") (pinfunction "K_2") (pintype "passive"))
      (node (ref "R69") (pin "2") (pinfunction "2_2") (pintype "passive"))
    )
    (net (code "256") (name "Net-(LED61-K)") (class "Default")
      (node (ref "LED61") (pin "2") (pinfunction "K_2") (pintype "passive"))
      (node (ref "R70") (pin "2") (pinfunction "2_2") (pintype "passive"))
    )
    (net (code "257") (name "Net-(LED62-A)") (class "Default")
      (node (ref "LED62") (pin "1") (pinfunction "A_1") (pintype "passive"))
      (node (ref "R71") (pin "1") (pinfunction "1_1") (pintype "passive"))
    )
    (net (code "258") (name "Net-(LED63-A)") (class "Default")
      (node (ref "LED63") (pin "1") (pinfunction "A_1") (pintype "passive"))
      (node (ref "R72") (pin "1") (pinfunction "1_1") (pintype "passive"))
    )
    (net (code "259") (name "Net-(LED64-K)") (class "Default")
      (node (ref "LED64") (pin "2") (pinfunction "K_2") (pintype "passive"))
      (node (ref "R73") (pin "2") (pinfunction "2_2") (pintype "passive"))
    )
    (net (code "260") (name "Net-(LED65-K)") (class "Default")
      (node (ref "LED65") (pin "2") (pinfunction "K_2") (pintype "passive"))
      (node (ref "R74") (pin "2") (pinfunction "2_2") (pintype "passive"))
    )
    (net (code "261") (name "Net-(LED66-A)") (class "Default")
      (node (ref "LED66") (pin "1") (pinfunction "A_1") (pintype "passive"))
      (node (ref "R89") (pin "1") (pinfunction "1_1") (pintype "passive"))
    )
    (net (code "262") (name "Net-(LED67-A)") (class "Default")
      (node (ref "LED67") (pin "1") (pinfunction "A_1") (pintype "passive"))
      (node (ref "R90") (pin "1") (pinfunction "1_1") (pintype "passive"))
    )
    (net (code "263") (name "Net-(LED68-A)") (class "Default")
      (node (ref "LED68") (pin "1") (pinfunction "A_1") (pintype "passive"))
      (node (ref "R91") (pin "1") (pinfunction "1_1") (pintype "passive"))
    )
    (net (code "264") (name "Net-(LED69-A)") (class "Default")
      (node (ref "LED69") (pin "1") (pinfunction "A_1") (pintype "passive"))
      (node (ref "R92") (pin "1") (pinfunction "1_1") (pintype "passive"))
    )
    (net (code "265") (name "Net-(LED70-A)") (class "Default")
      (node (ref "LED70") (pin "1") (pinfunction "A_1") (pintype "passive"))
      (node (ref "R93") (pin "1") (pinfunction "1_1") (pintype "passive"))
    )
    (net (code "266") (name "Net-(LED71-A)") (class "Default")
      (node (ref "LED71") (pin "1") (pinfunction "A_1") (pintype "passive"))
      (node (ref "R94") (pin "1") (pinfunction "1_1") (pintype "passive"))
    )
    (net (code "267") (name "Net-(LED72-A)") (class "Default")
      (node (ref "LED72") (pin "1") (pinfunction "A_1") (pintype "passive"))
      (node (ref "R95") (pin "1") (pinfunction "1_1") (pintype "passive"))
    )
    (net (code "268") (name "Net-(LED73-A)") (class "Default")
      (node (ref "LED73") (pin "1") (pinfunction "A_1") (pintype "passive"))
      (node (ref "R96") (pin "1") (pinfunction "1_1") (pintype "passive"))
    )
    (net (code "269") (name "Net-(LED74-K)") (class "Default")
      (node (ref "LED74") (pin "2") (pinfunction "K_2") (pintype "passive"))
      (node (ref "R97") (pin "2") (pinfunction "2_2") (pintype "passive"))
    )
    (net (code "270") (name "Net-(LED75-A)") (class "Default")
      (node (ref "LED75") (pin "1") (pinfunction "A_1") (pintype "passive"))
      (node (ref "R98") (pin "1") (pinfunction "1_1") (pintype "passive"))
    )
    (net (code "271") (name "Net-(LED76-A)") (class "Default")
      (node (ref "LED76") (pin "1") (pinfunction "A_1") (pintype "passive"))
      (node (ref "R99") (pin "1") (pinfunction "1_1") (pintype "passive"))
    )
    (net (code "272") (name "Net-(LED77-A)") (class "Default")
      (node (ref "LED77") (pin "1") (pinfunction "A_1") (pintype "passive"))
      (node (ref "R100") (pin "1") (pinfunction "1_1") (pintype "passive"))
    )
    (net (code "273") (name "Net-(LED78-A)") (class "Default")
      (node (ref "LED78") (pin "1") (pinfunction "A_1") (pintype "passive"))
      (node (ref "R101") (pin "1") (pinfunction "1_1") (pintype "passive"))
    )
    (net (code "274") (name "Net-(R75-Pad1)") (class "Default")
      (node (ref "R75") (pin "1") (pinfunction "1_1") (pintype "passive"))
      (node (ref "R76") (pin "1") (pinfunction "1_1") (pintype "passive"))
      (node (ref "SW16") (pin "1") (pinfunction "K_1") (pintype "passive"))
    )
    (net (code "275") (name "Net-(R77-Pad2)") (class "Default")
      (node (ref "R77") (pin "2") (pinfunction "2_2") (pintype "passive"))
      (node (ref "U5") (pin "3") (pintype "input"))
    )
    (net (code "276") (name "Net-(R78-Pad1)") (class "Default")
      (node (ref "R78") (pin "1") (pinfunction "1_1") (pintype "passive"))
      (node (ref "U5") (pin "4") (pintype "output"))
    )
    (net (code "277") (name "Net-(R78-Pad2)") (class "Default")
      (node (ref "R78") (pin "2") (pinfunction "2_2") (pintype "passive"))
      (node (ref "S1") (pin "1") (pinfunction "1_1") (pintype "passive"))
    )
    (net (code "278") (name "Net-(R79-Pad1)") (class "Default")
      (node (ref "R79") (pin "1") (pinfunction "1_1") (pintype "passive"))
      (node (ref "RP1") (pin "3") (pinfunction "3_3") (pintype "passive"))
    )
    (net (code "279") (name "Net-(R79-Pad2)") (class "Default")
      (node (ref "R79") (pin "2") (pinfunction "2_2") (pintype "passive"))
      (node (ref "U5") (pin "6") (pintype "output"))
      (node (ref "U5") (pin "9") (pintype "input"))
    )
    (net (code "280") (name "Net-(R80-Pad2)") (class "Default")
      (node (ref "R80") (pin "2") (pinfunction "2_2") (pintype "passive"))
      (node (ref "U5") (pin "5") (pintype "input"))
    )
    (net (code "281") (name "Net-(R81-Pad2)") (class "Default")
      (node (ref "R81") (pin "2") (pinfunction "2_2") (pintype "passive"))
      (node (ref "S1") (pin "3") (pinfunction "3_3") (pintype "passive"))
    )
    (net (code "282") (name "Net-(R82-Pad1)") (class "Default")
      (node (ref "R82") (pin "1") (pinfunction "1_1") (pintype "passive"))
      (node (ref "R83") (pin "1") (pinfunction "1_1") (pintype "passive"))
      (node (ref "SW17") (pin "1") (pinfunction "K_1") (pintype "passive"))
    )
    (net (code "283") (name "Net-(R84-Pad2)") (class "Default")
      (node (ref "R84") (pin "2") (pinfunction "2_2") (pintype "passive"))
      (node (ref "U5") (pin "11") (pintype "input"))
    )
    (net (code "284") (name "Net-(U1-A1)") (class "Default")
      (node (ref "R8") (pin "2") (pinfunction "2_2") (pintype "passive"))
      (node (ref "SW0") (pin "9") (pinfunction "9_9") (pintype "passive"))
      (node (ref "SW1") (pin "9") (pinfunction "9_9") (pintype "passive"))
      (node (ref "SW10") (pin "9") (pinfunction "9_9") (pintype "passive"))
      (node (ref "SW11") (pin "9") (pinfunction "9_9") (pintype "passive"))
      (node (ref "SW12") (pin "9") (pinfunction "9_9") (pintype "passive"))
      (node (ref "SW13") (pin "9") (pinfunction "9_9") (pintype "passive"))
      (node (ref "SW14") (pin "9") (pinfunction "9_9") (pintype "passive"))
      (node (ref "SW15") (pin "9") (pinfunction "9_9") (pintype "passive"))
      (node (ref "SW2") (pin "9") (pinfunction "9_9") (pintype "passive"))
      (node (ref "SW3") (pin "9") (pinfunction "9_9") (pintype "passive"))
      (node (ref "SW4") (pin "9") (pinfunction "9_9") (pintype "passive"))
      (node (ref "SW5") (pin "9") (pinfunction "9_9") (pintype "passive"))
      (node (ref "SW6") (pin "9") (pinfunction "9_9") (pintype "passive"))
      (node (ref "SW7") (pin "9") (pinfunction "9_9") (pintype "passive"))
      (node (ref "SW8") (pin "9") (pinfunction "9_9") (pintype "passive"))
      (node (ref "SW9") (pin "9") (pinfunction "9_9") (pintype "passive"))
      (node (ref "U1") (pin "2") (pinfunction "A1_2") (pintype "input"))
    )
    (net (code "285") (name "Net-(U1-A2)") (class "Default")
      (node (ref "R7") (pin "2") (pinfunction "2_2") (pintype "passive"))
      (node (ref "SW0") (pin "10") (pinfunction "10_10") (pintype "passive"))
      (node (ref "SW1") (pin "10") (pinfunction "10_10") (pintype "passive"))
      (node (ref "SW10") (pin "10") (pinfunction "10_10") (pintype "passive"))
      (node (ref "SW11") (pin "10") (pinfunction "10_10") (pintype "passive"))
      (node (ref "SW12") (pin "10") (pinfunction "10_10") (pintype "passive"))
      (node (ref "SW13") (pin "10") (pinfunction "10_10") (pintype "passive"))
      (node (ref "SW14") (pin "10") (pinfunction "10_10") (pintype "passive"))
      (node (ref "SW15") (pin "10") (pinfunction "10_10") (pintype "passive"))
      (node (ref "SW2") (pin "10") (pinfunction "10_10") (pintype "passive"))
      (node (ref "SW3") (pin "10") (pinfunction "10_10") (pintype "passive"))
      (node (ref "SW4") (pin "10") (pinfunction "10_10") (pintype "passive"))
      (node (ref "SW5") (pin "10") (pinfunction "10_10") (pintype "passive"))
      (node (ref "SW6") (pin "10") (pinfunction "10_10") (pintype "passive"))
      (node (ref "SW7") (pin "10") (pinfunction "10_10") (pintype "passive"))
      (node (ref "SW8") (pin "10") (pinfunction "10_10") (pintype "passive"))
      (node (ref "SW9") (pin "10") (pinfunction "10_10") (pintype "passive"))
      (node (ref "U1") (pin "3") (pinfunction "A2_3") (pintype "input"))
    )
    (net (code "286") (name "Net-(U1-A3)") (class "Default")
      (node (ref "R6") (pin "2") (pinfunction "2_2") (pintype "passive"))
      (node (ref "SW0") (pin "11") (pinfunction "11_11") (pintype "passive"))
      (node (ref "SW1") (pin "11") (pinfunction "11_11") (pintype "passive"))
      (node (ref "SW10") (pin "11") (pinfunction "11_11") (pintype "passive"))
      (node (ref "SW11") (pin "11") (pinfunction "11_11") (pintype "passive"))
      (node (ref "SW12") (pin "11") (pinfunction "11_11") (pintype "passive"))
      (node (ref "SW13") (pin "11") (pinfunction "11_11") (pintype "passive"))
      (node (ref "SW14") (pin "11") (pinfunction "11_11") (pintype "passive"))
      (node (ref "SW15") (pin "11") (pinfunction "11_11") (pintype "passive"))
      (node (ref "SW2") (pin "11") (pinfunction "11_11") (pintype "passive"))
      (node (ref "SW3") (pin "11") (pinfunction "11_11") (pintype "passive"))
      (node (ref "SW4") (pin "11") (pinfunction "11_11") (pintype "passive"))
      (node (ref "SW5") (pin "11") (pinfunction "11_11") (pintype "passive"))
      (node (ref "SW6") (pin "11") (pinfunction "11_11") (pintype "passive"))
      (node (ref "SW7") (pin "11") (pinfunction "11_11") (pintype "passive"))
      (node (ref "SW8") (pin "11") (pinfunction "11_11") (pintype "passive"))
      (node (ref "SW9") (pin "11") (pinfunction "11_11") (pintype "passive"))
      (node (ref "U1") (pin "4") (pinfunction "A3_4") (pintype "input"))
    )
    (net (code "287") (name "Net-(U1-A4)") (class "Default")
      (node (ref "R5") (pin "2") (pinfunction "2_2") (pintype "passive"))
      (node (ref "SW0") (pin "12") (pinfunction "12_12") (pintype "passive"))
      (node (ref "SW1") (pin "12") (pinfunction "12_12") (pintype "passive"))
      (node (ref "SW10") (pin "12") (pinfunction "12_12") (pintype "passive"))
      (node (ref "SW11") (pin "12") (pinfunction "12_12") (pintype "passive"))
      (node (ref "SW12") (pin "12") (pinfunction "12_12") (pintype "passive"))
      (node (ref "SW13") (pin "12") (pinfunction "12_12") (pintype "passive"))
      (node (ref "SW14") (pin "12") (pinfunction "12_12") (pintype "passive"))
      (node (ref "SW15") (pin "12") (pinfunction "12_12") (pintype "passive"))
      (node (ref "SW2") (pin "12") (pinfunction "12_12") (pintype "passive"))
      (node (ref "SW3") (pin "12") (pinfunction "12_12") (pintype "passive"))
      (node (ref "SW4") (pin "12") (pinfunction "12_12") (pintype "passive"))
      (node (ref "SW5") (pin "12") (pinfunction "12_12") (pintype "passive"))
      (node (ref "SW6") (pin "12") (pinfunction "12_12") (pintype "passive"))
      (node (ref "SW7") (pin "12") (pinfunction "12_12") (pintype "passive"))
      (node (ref "SW8") (pin "12") (pinfunction "12_12") (pintype "passive"))
      (node (ref "SW9") (pin "12") (pinfunction "12_12") (pintype "passive"))
      (node (ref "U1") (pin "5") (pinfunction "A4_5") (pintype "input"))
    )
    (net (code "288") (name "Net-(U1-A5)") (class "Default")
      (node (ref "R4") (pin "2") (pinfunction "2_2") (pintype "passive"))
      (node (ref "SW0") (pin "13") (pinfunction "13_13") (pintype "passive"))
      (node (ref "SW1") (pin "13") (pinfunction "13_13") (pintype "passive"))
      (node (ref "SW10") (pin "13") (pinfunction "13_13") (pintype "passive"))
      (node (ref "SW11") (pin "13") (pinfunction "13_13") (pintype "passive"))
      (node (ref "SW12") (pin "13") (pinfunction "13_13") (pintype "passive"))
      (node (ref "SW13") (pin "13") (pinfunction "13_13") (pintype "passive"))
      (node (ref "SW14") (pin "13") (pinfunction "13_13") (pintype "passive"))
      (node (ref "SW15") (pin "13") (pinfunction "13_13") (pintype "passive"))
      (node (ref "SW2") (pin "13") (pinfunction "13_13") (pintype "passive"))
      (node (ref "SW3") (pin "13") (pinfunction "13_13") (pintype "passive"))
      (node (ref "SW4") (pin "13") (pinfunction "13_13") (pintype "passive"))
      (node (ref "SW5") (pin "13") (pinfunction "13_13") (pintype "passive"))
      (node (ref "SW6") (pin "13") (pinfunction "13_13") (pintype "passive"))
      (node (ref "SW7") (pin "13") (pinfunction "13_13") (pintype "passive"))
      (node (ref "SW8") (pin "13") (pinfunction "13_13") (pintype "passive"))
      (node (ref "SW9") (pin "13") (pinfunction "13_13") (pintype "passive"))
      (node (ref "U1") (pin "6") (pinfunction "A5_6") (pintype "input"))
    )
    (net (code "289") (name "Net-(U1-A6)") (class "Default")
      (node (ref "R3") (pin "2") (pinfunction "2_2") (pintype "passive"))
      (node (ref "SW0") (pin "14") (pinfunction "14_14") (pintype "passive"))
      (node (ref "SW1") (pin "14") (pinfunction "14_14") (pintype "passive"))
      (node (ref "SW10") (pin "14") (pinfunction "14_14") (pintype "passive"))
      (node (ref "SW11") (pin "14") (pinfunction "14_14") (pintype "passive"))
      (node (ref "SW12") (pin "14") (pinfunction "14_14") (pintype "passive"))
      (node (ref "SW13") (pin "14") (pinfunction "14_14") (pintype "passive"))
      (node (ref "SW14") (pin "14") (pinfunction "14_14") (pintype "passive"))
      (node (ref "SW15") (pin "14") (pinfunction "14_14") (pintype "passive"))
      (node (ref "SW2") (pin "14") (pinfunction "14_14") (pintype "passive"))
      (node (ref "SW3") (pin "14") (pinfunction "14_14") (pintype "passive"))
      (node (ref "SW4") (pin "14") (pinfunction "14_14") (pintype "passive"))
      (node (ref "SW5") (pin "14") (pinfunction "14_14") (pintype "passive"))
      (node (ref "SW6") (pin "14") (pinfunction "14_14") (pintype "passive"))
      (node (ref "SW7") (pin "14") (pinfunction "14_14") (pintype "passive"))
      (node (ref "SW8") (pin "14") (pinfunction "14_14") (pintype "passive"))
      (node (ref "SW9") (pin "14") (pinfunction "14_14") (pintype "passive"))
      (node (ref "U1") (pin "7") (pinfunction "A6_7") (pintype "input"))
    )
    (net (code "290") (name "Net-(U1-A7)") (class "Default")
      (node (ref "R2") (pin "2") (pinfunction "2_2") (pintype "passive"))
      (node (ref "SW0") (pin "15") (pinfunction "15_15") (pintype "passive"))
      (node (ref "SW1") (pin "15") (pinfunction "15_15") (pintype "passive"))
      (node (ref "SW10") (pin "15") (pinfunction "15_15") (pintype "passive"))
      (node (ref "SW11") (pin "15") (pinfunction "15_15") (pintype "passive"))
      (node (ref "SW12") (pin "15") (pinfunction "15_15") (pintype "passive"))
      (node (ref "SW13") (pin "15") (pinfunction "15_15") (pintype "passive"))
      (node (ref "SW14") (pin "15") (pinfunction "15_15") (pintype "passive"))
      (node (ref "SW15") (pin "15") (pinfunction "15_15") (pintype "passive"))
      (node (ref "SW2") (pin "15") (pinfunction "15_15") (pintype "passive"))
      (node (ref "SW3") (pin "15") (pinfunction "15_15") (pintype "passive"))
      (node (ref "SW4") (pin "15") (pinfunction "15_15") (pintype "passive"))
      (node (ref "SW5") (pin "15") (pinfunction "15_15") (pintype "passive"))
      (node (ref "SW6") (pin "15") (pinfunction "15_15") (pintype "passive"))
      (node (ref "SW7") (pin "15") (pinfunction "15_15") (pintype "passive"))
      (node (ref "SW8") (pin "15") (pinfunction "15_15") (pintype "passive"))
      (node (ref "SW9") (pin "15") (pinfunction "15_15") (pintype "passive"))
      (node (ref "U1") (pin "8") (pinfunction "A7_8") (pintype "input"))
    )
    (net (code "291") (name "Net-(U1-A8)") (class "Default")
      (node (ref "R1") (pin "2") (pinfunction "2_2") (pintype "passive"))
      (node (ref "SW0") (pin "16") (pinfunction "16_16") (pintype "passive"))
      (node (ref "SW1") (pin "16") (pinfunction "16_16") (pintype "passive"))
      (node (ref "SW10") (pin "16") (pinfunction "16_16") (pintype "passive"))
      (node (ref "SW11") (pin "16") (pinfunction "16_16") (pintype "passive"))
      (node (ref "SW12") (pin "16") (pinfunction "16_16") (pintype "passive"))
      (node (ref "SW13") (pin "16") (pinfunction "16_16") (pintype "passive"))
      (node (ref "SW14") (pin "16") (pinfunction "16_16") (pintype "passive"))
      (node (ref "SW15") (pin "16") (pinfunction "16_16") (pintype "passive"))
      (node (ref "SW2") (pin "16") (pinfunction "16_16") (pintype "passive"))
      (node (ref "SW3") (pin "16") (pinfunction "16_16") (pintype "passive"))
      (node (ref "SW4") (pin "16") (pinfunction "16_16") (pintype "passive"))
      (node (ref "SW5") (pin "16") (pinfunction "16_16") (pintype "passive"))
      (node (ref "SW6") (pin "16") (pinfunction "16_16") (pintype "passive"))
      (node (ref "SW7") (pin "16") (pinfunction "16_16") (pintype "passive"))
      (node (ref "SW8") (pin "16") (pinfunction "16_16") (pintype "passive"))
      (node (ref "SW9") (pin "16") (pinfunction "16_16") (pintype "passive"))
      (node (ref "U1") (pin "9") (pinfunction "A8_9") (pintype "input"))
    )
    (net (code "292") (name "Net-(U3-Pad4)") (class "Default")
      (node (ref "U3") (pin "4") (pintype "input"))
      (node (ref "U4") (pin "12") (pintype "output"))
      (node (ref "U4") (pin "4") (pintype "input"))
    )
    (net (code "293") (name "Net-(U3-Pad8)") (class "Default")
      (node (ref "U3") (pin "8") (pintype "output"))
      (node (ref "U4") (pin "9") (pintype "input"))
    )
    (net (code "294") (name "Net-(U5-Pad10)") (class "Default")
      (node (ref "U5") (pin "10") (pintype "output"))
      (node (ref "U5") (pin "13") (pintype "input"))
    )
    (net (code "295") (name "VCC") (class "Default")
      (node (ref "C1") (pin "2") (pinfunction "2_2") (pintype "passive"))
      (node (ref "C10") (pin "2") (pinfunction "2_2") (pintype "passive"))
      (node (ref "C11") (pin "2") (pinfunction "2_2") (pintype "passive"))
      (node (ref "C12") (pin "2") (pinfunction "2_2") (pintype "passive"))
      (node (ref "C13") (pin "2") (pinfunction "2_2") (pintype "passive"))
      (node (ref "C14") (pin "2") (pinfunction "2_2") (pintype "passive"))
      (node (ref "C15") (pin "2") (pinfunction "2_2") (pintype "passive"))
      (node (ref "C2") (pin "2") (pinfunction "2_2") (pintype "passive"))
      (node (ref "C3") (pin "2") (pinfunction "2_2") (pintype "passive"))
      (node (ref "C4") (pin "2") (pinfunction "2_2") (pintype "passive"))
      (node (ref "C5") (pin "2") (pinfunction "2_2") (pintype "passive"))
      (node (ref "C6") (pin "2") (pinfunction "2_2") (pintype "passive"))
      (node (ref "C7") (pin "2") (pinfunction "2_2") (pintype "passive"))
      (node (ref "C8") (pin "2") (pinfunction "2_2") (pintype "passive"))
      (node (ref "C9") (pin "2") (pinfunction "2_2") (pintype "passive"))
      (node (ref "LED74") (pin "1") (pinfunction "A_1") (pintype "passive"))
      (node (ref "R1") (pin "1") (pinfunction "1_1") (pintype "passive"))
      (node (ref "R10") (pin "2") (pinfunction "2_2") (pintype "passive"))
      (node (ref "R100") (pin "2") (pinfunction "2_2") (pintype "passive"))
      (node (ref "R101") (pin "2") (pinfunction "2_2") (pintype "passive"))
      (node (ref "R11") (pin "2") (pinfunction "2_2") (pintype "passive"))
      (node (ref "R12") (pin "2") (pinfunction "2_2") (pintype "passive"))
      (node (ref "R13") (pin "2") (pinfunction "2_2") (pintype "passive"))
      (node (ref "R14") (pin "2") (pinfunction "2_2") (pintype "passive"))
      (node (ref "R15") (pin "2") (pinfunction "2_2") (pintype "passive"))
      (node (ref "R16") (pin "2") (pinfunction "2_2") (pintype "passive"))
      (node (ref "R17") (pin "2") (pinfunction "2_2") (pintype "passive"))
      (node (ref "R18") (pin "2") (pinfunction "2_2") (pintype "passive"))
      (node (ref "R19") (pin "2") (pinfunction "2_2") (pintype "passive"))
      (node (ref "R2") (pin "1") (pinfunction "1_1") (pintype "passive"))
      (node (ref "R20") (pin "2") (pinfunction "2_2") (pintype "passive"))
      (node (ref "R21") (pin "2") (pinfunction "2_2") (pintype "passive"))
      (node (ref "R22") (pin "2") (pinfunction "2_2") (pintype "passive"))
      (node (ref "R23") (pin "2") (pinfunction "2_2") (pintype "passive"))
      (node (ref "R24") (pin "2") (pinfunction "2_2") (pintype "passive"))
      (node (ref "R27") (pin "2") (pinfunction "2_2") (pintype "passive"))
      (node (ref "R29") (pin "2") (pinfunction "2_2") (pintype "passive"))
      (node (ref "R3") (pin "1") (pinfunction "1_1") (pintype "passive"))
      (node (ref "R32") (pin "2") (pinfunction "2_2") (pintype "passive"))
      (node (ref "R35") (pin "2") (pinfunction "2_2") (pintype "passive"))
      (node (ref "R4") (pin "1") (pinfunction "1_1") (pintype "passive"))
      (node (ref "R41") (pin "2") (pinfunction "2_2") (pintype "passive"))
      (node (ref "R45") (pin "1") (pinfunction "1_1") (pintype "passive"))
      (node (ref "R5") (pin "1") (pinfunction "1_1") (pintype "passive"))
      (node (ref "R6") (pin "1") (pinfunction "1_1") (pintype "passive"))
      (node (ref "R7") (pin "1") (pinfunction "1_1") (pintype "passive"))
      (node (ref "R75") (pin "2") (pinfunction "2_2") (pintype "passive"))
      (node (ref "R8") (pin "1") (pinfunction "1_1") (pintype "passive"))
      (node (ref "R82") (pin "2") (pinfunction "2_2") (pintype "passive"))
      (node (ref "R9") (pin "2") (pinfunction "2_2") (pintype "passive"))
      (node (ref "R98") (pin "2") (pinfunction "2_2") (pintype "passive"))
      (node (ref "R99") (pin "2") (pinfunction "2_2") (pintype "passive"))
      (node (ref "SW18") (pin "1") (pinfunction "1_1") (pintype "passive"))
      (node (ref "SW18") (pin "2") (pinfunction "2_2") (pintype "passive"))
      (node (ref "SW18") (pin "3") (pinfunction "3_3") (pintype "passive"))
      (node (ref "SW18") (pin "4") (pinfunction "4_4") (pintype "passive"))
      (node (ref "U1") (pin "20") (pinfunction "VCC_20") (pintype "power_in"))
      (node (ref "U10") (pin "16") (pinfunction "VCC_16") (pintype "power_in"))
      (node (ref "U11") (pin "16") (pinfunction "VCC_16") (pintype "power_in"))
      (node (ref "U12") (pin "16") (pinfunction "VCC_16") (pintype "power_in"))
      (node (ref "U13") (pin "10") (pinfunction "ENT_10") (pintype "input"))
      (node (ref "U13") (pin "16") (pinfunction "VCC_16") (pintype "power_in"))
      (node (ref "U13") (pin "7") (pinfunction "ENP_7") (pintype "input"))
      (node (ref "U2") (pin "24") (pinfunction "VCC_24") (pintype "power_in"))
      (node (ref "U3") (pin "14") (pinfunction "VCC_14") (pintype "power_in"))
      (node (ref "U4") (pin "1") (pintype "input"))
      (node (ref "U4") (pin "14") (pinfunction "VCC_14") (pintype "power_in"))
      (node (ref "U4") (pin "2") (pintype "input"))
      (node (ref "U4") (pin "3") (pintype "input"))
      (node (ref "U5") (pin "14") (pinfunction "VCC_14") (pintype "power_in"))
      (node (ref "U6") (pin "16") (pinfunction "VCC_16") (pintype "power_in"))
      (node (ref "U7") (pin "16") (pinfunction "VCC_16") (pintype "power_in"))
      (node (ref "U8") (pin "16") (pinfunction "VCC_16") (pintype "power_in"))
      (node (ref "U9") (pin "1") (pinfunction "~{CLR}_1") (pintype "input"))
      (node (ref "U9") (pin "10") (pinfunction "~{PRE}_10") (pintype "input"))
      (node (ref "U9") (pin "14") (pinfunction "VCC_14") (pintype "power_in"))
      (node (ref "U9") (pin "4") (pinfunction "~{PRE}_4") (pintype "input"))
      (node (ref "USB1") (pin "A9") (pinfunction "VBUS_A9") (pintype "passive"))
      (node (ref "USB1") (pin "B9") (pinfunction "VBUS_B9") (pintype "passive"))
    )
    (net (code "296") (name "unconnected-(RP1-Pad1)") (class "Default")
      (node (ref "RP1") (pin "1") (pinfunction "1_1") (pintype "passive"))
    )
    (net (code "297") (name "unconnected-(SW16-+-Pad3)") (class "Default")
      (node (ref "SW16") (pin "3") (pinfunction "+_3") (pintype "passive"))
    )
    (net (code "298") (name "unconnected-(SW16---Pad4)") (class "Default")
      (node (ref "SW16") (pin "4") (pinfunction "-_4") (pintype "passive"))
    )
    (net (code "299") (name "unconnected-(SW17-+-Pad3)") (class "Default")
      (node (ref "SW17") (pin "3") (pinfunction "+_3") (pintype "passive"))
    )
    (net (code "300") (name "unconnected-(SW17---Pad4)") (class "Default")
      (node (ref "SW17") (pin "4") (pinfunction "-_4") (pintype "passive"))
    )
    (net (code "301") (name "unconnected-(U5-Pad2)") (class "Default")
      (node (ref "U5") (pin "2") (pintype "output"))
    )
    (net (code "302") (name "unconnected-(U6-RCO-Pad15)") (class "Default")
      (node (ref "U6") (pin "15") (pinfunction "RCO_15") (pintype "output"))
    )
    (net (code "303") (name "unconnected-(U9A-Q-Pad5)") (class "Default")
      (node (ref "U9") (pin "5") (pinfunction "Q_5") (pintype "output"))
    )
    (net (code "304") (name "unconnected-(U9A-~{Q}-Pad6)") (class "Default")
      (node (ref "U9") (pin "6") (pinfunction "~{Q}_6") (pintype "output"))
    )
    (net (code "305") (name "unconnected-(U9B-Q-Pad9)") (class "Default")
      (node (ref "U9") (pin "9") (pinfunction "Q_9") (pintype "output"))
    )
    (net (code "306") (name "unconnected-(U10-RCO-Pad15)") (class "Default")
      (node (ref "U10") (pin "15") (pinfunction "RCO_15") (pintype "output"))
    )
    (net (code "307") (name "unconnected-(U12-RCO-Pad15)") (class "Default")
      (node (ref "U12") (pin "15") (pinfunction "RCO_15") (pintype "output"))
    )
    (net (code "308") (name "unconnected-(U13-RCO-Pad15)") (class "Default")
      (node (ref "U13") (pin "15") (pinfunction "RCO_15") (pintype "output"))
    )
    (net (code "309") (name "unconnected-(USB1-CC1-PadA5)") (class "Default")
      (node (ref "USB1") (pin "A5") (pinfunction "CC1_A5") (pintype "passive"))
    )
    (net (code "310") (name "unconnected-(USB1-CC2-PadB5)") (class "Default")
      (node (ref "USB1") (pin "B5") (pinfunction "CC2_B5") (pintype "passive"))
    )
  )
)
